# ACB-R1_0-43-CH13.net
KiCad netlist of a schematic drawn in EAGLE
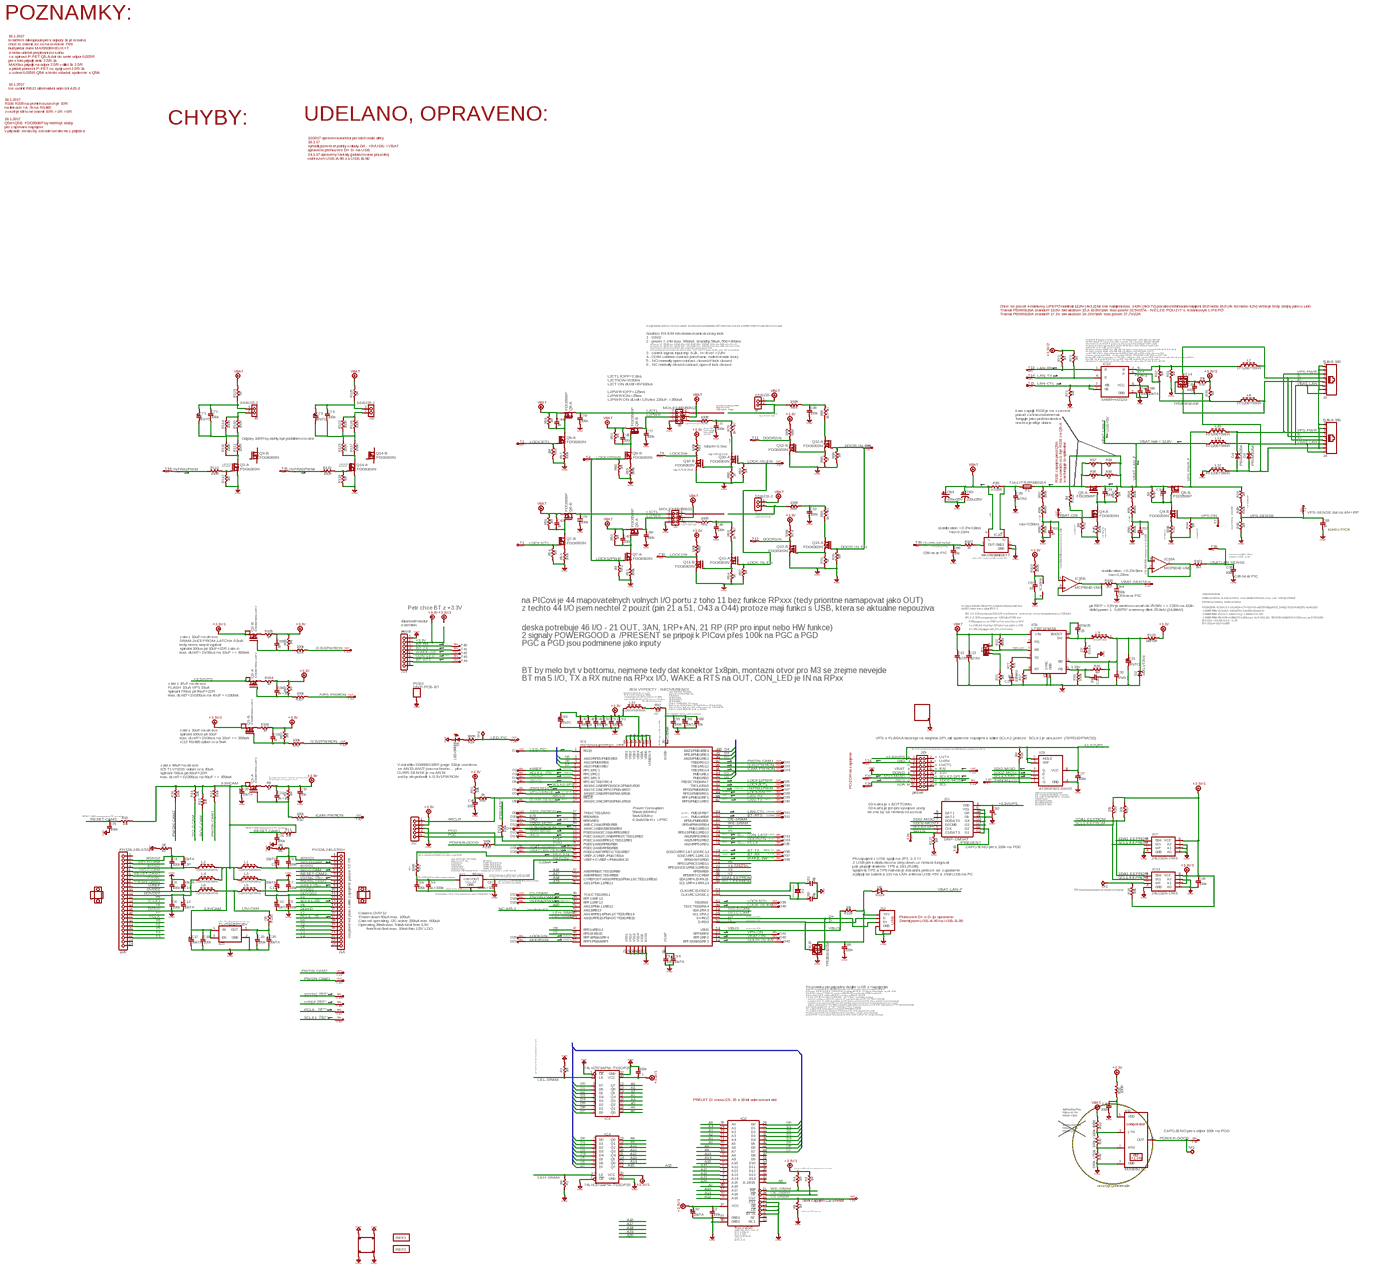
[diagram p0: schematic, sheet 1, overview]
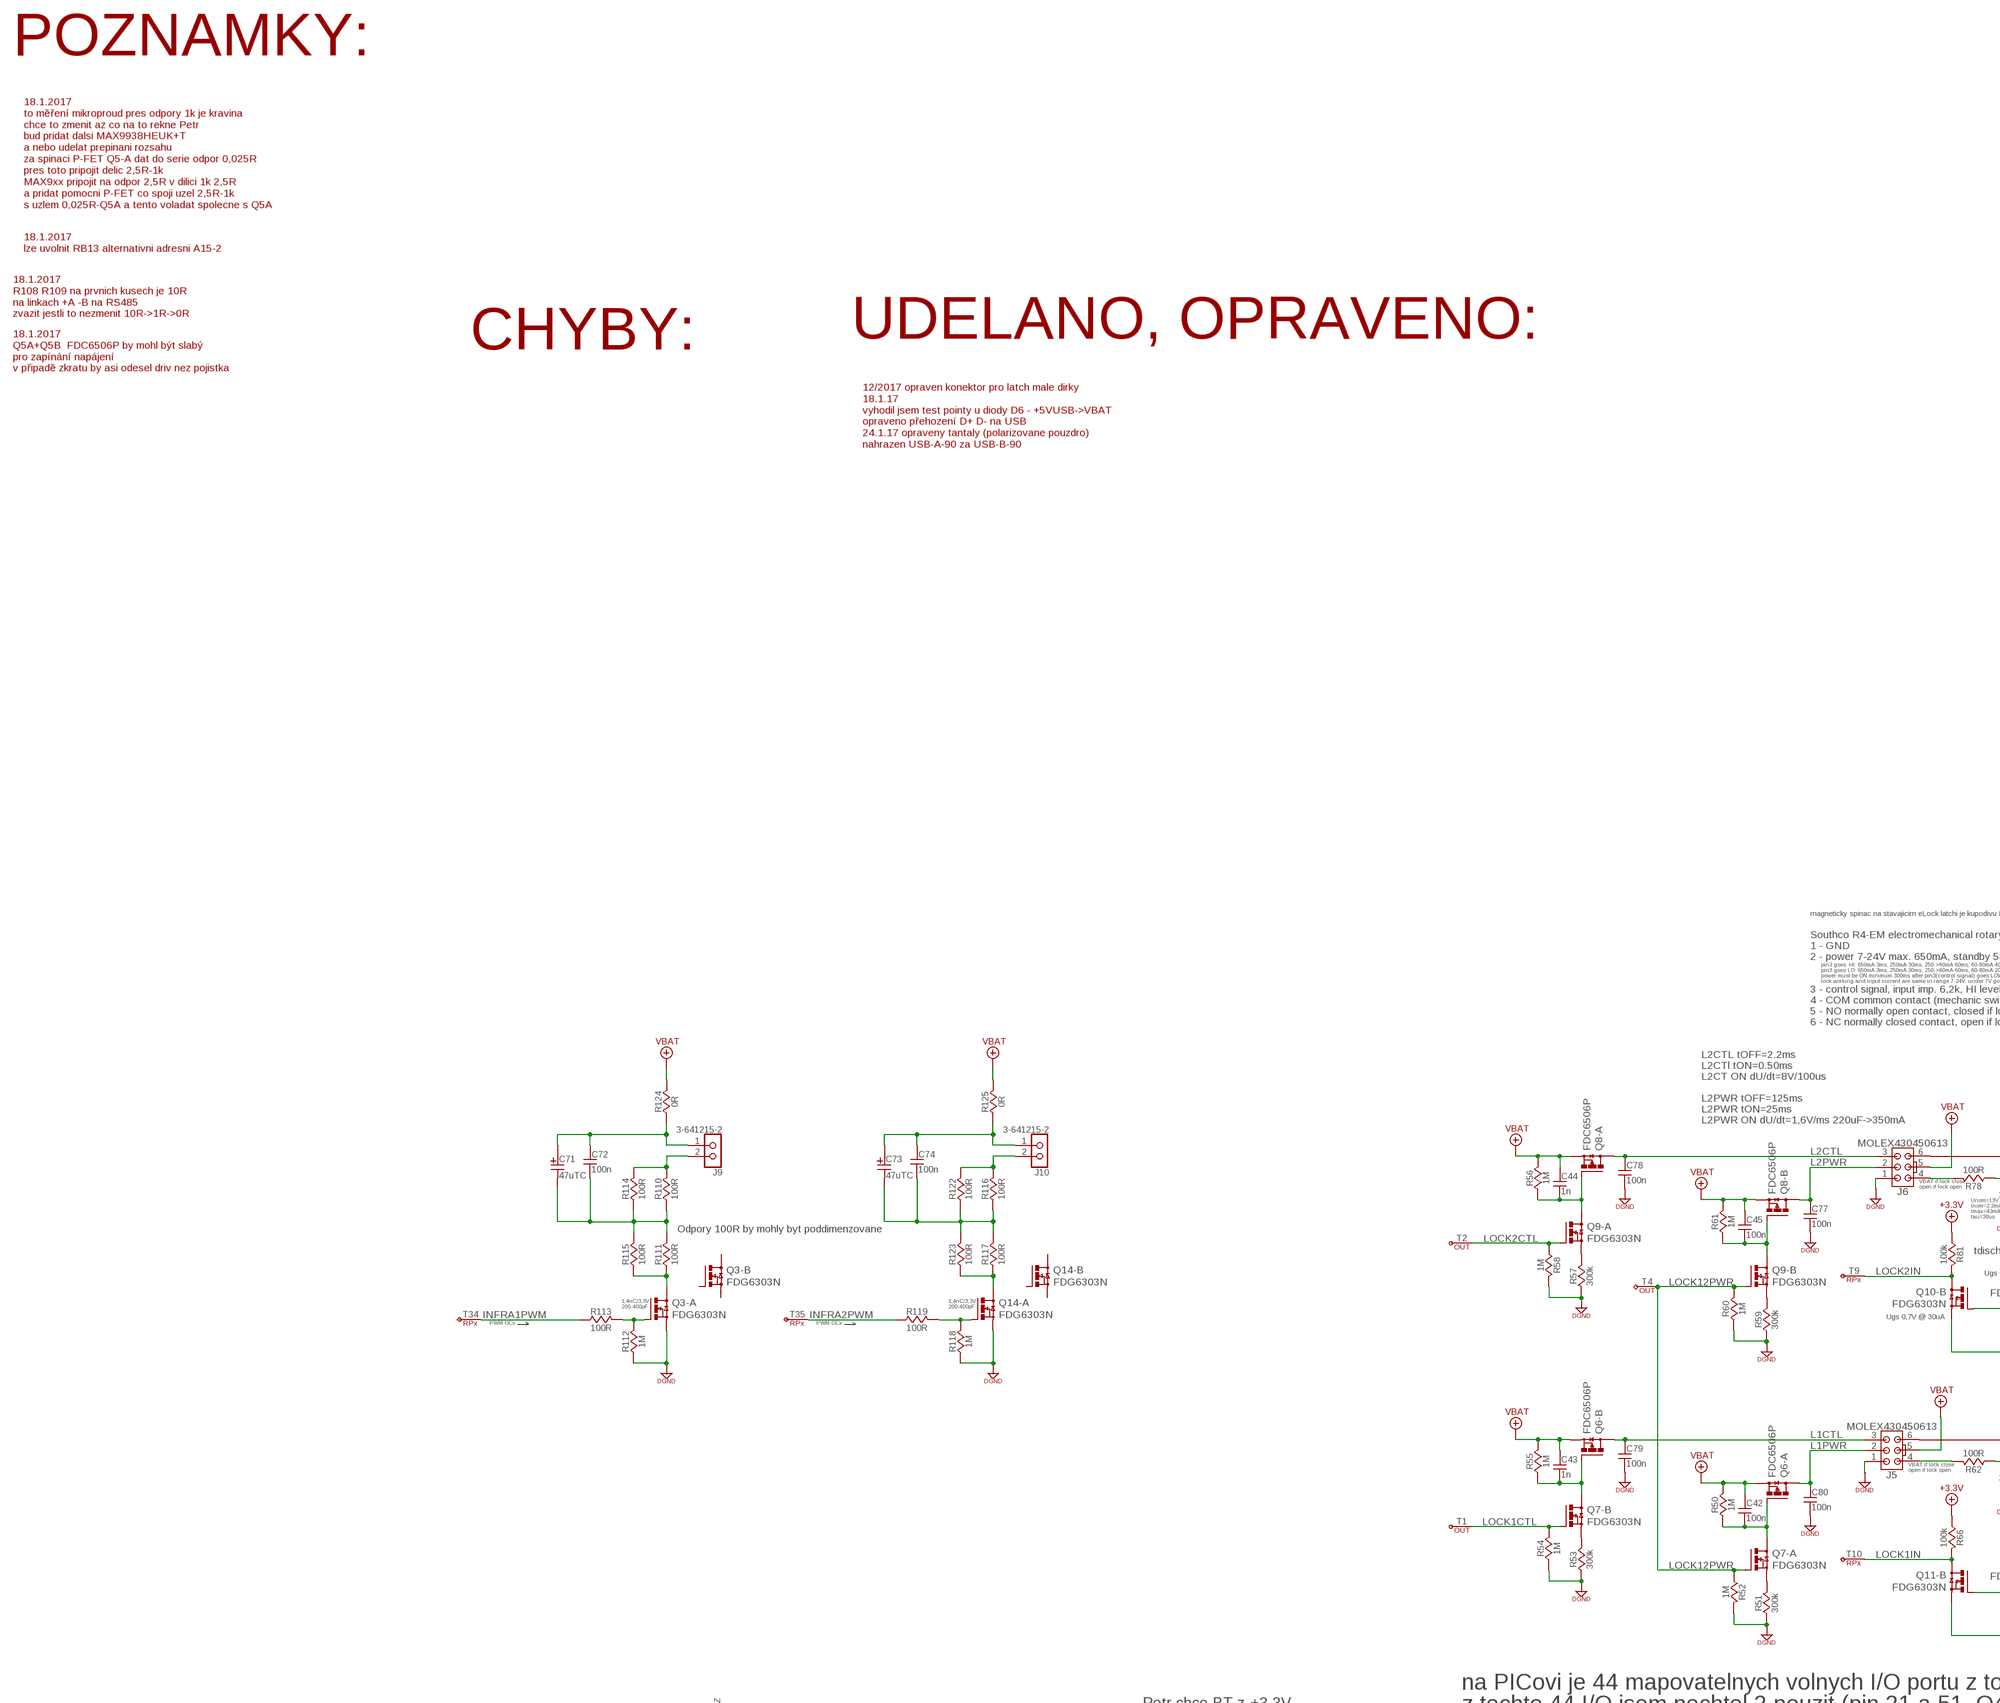
[diagram p1: schematic, sheet 1, part 1 of 4]
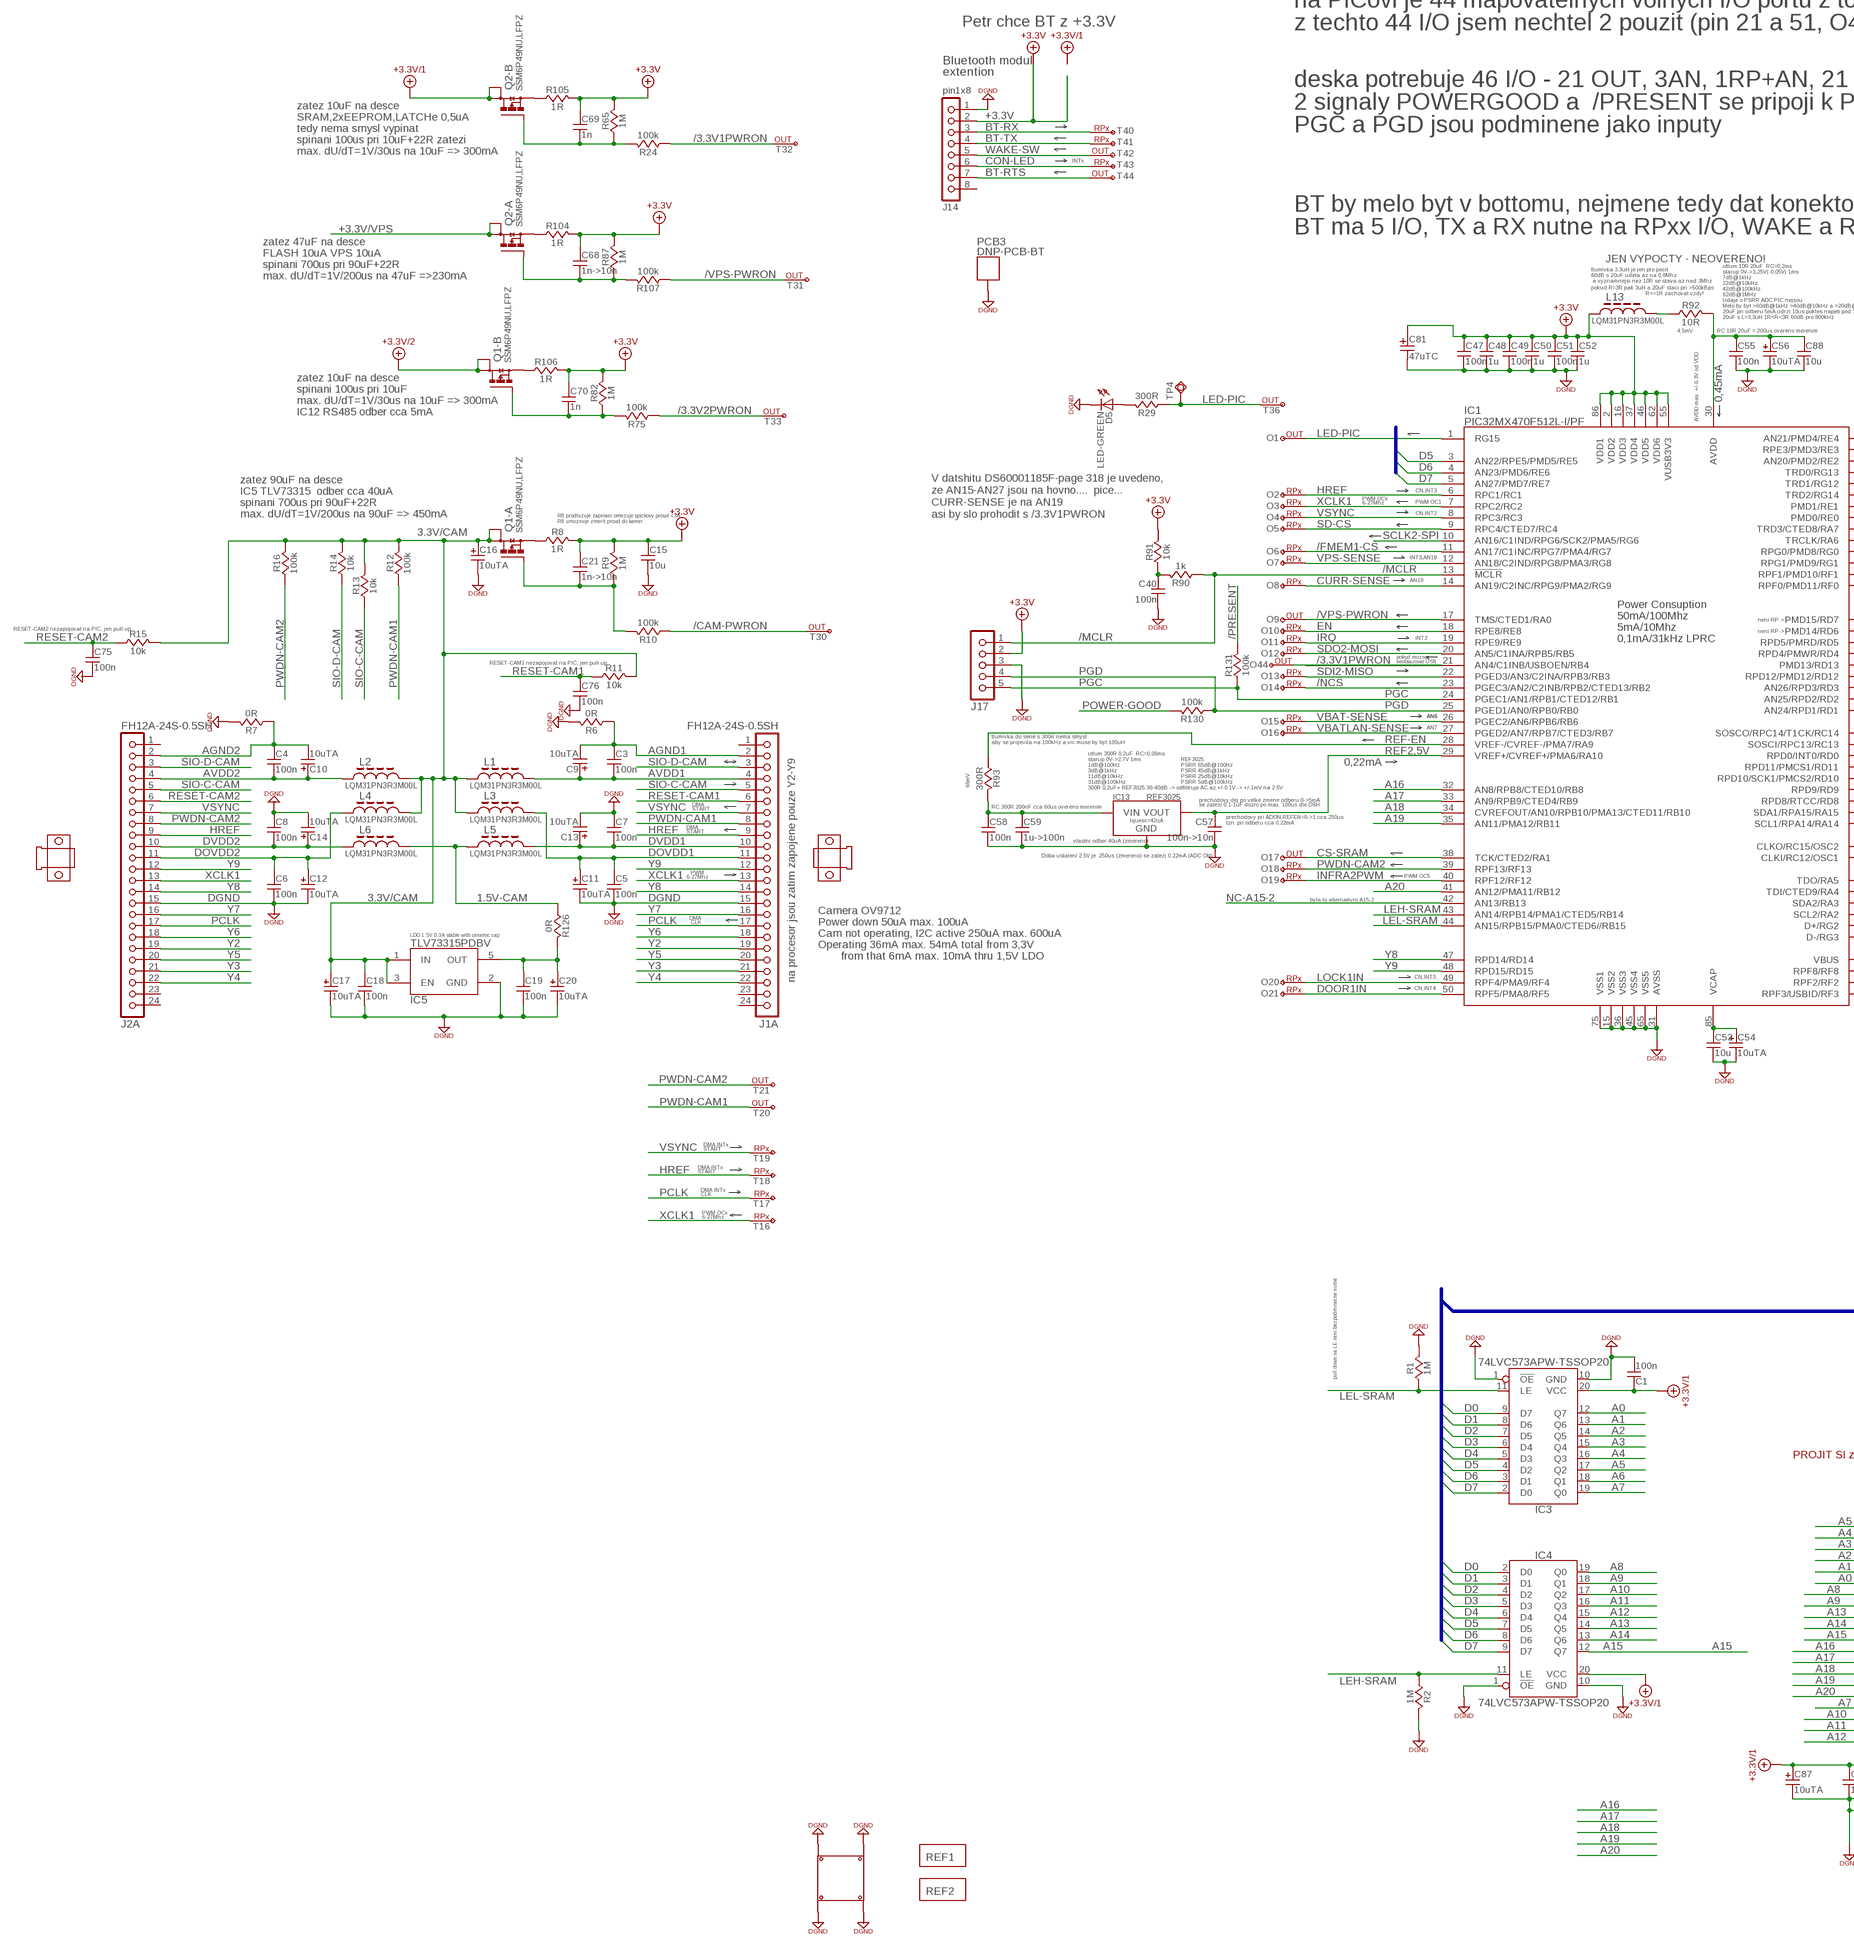
[diagram p2: schematic, sheet 1, part 2 of 4]
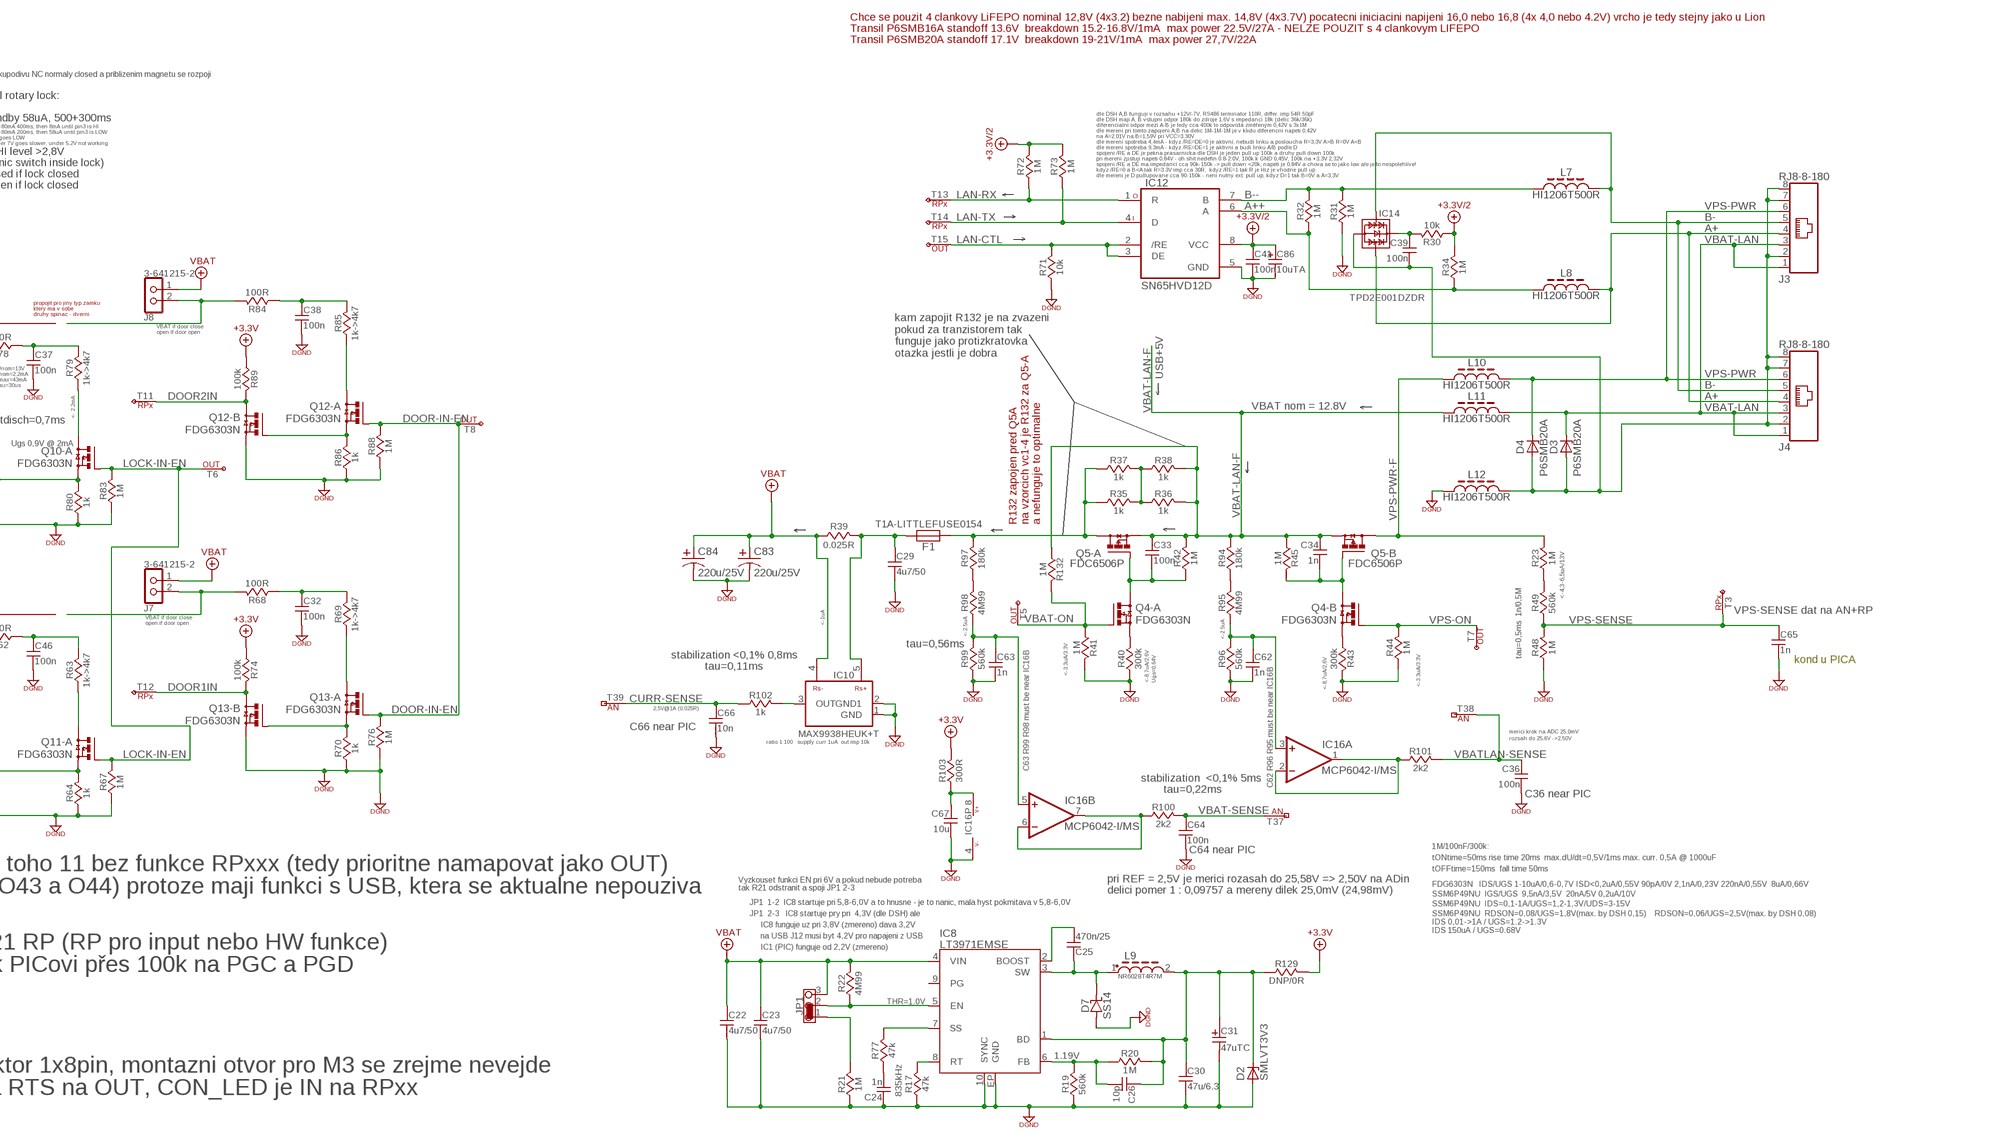
[diagram p3: schematic, sheet 1, part 3 of 4]
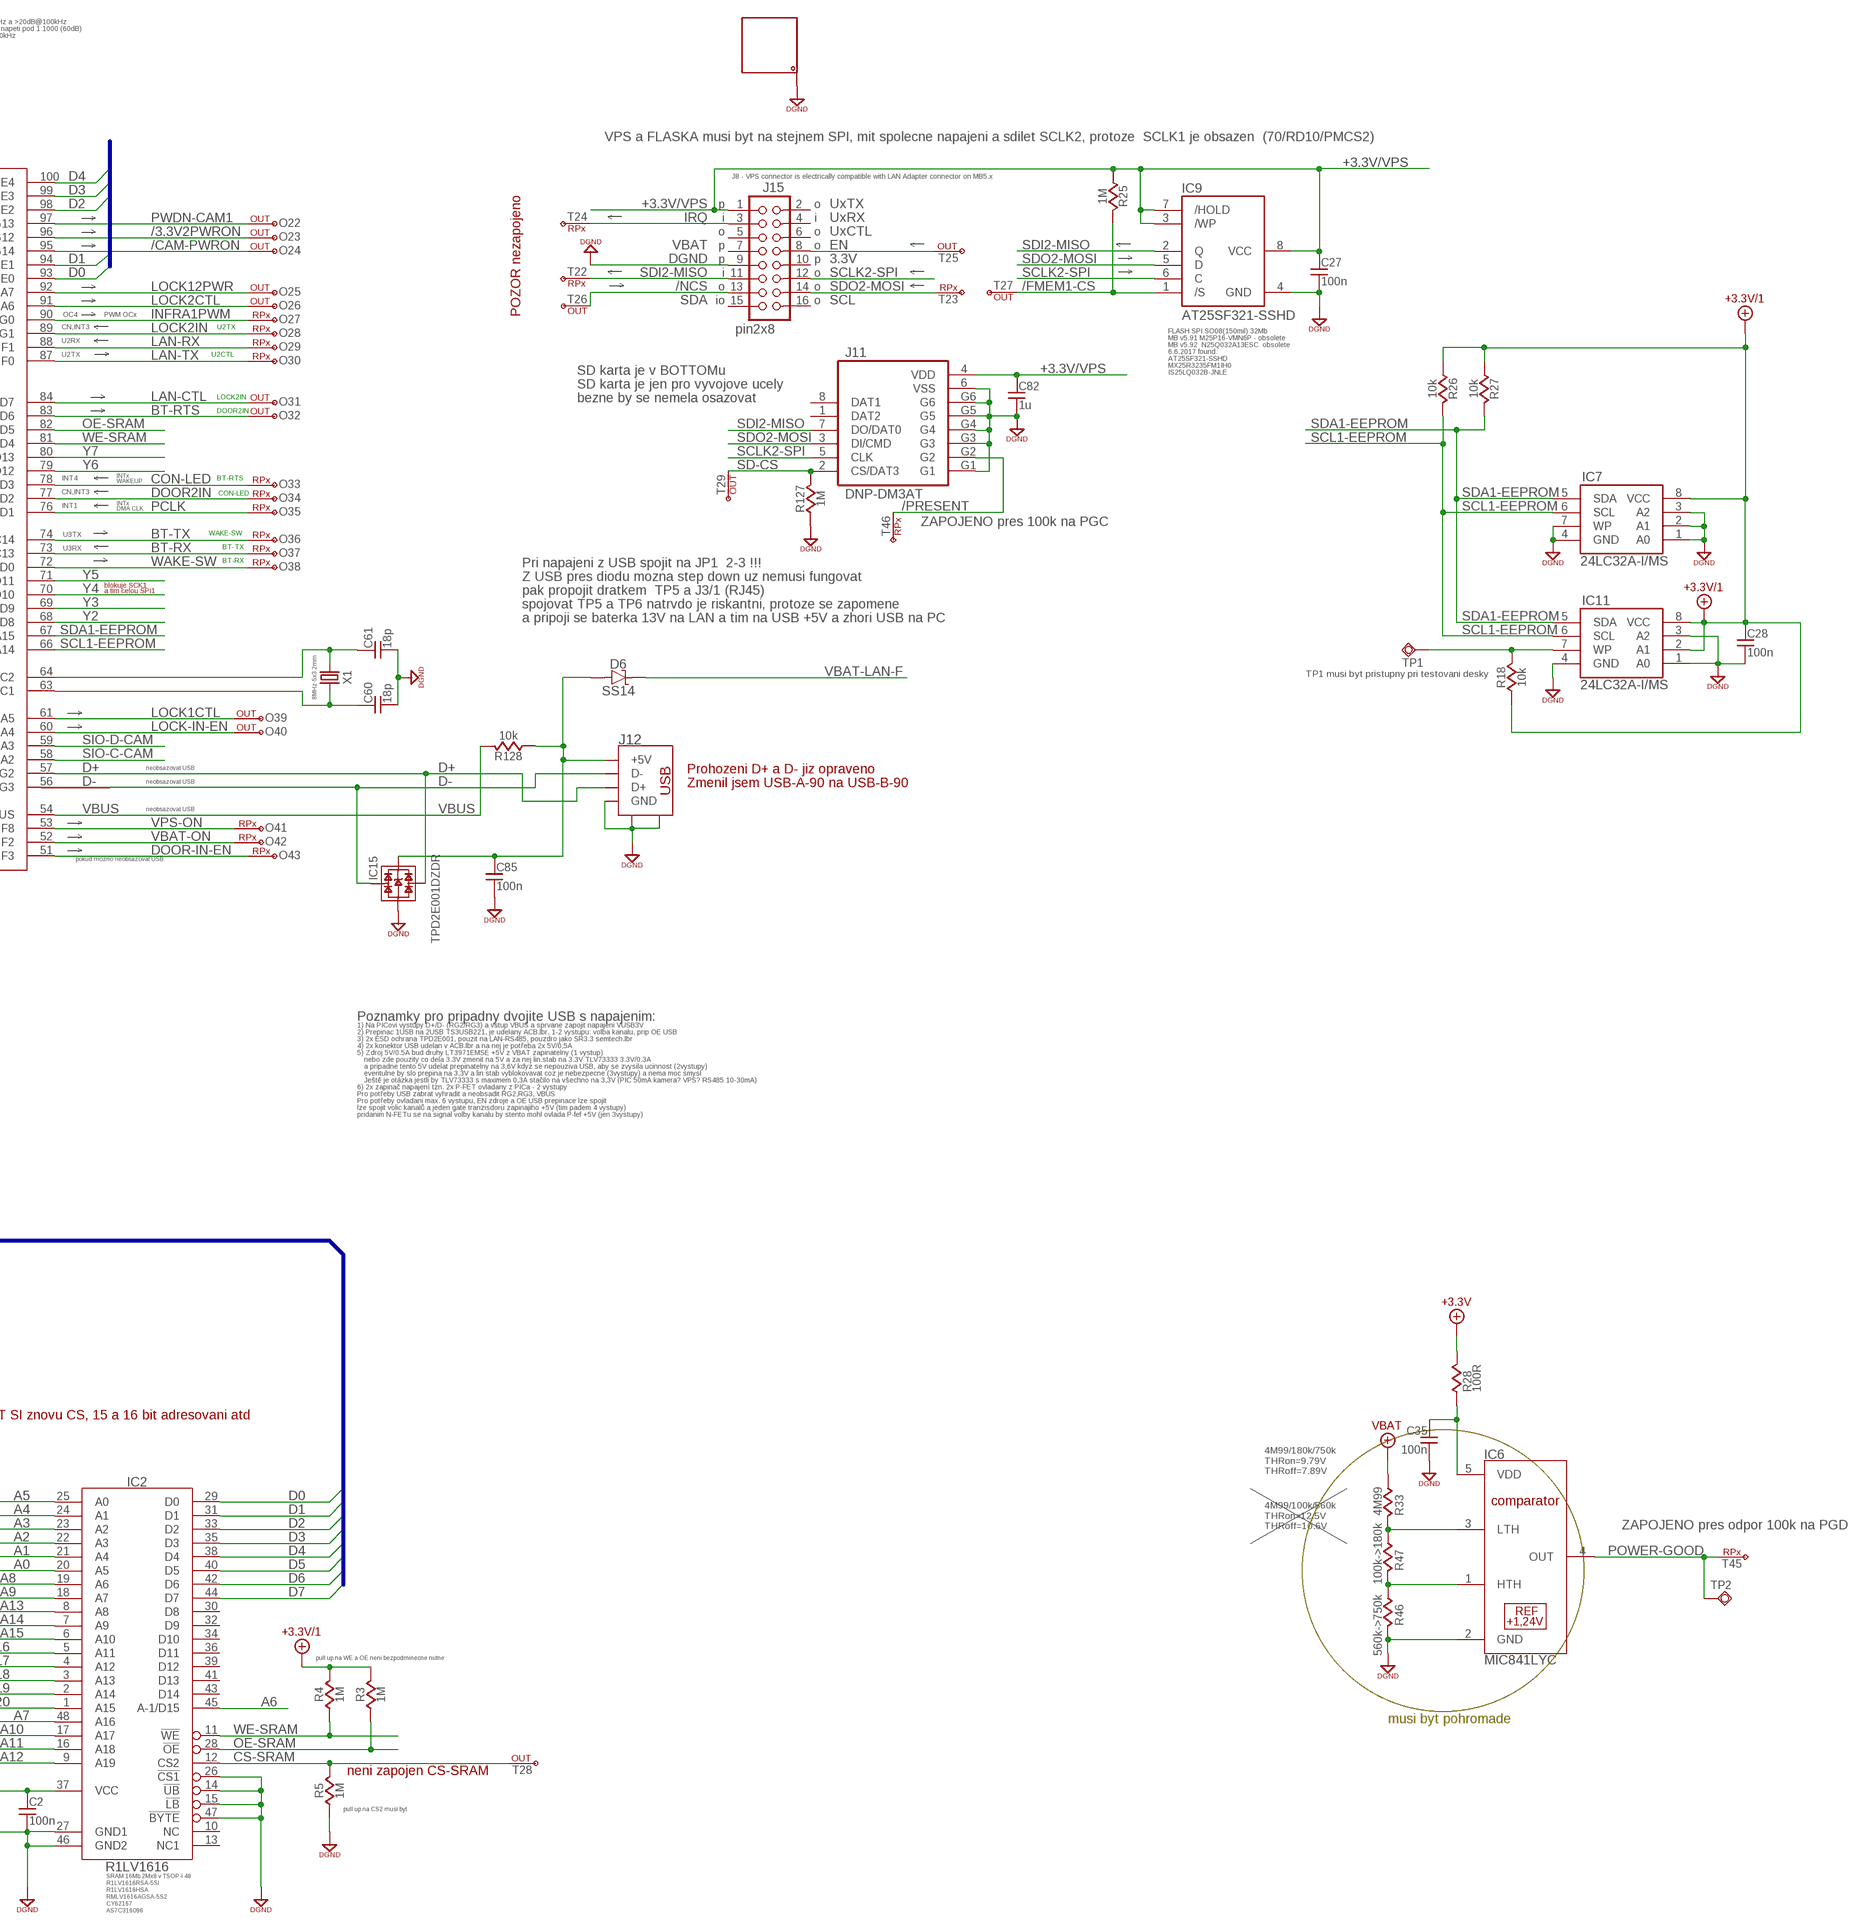
[diagram p4: schematic, sheet 1, part 4 of 4]

(export (version "E")
  (design (tool "Eeschema 10.0.6"))
  (components
    (comp (ref "C1")
      (value "100n")
      (footprint "eagle-import:0603")
      (libsource (lib "eagle-import") (part "C-0603"))
    )
    (comp (ref "C2")
      (value "100n")
      (footprint "eagle-import:0603")
      (libsource (lib "eagle-import") (part "C-0603"))
    )
    (comp (ref "C3")
      (value "100n")
      (footprint "eagle-import:0603")
      (libsource (lib "eagle-import") (part "C-0603"))
    )
    (comp (ref "C4")
      (value "100n")
      (footprint "eagle-import:0603")
      (libsource (lib "eagle-import") (part "C-0603"))
    )
    (comp (ref "C5")
      (value "100n")
      (footprint "eagle-import:0603")
      (libsource (lib "eagle-import") (part "C-0603"))
    )
    (comp (ref "C6")
      (value "100n")
      (footprint "eagle-import:0603")
      (libsource (lib "eagle-import") (part "C-0603"))
    )
    (comp (ref "C7")
      (value "100n")
      (footprint "eagle-import:0603")
      (libsource (lib "eagle-import") (part "C-0603"))
    )
    (comp (ref "C8")
      (value "100n")
      (footprint "eagle-import:0603")
      (libsource (lib "eagle-import") (part "C-0603"))
    )
    (comp (ref "C9")
      (value "10uTA")
      (footprint "eagle-import:1206-POL-C")
      (libsource (lib "eagle-import") (part "CT-1206"))
    )
    (comp (ref "C10")
      (value "10uTA")
      (footprint "eagle-import:1206-POL-C")
      (libsource (lib "eagle-import") (part "CT-1206"))
    )
    (comp (ref "C11")
      (value "10uTA")
      (footprint "eagle-import:1206-POL-C")
      (libsource (lib "eagle-import") (part "CT-1206"))
    )
    (comp (ref "C12")
      (value "10uTA")
      (footprint "eagle-import:1206-POL-C")
      (libsource (lib "eagle-import") (part "CT-1206"))
    )
    (comp (ref "C13")
      (value "10uTA")
      (footprint "eagle-import:1206-POL-C")
      (libsource (lib "eagle-import") (part "CT-1206"))
    )
    (comp (ref "C14")
      (value "10uTA")
      (footprint "eagle-import:1206-POL-C")
      (libsource (lib "eagle-import") (part "CT-1206"))
    )
    (comp (ref "C15")
      (value "10u")
      (footprint "eagle-import:0603")
      (libsource (lib "eagle-import") (part "C-0603"))
    )
    (comp (ref "C16")
      (value "10uTA")
      (footprint "eagle-import:1206-POL-C")
      (libsource (lib "eagle-import") (part "CT-1206"))
    )
    (comp (ref "C17")
      (value "10uTA")
      (footprint "eagle-import:1206-POL-C")
      (libsource (lib "eagle-import") (part "CT-1206"))
    )
    (comp (ref "C18")
      (value "100n")
      (footprint "eagle-import:0603")
      (libsource (lib "eagle-import") (part "C-0603"))
    )
    (comp (ref "C19")
      (value "100n")
      (footprint "eagle-import:0603")
      (libsource (lib "eagle-import") (part "C-0603"))
    )
    (comp (ref "C20")
      (value "10uTA")
      (footprint "eagle-import:1206-POL-C")
      (libsource (lib "eagle-import") (part "CT-1206"))
    )
    (comp (ref "C21")
      (value "1n->10n")
      (footprint "eagle-import:0603")
      (libsource (lib "eagle-import") (part "C-0603"))
    )
    (comp (ref "C22")
      (value "4u7/50")
      (footprint "eagle-import:1206")
      (libsource (lib "eagle-import") (part "C-1206"))
    )
    (comp (ref "C23")
      (value "4u7/50")
      (footprint "eagle-import:1206")
      (libsource (lib "eagle-import") (part "C-1206"))
    )
    (comp (ref "C24")
      (value "1n")
      (footprint "eagle-import:0603")
      (libsource (lib "eagle-import") (part "C-0603"))
    )
    (comp (ref "C25")
      (value "470n/25")
      (footprint "eagle-import:0603")
      (libsource (lib "eagle-import") (part "C-0603"))
    )
    (comp (ref "C26")
      (value "10p")
      (footprint "eagle-import:0603")
      (libsource (lib "eagle-import") (part "C-0603"))
    )
    (comp (ref "C27")
      (value "100n")
      (footprint "eagle-import:0603")
      (libsource (lib "eagle-import") (part "C-0603"))
    )
    (comp (ref "C28")
      (value "100n")
      (footprint "eagle-import:0603")
      (libsource (lib "eagle-import") (part "C-0603"))
    )
    (comp (ref "C29")
      (value "4u7/50")
      (footprint "eagle-import:1206")
      (libsource (lib "eagle-import") (part "C-1206"))
    )
    (comp (ref "C30")
      (value "47u/6.3")
      (footprint "eagle-import:1206")
      (libsource (lib "eagle-import") (part "C-1206"))
    )
    (comp (ref "C31")
      (value "47uTC")
      (footprint "eagle-import:CT-C")
      (libsource (lib "eagle-import") (part "CT-C"))
    )
    (comp (ref "C32")
      (value "100n")
      (footprint "eagle-import:0603")
      (libsource (lib "eagle-import") (part "C-0603"))
    )
    (comp (ref "C33")
      (value "100n")
      (footprint "eagle-import:0603")
      (libsource (lib "eagle-import") (part "C-0603"))
    )
    (comp (ref "C34")
      (value "1n")
      (footprint "eagle-import:0603")
      (libsource (lib "eagle-import") (part "C-0603"))
    )
    (comp (ref "C35")
      (value "100n")
      (footprint "eagle-import:0603")
      (libsource (lib "eagle-import") (part "C-0603"))
    )
    (comp (ref "C36")
      (value "100n")
      (footprint "eagle-import:0603")
      (libsource (lib "eagle-import") (part "C-0603"))
    )
    (comp (ref "C37")
      (value "100n")
      (footprint "eagle-import:0603")
      (libsource (lib "eagle-import") (part "C-0603"))
    )
    (comp (ref "C38")
      (value "100n")
      (footprint "eagle-import:0603")
      (libsource (lib "eagle-import") (part "C-0603"))
    )
    (comp (ref "C39")
      (value "100n")
      (footprint "eagle-import:0603")
      (libsource (lib "eagle-import") (part "C-0603"))
    )
    (comp (ref "C40")
      (value "100n")
      (footprint "eagle-import:0603")
      (libsource (lib "eagle-import") (part "C-0603"))
    )
    (comp (ref "C41")
      (value "100n")
      (footprint "eagle-import:0603")
      (libsource (lib "eagle-import") (part "C-0603"))
    )
    (comp (ref "C42")
      (value "100n")
      (footprint "eagle-import:0603")
      (libsource (lib "eagle-import") (part "C-0603"))
    )
    (comp (ref "C43")
      (value "1n")
      (footprint "eagle-import:0603")
      (libsource (lib "eagle-import") (part "C-0603"))
    )
    (comp (ref "C44")
      (value "1n")
      (footprint "eagle-import:0603")
      (libsource (lib "eagle-import") (part "C-0603"))
    )
    (comp (ref "C45")
      (value "100n")
      (footprint "eagle-import:0603")
      (libsource (lib "eagle-import") (part "C-0603"))
    )
    (comp (ref "C46")
      (value "100n")
      (footprint "eagle-import:0603")
      (libsource (lib "eagle-import") (part "C-0603"))
    )
    (comp (ref "C47")
      (value "100n")
      (footprint "eagle-import:0603")
      (libsource (lib "eagle-import") (part "C-0603"))
    )
    (comp (ref "C48")
      (value "1u")
      (footprint "eagle-import:0603")
      (libsource (lib "eagle-import") (part "C-0603"))
    )
    (comp (ref "C49")
      (value "100n")
      (footprint "eagle-import:0603")
      (libsource (lib "eagle-import") (part "C-0603"))
    )
    (comp (ref "C50")
      (value "1u")
      (footprint "eagle-import:0603")
      (libsource (lib "eagle-import") (part "C-0603"))
    )
    (comp (ref "C51")
      (value "100n")
      (footprint "eagle-import:0603")
      (libsource (lib "eagle-import") (part "C-0603"))
    )
    (comp (ref "C52")
      (value "1u")
      (footprint "eagle-import:0603")
      (libsource (lib "eagle-import") (part "C-0603"))
    )
    (comp (ref "C53")
      (value "10u")
      (footprint "eagle-import:0603")
      (libsource (lib "eagle-import") (part "C-0603"))
    )
    (comp (ref "C54")
      (value "10uTA")
      (footprint "eagle-import:1206-POL-C")
      (libsource (lib "eagle-import") (part "CT-1206"))
    )
    (comp (ref "C55")
      (value "100n")
      (footprint "eagle-import:0603")
      (libsource (lib "eagle-import") (part "C-0603"))
    )
    (comp (ref "C56")
      (value "10uTA")
      (footprint "eagle-import:1206-POL-C")
      (libsource (lib "eagle-import") (part "CT-1206"))
    )
    (comp (ref "C57")
      (value "100n->10n")
      (footprint "eagle-import:0603")
      (libsource (lib "eagle-import") (part "C-0603"))
    )
    (comp (ref "C58")
      (value "100n")
      (footprint "eagle-import:0603")
      (libsource (lib "eagle-import") (part "C-0603"))
    )
    (comp (ref "C59")
      (value "1u->100n")
      (footprint "eagle-import:0603")
      (libsource (lib "eagle-import") (part "C-0603"))
    )
    (comp (ref "C60")
      (value "18p")
      (footprint "eagle-import:0603")
      (libsource (lib "eagle-import") (part "C-0603"))
    )
    (comp (ref "C61")
      (value "18p")
      (footprint "eagle-import:0603")
      (libsource (lib "eagle-import") (part "C-0603"))
    )
    (comp (ref "C62")
      (value "1n")
      (footprint "eagle-import:0603")
      (libsource (lib "eagle-import") (part "C-0603"))
    )
    (comp (ref "C63")
      (value "1n")
      (footprint "eagle-import:0603")
      (libsource (lib "eagle-import") (part "C-0603"))
    )
    (comp (ref "C64")
      (value "100n")
      (footprint "eagle-import:0603")
      (libsource (lib "eagle-import") (part "C-0603"))
    )
    (comp (ref "C65")
      (value "1n")
      (footprint "eagle-import:0603")
      (libsource (lib "eagle-import") (part "C-0603"))
    )
    (comp (ref "C66")
      (value "10n")
      (footprint "eagle-import:0603")
      (libsource (lib "eagle-import") (part "C-0603"))
    )
    (comp (ref "C67")
      (value "10u")
      (footprint "eagle-import:0603")
      (libsource (lib "eagle-import") (part "C-0603"))
    )
    (comp (ref "C68")
      (value "1n->10n")
      (footprint "eagle-import:0603")
      (libsource (lib "eagle-import") (part "C-0603"))
    )
    (comp (ref "C69")
      (value "1n")
      (footprint "eagle-import:0603")
      (libsource (lib "eagle-import") (part "C-0603"))
    )
    (comp (ref "C70")
      (value "1n")
      (footprint "eagle-import:0603")
      (libsource (lib "eagle-import") (part "C-0603"))
    )
    (comp (ref "C71")
      (value "47uTC")
      (footprint "eagle-import:CT-C")
      (libsource (lib "eagle-import") (part "CT-C"))
    )
    (comp (ref "C72")
      (value "100n")
      (footprint "eagle-import:0603")
      (libsource (lib "eagle-import") (part "C-0603"))
    )
    (comp (ref "C73")
      (value "47uTC")
      (footprint "eagle-import:CT-C")
      (libsource (lib "eagle-import") (part "CT-C"))
    )
    (comp (ref "C74")
      (value "100n")
      (footprint "eagle-import:0603")
      (libsource (lib "eagle-import") (part "C-0603"))
    )
    (comp (ref "C75")
      (value "100n")
      (footprint "eagle-import:0603")
      (libsource (lib "eagle-import") (part "C-0603"))
    )
    (comp (ref "C76")
      (value "100n")
      (footprint "eagle-import:0603")
      (libsource (lib "eagle-import") (part "C-0603"))
    )
    (comp (ref "C77")
      (value "100n")
      (footprint "eagle-import:0603")
      (libsource (lib "eagle-import") (part "C-0603"))
    )
    (comp (ref "C78")
      (value "100n")
      (footprint "eagle-import:0603")
      (libsource (lib "eagle-import") (part "C-0603"))
    )
    (comp (ref "C79")
      (value "100n")
      (footprint "eagle-import:0603")
      (libsource (lib "eagle-import") (part "C-0603"))
    )
    (comp (ref "C80")
      (value "100n")
      (footprint "eagle-import:0603")
      (libsource (lib "eagle-import") (part "C-0603"))
    )
    (comp (ref "C81")
      (value "47uTC")
      (footprint "eagle-import:CT-C")
      (libsource (lib "eagle-import") (part "CT-C"))
    )
    (comp (ref "C82")
      (value "1u")
      (footprint "eagle-import:0603")
      (libsource (lib "eagle-import") (part "C-0603"))
    )
    (comp (ref "C83")
      (value "220u/25V")
      (footprint "eagle-import:CAP_8MM_DIA_SMT")
      (libsource (lib "eagle-import") (part "CAP-ELEC-SMD-8MM"))
    )
    (comp (ref "C84")
      (value "220u/25V")
      (footprint "eagle-import:CAP_8MM_DIA_SMT")
      (libsource (lib "eagle-import") (part "CAP-ELEC-SMD-8MM"))
    )
    (comp (ref "C85")
      (value "100n")
      (footprint "eagle-import:0603")
      (libsource (lib "eagle-import") (part "C-0603"))
    )
    (comp (ref "C86")
      (value "10uTA")
      (footprint "eagle-import:1206-POL-C")
      (libsource (lib "eagle-import") (part "CT-1206"))
    )
    (comp (ref "C87")
      (value "10uTA")
      (footprint "eagle-import:1206-POL-C")
      (libsource (lib "eagle-import") (part "CT-1206"))
    )
    (comp (ref "C88")
      (value "10u")
      (footprint "eagle-import:0603")
      (libsource (lib "eagle-import") (part "C-0603"))
    )
    (comp (ref "D2")
      (value "SMLVT3V3")
      (footprint "eagle-import:SMA")
      (libsource (lib "eagle-import") (part "SMLVT3V3"))
    )
    (comp (ref "D3")
      (value "P6SMB20A")
      (footprint "eagle-import:SMB")
      (libsource (lib "eagle-import") (part "P6SMB"))
    )
    (comp (ref "D4")
      (value "P6SMB20A")
      (footprint "eagle-import:SMB")
      (libsource (lib "eagle-import") (part "P6SMB"))
    )
    (comp (ref "D5")
      (value "LED-GREEN")
      (footprint "eagle-import:0805-POL-D")
      (libsource (lib "eagle-import") (part "LED-0805"))
    )
    (comp (ref "D6")
      (value "SS14")
      (footprint "eagle-import:SMA")
      (libsource (lib "eagle-import") (part "DS-SMA"))
    )
    (comp (ref "D7")
      (value "SS14")
      (footprint "eagle-import:SMA")
      (libsource (lib "eagle-import") (part "DS-SMA"))
    )
    (comp (ref "F1")
      (value "T1A-LITTLEFUSE0154")
      (footprint "eagle-import:LITTLEFUSE0154")
      (libsource (lib "eagle-import") (part "POJISTKA-LITTLEFUSE0154"))
    )
    (comp (ref "H1")
      (value "CAM-HOLDER")
      (footprint "eagle-import:CAM-HOLDER")
      (libsource (lib "eagle-import") (part "CAM-HOLDER"))
    )
    (comp (ref "H2")
      (value "CAM-HOLDER")
      (footprint "eagle-import:CAM-HOLDER")
      (libsource (lib "eagle-import") (part "CAM-HOLDER"))
    )
    (comp (ref "IC1")
      (value "PIC32MX470F512L-I/PF")
      (footprint "eagle-import:TQFP100_14X14_0,5MM")
      (libsource (lib "eagle-import") (part "PIC32MX470F512L-I/PF"))
    )
    (comp (ref "IC2")
      (value "R1LV1616")
      (footprint "eagle-import:48-TSOP-I")
      (libsource (lib "eagle-import") (part "R1LV1616HSA"))
    )
    (comp (ref "IC3")
      (value "74LVC573APW-TSSOP20")
      (footprint "eagle-import:TSSOP20")
      (libsource (lib "eagle-import") (part "74LVC573APW-TSSOP20"))
    )
    (comp (ref "IC4")
      (value "74LVC573APW-TSSOP20")
      (footprint "eagle-import:TSSOP20")
      (libsource (lib "eagle-import") (part "74LVC573APW-TSSOP20"))
    )
    (comp (ref "IC5")
      (value "TLV73315PDBV")
      (footprint "eagle-import:SOT23-5")
      (libsource (lib "eagle-import") (part "TLV73315PDBV"))
    )
    (comp (ref "IC6")
      (value "MIC841LYC")
      (footprint "eagle-import:SC-70-5")
      (libsource (lib "eagle-import") (part "MIC841LYC"))
    )
    (comp (ref "IC7")
      (value "24LC32A-I/MS")
      (footprint "eagle-import:MSOP-08")
      (libsource (lib "eagle-import") (part "24-I/MS"))
    )
    (comp (ref "IC8")
      (value "LT3971EMSE")
      (footprint "eagle-import:MSOP10EXP")
      (libsource (lib "eagle-import") (part "LT3971EMSE"))
    )
    (comp (ref "IC9")
      (value "AT25SF321-SSHD")
      (footprint "eagle-import:SO-08")
      (libsource (lib "eagle-import") (part "M25P16-VMN6P"))
    )
    (comp (ref "IC10")
      (value "MAX9938HEUK+T")
      (footprint "eagle-import:SOT23-5")
      (libsource (lib "eagle-import") (part "TSM9938HEUK+T"))
    )
    (comp (ref "IC11")
      (value "24LC32A-I/MS")
      (footprint "eagle-import:MSOP-08")
      (libsource (lib "eagle-import") (part "24-I/MS"))
    )
    (comp (ref "IC12")
      (value "SN65HVD12D")
      (footprint "eagle-import:SO08")
      (libsource (lib "eagle-import") (part "SN65HVD3082ED"))
    )
    (comp (ref "IC13")
      (value "REF3025")
      (footprint "eagle-import:SOT23")
      (libsource (lib "eagle-import") (part "REF3025"))
    )
    (comp (ref "IC14")
      (value "TPD2E001DZDR")
      (footprint "eagle-import:SOT-143")
      (libsource (lib "eagle-import") (part "SR05.TCT"))
    )
    (comp (ref "IC15")
      (value "TPD2E001DZDR")
      (footprint "eagle-import:SOT-143")
      (libsource (lib "eagle-import") (part "SR05.TCT"))
    )
    (comp (ref "IC16")
      (value "MCP6042-I/MS")
      (footprint "eagle-import:MSOP-08")
      (libsource (lib "eagle-import") (part "MCP6042-I/MS"))
    )
    (comp (ref "J1")
      (value "FH12A-24S-0.5SH")
      (footprint "eagle-import:FH12A-24S-05SH")
      (libsource (lib "eagle-import") (part "FH12A-24S-0.5SH"))
    )
    (comp (ref "J2")
      (value "FH12A-24S-0.5SH")
      (footprint "eagle-import:FH12A-24S-05SH")
      (libsource (lib "eagle-import") (part "FH12A-24S-0.5SH"))
    )
    (comp (ref "J3")
      (value "RJ8-8-180")
      (footprint "eagle-import:RJ8-8-180")
      (libsource (lib "eagle-import") (part "RJ8-8-180"))
    )
    (comp (ref "J4")
      (value "RJ8-8-180")
      (footprint "eagle-import:RJ8-8-180")
      (libsource (lib "eagle-import") (part "RJ8-8-180"))
    )
    (comp (ref "J5")
      (value "MOLEX430450613")
      (footprint "eagle-import:MOLEX430450613")
      (libsource (lib "eagle-import") (part "MOLEX430450613"))
    )
    (comp (ref "J6")
      (value "MOLEX430450613")
      (footprint "eagle-import:MOLEX430450613")
      (libsource (lib "eagle-import") (part "MOLEX430450613"))
    )
    (comp (ref "J7")
      (value "3-641215-2")
      (footprint "eagle-import:3-641215-2")
      (libsource (lib "eagle-import") (part "3-641215-2"))
    )
    (comp (ref "J8")
      (value "3-641215-2")
      (footprint "eagle-import:3-641215-2")
      (libsource (lib "eagle-import") (part "3-641215-2"))
    )
    (comp (ref "J9")
      (value "3-641215-2")
      (footprint "eagle-import:3-641215-2")
      (libsource (lib "eagle-import") (part "3-641215-2"))
    )
    (comp (ref "J10")
      (value "3-641215-2")
      (footprint "eagle-import:3-641215-2")
      (libsource (lib "eagle-import") (part "3-641215-2"))
    )
    (comp (ref "J11")
      (value "DNP-DM3AT")
      (footprint "eagle-import:DM3AT")
      (libsource (lib "eagle-import") (part "DM3AT"))
    )
    (comp (ref "J12")
      (value "USB_A_180")
      (footprint "eagle-import:USB_B_180")
      (libsource (lib "eagle-import") (part "USB_B_180"))
    )
    (comp (ref "J14")
      (value "pin1x8")
      (footprint "eagle-import:MA08-1-MALE")
      (libsource (lib "eagle-import") (part "MA08-1-M"))
    )
    (comp (ref "J15")
      (value "pin2x8")
      (footprint "eagle-import:MA08-2")
      (libsource (lib "eagle-import") (part "MA08-2"))
    )
    (comp (ref "J17")
      (value "DNP-open-hole")
      (footprint "eagle-import:MA05-1")
      (libsource (lib "eagle-import") (part "MA05-1"))
    )
    (comp (ref "JP1")
      (value "JP3CLOSE12")
      (footprint "eagle-import:JP3CLOSE12")
      (libsource (lib "eagle-import") (part "JP3CLOSE12"))
    )
    (comp (ref "L1")
      (value "LQM31PN3R3M00L")
      (footprint "eagle-import:1206")
      (libsource (lib "eagle-import") (part "L-1206"))
    )
    (comp (ref "L2")
      (value "LQM31PN3R3M00L")
      (footprint "eagle-import:1206")
      (libsource (lib "eagle-import") (part "L-1206"))
    )
    (comp (ref "L3")
      (value "LQM31PN3R3M00L")
      (footprint "eagle-import:1206")
      (libsource (lib "eagle-import") (part "L-1206"))
    )
    (comp (ref "L4")
      (value "LQM31PN3R3M00L")
      (footprint "eagle-import:1206")
      (libsource (lib "eagle-import") (part "L-1206"))
    )
    (comp (ref "L5")
      (value "LQM31PN3R3M00L")
      (footprint "eagle-import:1206")
      (libsource (lib "eagle-import") (part "L-1206"))
    )
    (comp (ref "L6")
      (value "LQM31PN3R3M00L")
      (footprint "eagle-import:1206")
      (libsource (lib "eagle-import") (part "L-1206"))
    )
    (comp (ref "L7")
      (value "HI1206T500R")
      (footprint "eagle-import:1206")
      (libsource (lib "eagle-import") (part "L-1206"))
    )
    (comp (ref "L8")
      (value "HI1206T500R")
      (footprint "eagle-import:1206")
      (libsource (lib "eagle-import") (part "L-1206"))
    )
    (comp (ref "L9")
      (value "NR6028T4R7M")
      (footprint "eagle-import:NR6028")
      (libsource (lib "eagle-import") (part "NR6028"))
    )
    (comp (ref "L10")
      (value "HI1206T500R")
      (footprint "eagle-import:1206")
      (libsource (lib "eagle-import") (part "L-1206"))
    )
    (comp (ref "L11")
      (value "HI1206T500R")
      (footprint "eagle-import:1206")
      (libsource (lib "eagle-import") (part "L-1206"))
    )
    (comp (ref "L12")
      (value "HI1206T500R")
      (footprint "eagle-import:1206")
      (libsource (lib "eagle-import") (part "L-1206"))
    )
    (comp (ref "L13")
      (value "LQM31PN3R3M00L")
      (footprint "eagle-import:1206")
      (libsource (lib "eagle-import") (part "L-1206"))
    )
    (comp (ref "O1")
      (value "PIC-OUT")
      (footprint "eagle-import:TEMP-PAD")
      (libsource (lib "eagle-import") (part "PIC-OUT"))
    )
    (comp (ref "O2")
      (value "PIC-RPX")
      (footprint "eagle-import:TEMP-PAD")
      (libsource (lib "eagle-import") (part "PIC-RPX"))
    )
    (comp (ref "O3")
      (value "PIC-RPX")
      (footprint "eagle-import:TEMP-PAD")
      (libsource (lib "eagle-import") (part "PIC-RPX"))
    )
    (comp (ref "O4")
      (value "PIC-RPX")
      (footprint "eagle-import:TEMP-PAD")
      (libsource (lib "eagle-import") (part "PIC-RPX"))
    )
    (comp (ref "O5")
      (value "PIC-RPX")
      (footprint "eagle-import:TEMP-PAD")
      (libsource (lib "eagle-import") (part "PIC-RPX"))
    )
    (comp (ref "O6")
      (value "PIC-RPX")
      (footprint "eagle-import:TEMP-PAD")
      (libsource (lib "eagle-import") (part "PIC-RPX"))
    )
    (comp (ref "O7")
      (value "PIC-RPX")
      (footprint "eagle-import:TEMP-PAD")
      (libsource (lib "eagle-import") (part "PIC-RPX"))
    )
    (comp (ref "O8")
      (value "PIC-RPX")
      (footprint "eagle-import:TEMP-PAD")
      (libsource (lib "eagle-import") (part "PIC-RPX"))
    )
    (comp (ref "O9")
      (value "PIC-OUT")
      (footprint "eagle-import:TEMP-PAD")
      (libsource (lib "eagle-import") (part "PIC-OUT"))
    )
    (comp (ref "O10")
      (value "PIC-RPX")
      (footprint "eagle-import:TEMP-PAD")
      (libsource (lib "eagle-import") (part "PIC-RPX"))
    )
    (comp (ref "O11")
      (value "PIC-RPX")
      (footprint "eagle-import:TEMP-PAD")
      (libsource (lib "eagle-import") (part "PIC-RPX"))
    )
    (comp (ref "O12")
      (value "PIC-RPX")
      (footprint "eagle-import:TEMP-PAD")
      (libsource (lib "eagle-import") (part "PIC-RPX"))
    )
    (comp (ref "O13")
      (value "PIC-RPX")
      (footprint "eagle-import:TEMP-PAD")
      (libsource (lib "eagle-import") (part "PIC-RPX"))
    )
    (comp (ref "O14")
      (value "PIC-RPX")
      (footprint "eagle-import:TEMP-PAD")
      (libsource (lib "eagle-import") (part "PIC-RPX"))
    )
    (comp (ref "O15")
      (value "PIC-RPX")
      (footprint "eagle-import:TEMP-PAD")
      (libsource (lib "eagle-import") (part "PIC-RPX"))
    )
    (comp (ref "O16")
      (value "PIC-RPX")
      (footprint "eagle-import:TEMP-PAD")
      (libsource (lib "eagle-import") (part "PIC-RPX"))
    )
    (comp (ref "O17")
      (value "PIC-OUT")
      (footprint "eagle-import:TEMP-PAD")
      (libsource (lib "eagle-import") (part "PIC-OUT"))
    )
    (comp (ref "O18")
      (value "PIC-RPX")
      (footprint "eagle-import:TEMP-PAD")
      (libsource (lib "eagle-import") (part "PIC-RPX"))
    )
    (comp (ref "O19")
      (value "PIC-RPX")
      (footprint "eagle-import:TEMP-PAD")
      (libsource (lib "eagle-import") (part "PIC-RPX"))
    )
    (comp (ref "O20")
      (value "PIC-RPX")
      (footprint "eagle-import:TEMP-PAD")
      (libsource (lib "eagle-import") (part "PIC-RPX"))
    )
    (comp (ref "O21")
      (value "PIC-RPX")
      (footprint "eagle-import:TEMP-PAD")
      (libsource (lib "eagle-import") (part "PIC-RPX"))
    )
    (comp (ref "O22")
      (value "PIC-OUT")
      (footprint "eagle-import:TEMP-PAD")
      (libsource (lib "eagle-import") (part "PIC-OUT"))
    )
    (comp (ref "O23")
      (value "PIC-OUT")
      (footprint "eagle-import:TEMP-PAD")
      (libsource (lib "eagle-import") (part "PIC-OUT"))
    )
    (comp (ref "O24")
      (value "PIC-OUT")
      (footprint "eagle-import:TEMP-PAD")
      (libsource (lib "eagle-import") (part "PIC-OUT"))
    )
    (comp (ref "O25")
      (value "PIC-OUT")
      (footprint "eagle-import:TEMP-PAD")
      (libsource (lib "eagle-import") (part "PIC-OUT"))
    )
    (comp (ref "O26")
      (value "PIC-OUT")
      (footprint "eagle-import:TEMP-PAD")
      (libsource (lib "eagle-import") (part "PIC-OUT"))
    )
    (comp (ref "O27")
      (value "PIC-RPX")
      (footprint "eagle-import:TEMP-PAD")
      (libsource (lib "eagle-import") (part "PIC-RPX"))
    )
    (comp (ref "O28")
      (value "PIC-RPX")
      (footprint "eagle-import:TEMP-PAD")
      (libsource (lib "eagle-import") (part "PIC-RPX"))
    )
    (comp (ref "O29")
      (value "PIC-RPX")
      (footprint "eagle-import:TEMP-PAD")
      (libsource (lib "eagle-import") (part "PIC-RPX"))
    )
    (comp (ref "O30")
      (value "PIC-RPX")
      (footprint "eagle-import:TEMP-PAD")
      (libsource (lib "eagle-import") (part "PIC-RPX"))
    )
    (comp (ref "O31")
      (value "PIC-OUT")
      (footprint "eagle-import:TEMP-PAD")
      (libsource (lib "eagle-import") (part "PIC-OUT"))
    )
    (comp (ref "O32")
      (value "PIC-OUT")
      (footprint "eagle-import:TEMP-PAD")
      (libsource (lib "eagle-import") (part "PIC-OUT"))
    )
    (comp (ref "O33")
      (value "PIC-RPX")
      (footprint "eagle-import:TEMP-PAD")
      (libsource (lib "eagle-import") (part "PIC-RPX"))
    )
    (comp (ref "O34")
      (value "PIC-RPX")
      (footprint "eagle-import:TEMP-PAD")
      (libsource (lib "eagle-import") (part "PIC-RPX"))
    )
    (comp (ref "O35")
      (value "PIC-RPX")
      (footprint "eagle-import:TEMP-PAD")
      (libsource (lib "eagle-import") (part "PIC-RPX"))
    )
    (comp (ref "O36")
      (value "PIC-RPX")
      (footprint "eagle-import:TEMP-PAD")
      (libsource (lib "eagle-import") (part "PIC-RPX"))
    )
    (comp (ref "O37")
      (value "PIC-RPX")
      (footprint "eagle-import:TEMP-PAD")
      (libsource (lib "eagle-import") (part "PIC-RPX"))
    )
    (comp (ref "O38")
      (value "PIC-RPX")
      (footprint "eagle-import:TEMP-PAD")
      (libsource (lib "eagle-import") (part "PIC-RPX"))
    )
    (comp (ref "O39")
      (value "PIC-OUT")
      (footprint "eagle-import:TEMP-PAD")
      (libsource (lib "eagle-import") (part "PIC-OUT"))
    )
    (comp (ref "O40")
      (value "PIC-OUT")
      (footprint "eagle-import:TEMP-PAD")
      (libsource (lib "eagle-import") (part "PIC-OUT"))
    )
    (comp (ref "O41")
      (value "PIC-RPX")
      (footprint "eagle-import:TEMP-PAD")
      (libsource (lib "eagle-import") (part "PIC-RPX"))
    )
    (comp (ref "O42")
      (value "PIC-RPX")
      (footprint "eagle-import:TEMP-PAD")
      (libsource (lib "eagle-import") (part "PIC-RPX"))
    )
    (comp (ref "O43")
      (value "PIC-RPX")
      (footprint "eagle-import:TEMP-PAD")
      (libsource (lib "eagle-import") (part "PIC-RPX"))
    )
    (comp (ref "O44")
      (value "PIC-OUT")
      (footprint "eagle-import:TEMP-PAD")
      (libsource (lib "eagle-import") (part "PIC-OUT"))
    )
    (comp (ref "PCB1")
      (value "PCB-ACB")
      (footprint "eagle-import:PCB-ACB")
      (libsource (lib "eagle-import") (part "PCB-ACB-1"))
    )
    (comp (ref "PCB2")
      (value "DNP-PCB-VPS")
      (footprint "eagle-import:PCB-VPS")
      (libsource (lib "eagle-import") (part "PCB-VPS-1"))
    )
    (comp (ref "PCB3")
      (value "DNP-PCB-BT")
      (footprint "eagle-import:BT_MODULE_BRD")
      (libsource (lib "eagle-import") (part "BT_PCBBRD"))
    )
    (comp (ref "Q1")
      (value "SSM6P49NU,LFPZ")
      (footprint "eagle-import:MICRO_FET")
      (libsource (lib "eagle-import") (part "SSM6P49PZNU,LF"))
    )
    (comp (ref "Q2")
      (value "SSM6P49NU,LFPZ")
      (footprint "eagle-import:MICRO_FET")
      (libsource (lib "eagle-import") (part "SSM6P49PZNU,LF"))
    )
    (comp (ref "Q3")
      (value "FDG6303N")
      (footprint "eagle-import:SC70-6")
      (libsource (lib "eagle-import") (part "FDG6303N"))
    )
    (comp (ref "Q4")
      (value "FDG6303N")
      (footprint "eagle-import:SC70-6")
      (libsource (lib "eagle-import") (part "FDG6303N"))
    )
    (comp (ref "Q5")
      (value "FDC6506P")
      (footprint "eagle-import:SSOT-6")
      (libsource (lib "eagle-import") (part "FDC6506D"))
    )
    (comp (ref "Q6")
      (value "FDC6506P")
      (footprint "eagle-import:SSOT-6")
      (libsource (lib "eagle-import") (part "FDC6506D"))
    )
    (comp (ref "Q7")
      (value "FDG6303N")
      (footprint "eagle-import:SC70-6")
      (libsource (lib "eagle-import") (part "FDG6303N"))
    )
    (comp (ref "Q8")
      (value "FDC6506P")
      (footprint "eagle-import:SSOT-6")
      (libsource (lib "eagle-import") (part "FDC6506D"))
    )
    (comp (ref "Q9")
      (value "FDG6303N")
      (footprint "eagle-import:SC70-6")
      (libsource (lib "eagle-import") (part "FDG6303N"))
    )
    (comp (ref "Q10")
      (value "FDG6303N")
      (footprint "eagle-import:SC70-6")
      (libsource (lib "eagle-import") (part "FDG6303N"))
    )
    (comp (ref "Q11")
      (value "FDG6303N")
      (footprint "eagle-import:SC70-6")
      (libsource (lib "eagle-import") (part "FDG6303N"))
    )
    (comp (ref "Q12")
      (value "FDG6303N")
      (footprint "eagle-import:SC70-6")
      (libsource (lib "eagle-import") (part "FDG6303N"))
    )
    (comp (ref "Q13")
      (value "FDG6303N")
      (footprint "eagle-import:SC70-6")
      (libsource (lib "eagle-import") (part "FDG6303N"))
    )
    (comp (ref "Q14")
      (value "FDG6303N")
      (footprint "eagle-import:SC70-6")
      (libsource (lib "eagle-import") (part "FDG6303N"))
    )
    (comp (ref "R1")
      (value "1M")
      (footprint "eagle-import:0603")
      (libsource (lib "eagle-import") (part "R-0603"))
    )
    (comp (ref "R2")
      (value "1M")
      (footprint "eagle-import:0603")
      (libsource (lib "eagle-import") (part "R-0603"))
    )
    (comp (ref "R3")
      (value "1M")
      (footprint "eagle-import:0603")
      (libsource (lib "eagle-import") (part "R-0603"))
    )
    (comp (ref "R4")
      (value "1M")
      (footprint "eagle-import:0603")
      (libsource (lib "eagle-import") (part "R-0603"))
    )
    (comp (ref "R5")
      (value "1M")
      (footprint "eagle-import:0603")
      (libsource (lib "eagle-import") (part "R-0603"))
    )
    (comp (ref "R6")
      (value "0R")
      (footprint "eagle-import:0603")
      (libsource (lib "eagle-import") (part "R-0603"))
    )
    (comp (ref "R7")
      (value "0R")
      (footprint "eagle-import:0603")
      (libsource (lib "eagle-import") (part "R-0603"))
    )
    (comp (ref "R8")
      (value "1R")
      (footprint "eagle-import:0805")
      (libsource (lib "eagle-import") (part "R-0805"))
    )
    (comp (ref "R9")
      (value "1M")
      (footprint "eagle-import:0603")
      (libsource (lib "eagle-import") (part "R-0603"))
    )
    (comp (ref "R10")
      (value "100k")
      (footprint "eagle-import:0603")
      (libsource (lib "eagle-import") (part "R-0603"))
    )
    (comp (ref "R11")
      (value "10k")
      (footprint "eagle-import:0603")
      (libsource (lib "eagle-import") (part "R-0603"))
    )
    (comp (ref "R12")
      (value "100k")
      (footprint "eagle-import:0603")
      (libsource (lib "eagle-import") (part "R-0603"))
    )
    (comp (ref "R13")
      (value "10k")
      (footprint "eagle-import:0603")
      (libsource (lib "eagle-import") (part "R-0603"))
    )
    (comp (ref "R14")
      (value "10k")
      (footprint "eagle-import:0603")
      (libsource (lib "eagle-import") (part "R-0603"))
    )
    (comp (ref "R15")
      (value "10k")
      (footprint "eagle-import:0603")
      (libsource (lib "eagle-import") (part "R-0603"))
    )
    (comp (ref "R16")
      (value "100k")
      (footprint "eagle-import:0603")
      (libsource (lib "eagle-import") (part "R-0603"))
    )
    (comp (ref "R17")
      (value "47k")
      (footprint "eagle-import:0603")
      (libsource (lib "eagle-import") (part "R-0603"))
    )
    (comp (ref "R18")
      (value "10k")
      (footprint "eagle-import:0603")
      (libsource (lib "eagle-import") (part "R-0603"))
    )
    (comp (ref "R19")
      (value "560k")
      (footprint "eagle-import:0603")
      (libsource (lib "eagle-import") (part "R-0603"))
    )
    (comp (ref "R20")
      (value "1M")
      (footprint "eagle-import:0603")
      (libsource (lib "eagle-import") (part "R-0603"))
    )
    (comp (ref "R21")
      (value "1M")
      (footprint "eagle-import:0603")
      (libsource (lib "eagle-import") (part "R-0603"))
    )
    (comp (ref "R22")
      (value "4M99")
      (footprint "eagle-import:0603")
      (libsource (lib "eagle-import") (part "R-0603"))
    )
    (comp (ref "R23")
      (value "1M")
      (footprint "eagle-import:0603")
      (libsource (lib "eagle-import") (part "R-0603"))
    )
    (comp (ref "R24")
      (value "100k")
      (footprint "eagle-import:0603")
      (libsource (lib "eagle-import") (part "R-0603"))
    )
    (comp (ref "R25")
      (value "1M")
      (footprint "eagle-import:0603")
      (libsource (lib "eagle-import") (part "R-0603"))
    )
    (comp (ref "R26")
      (value "10k")
      (footprint "eagle-import:0603")
      (libsource (lib "eagle-import") (part "R-0603"))
    )
    (comp (ref "R27")
      (value "10k")
      (footprint "eagle-import:0603")
      (libsource (lib "eagle-import") (part "R-0603"))
    )
    (comp (ref "R28")
      (value "100R")
      (footprint "eagle-import:0603")
      (libsource (lib "eagle-import") (part "R-0603"))
    )
    (comp (ref "R29")
      (value "300R")
      (footprint "eagle-import:0603")
      (libsource (lib "eagle-import") (part "R-0603"))
    )
    (comp (ref "R30")
      (value "10k")
      (footprint "eagle-import:0603")
      (libsource (lib "eagle-import") (part "R-0603"))
    )
    (comp (ref "R31")
      (value "1M")
      (footprint "eagle-import:0603")
      (libsource (lib "eagle-import") (part "R-0603"))
    )
    (comp (ref "R32")
      (value "1M")
      (footprint "eagle-import:0603")
      (libsource (lib "eagle-import") (part "R-0603"))
    )
    (comp (ref "R33")
      (value "4M99")
      (footprint "eagle-import:0603")
      (libsource (lib "eagle-import") (part "R-0603"))
    )
    (comp (ref "R34")
      (value "1M")
      (footprint "eagle-import:0603")
      (libsource (lib "eagle-import") (part "R-0603"))
    )
    (comp (ref "R35")
      (value "1k")
      (footprint "eagle-import:0805")
      (libsource (lib "eagle-import") (part "R-0805"))
    )
    (comp (ref "R36")
      (value "1k")
      (footprint "eagle-import:0805")
      (libsource (lib "eagle-import") (part "R-0805"))
    )
    (comp (ref "R37")
      (value "1k")
      (footprint "eagle-import:0805")
      (libsource (lib "eagle-import") (part "R-0805"))
    )
    (comp (ref "R38")
      (value "1k")
      (footprint "eagle-import:0805")
      (libsource (lib "eagle-import") (part "R-0805"))
    )
    (comp (ref "R39")
      (value "0.025R")
      (footprint "eagle-import:0805")
      (libsource (lib "eagle-import") (part "R-0805"))
    )
    (comp (ref "R40")
      (value "300k")
      (footprint "eagle-import:0603")
      (libsource (lib "eagle-import") (part "R-0603"))
    )
    (comp (ref "R41")
      (value "1M")
      (footprint "eagle-import:0603")
      (libsource (lib "eagle-import") (part "R-0603"))
    )
    (comp (ref "R42")
      (value "1M")
      (footprint "eagle-import:0603")
      (libsource (lib "eagle-import") (part "R-0603"))
    )
    (comp (ref "R43")
      (value "300k")
      (footprint "eagle-import:0603")
      (libsource (lib "eagle-import") (part "R-0603"))
    )
    (comp (ref "R44")
      (value "1M")
      (footprint "eagle-import:0603")
      (libsource (lib "eagle-import") (part "R-0603"))
    )
    (comp (ref "R45")
      (value "1M")
      (footprint "eagle-import:0603")
      (libsource (lib "eagle-import") (part "R-0603"))
    )
    (comp (ref "R46")
      (value "560k->750k")
      (footprint "eagle-import:0603")
      (libsource (lib "eagle-import") (part "R-0603"))
    )
    (comp (ref "R47")
      (value "100k->180k")
      (footprint "eagle-import:0603")
      (libsource (lib "eagle-import") (part "R-0603"))
    )
    (comp (ref "R48")
      (value "1M")
      (footprint "eagle-import:0603")
      (libsource (lib "eagle-import") (part "R-0603"))
    )
    (comp (ref "R49")
      (value "560k")
      (footprint "eagle-import:0603")
      (libsource (lib "eagle-import") (part "R-0603"))
    )
    (comp (ref "R50")
      (value "1M")
      (footprint "eagle-import:0603")
      (libsource (lib "eagle-import") (part "R-0603"))
    )
    (comp (ref "R51")
      (value "300k")
      (footprint "eagle-import:0603")
      (libsource (lib "eagle-import") (part "R-0603"))
    )
    (comp (ref "R52")
      (value "1M")
      (footprint "eagle-import:0603")
      (libsource (lib "eagle-import") (part "R-0603"))
    )
    (comp (ref "R53")
      (value "300k")
      (footprint "eagle-import:0603")
      (libsource (lib "eagle-import") (part "R-0603"))
    )
    (comp (ref "R54")
      (value "1M")
      (footprint "eagle-import:0603")
      (libsource (lib "eagle-import") (part "R-0603"))
    )
    (comp (ref "R55")
      (value "1M")
      (footprint "eagle-import:0603")
      (libsource (lib "eagle-import") (part "R-0603"))
    )
    (comp (ref "R56")
      (value "1M")
      (footprint "eagle-import:0603")
      (libsource (lib "eagle-import") (part "R-0603"))
    )
    (comp (ref "R57")
      (value "300k")
      (footprint "eagle-import:0603")
      (libsource (lib "eagle-import") (part "R-0603"))
    )
    (comp (ref "R58")
      (value "1M")
      (footprint "eagle-import:0603")
      (libsource (lib "eagle-import") (part "R-0603"))
    )
    (comp (ref "R59")
      (value "300k")
      (footprint "eagle-import:0603")
      (libsource (lib "eagle-import") (part "R-0603"))
    )
    (comp (ref "R60")
      (value "1M")
      (footprint "eagle-import:0603")
      (libsource (lib "eagle-import") (part "R-0603"))
    )
    (comp (ref "R61")
      (value "1M")
      (footprint "eagle-import:0603")
      (libsource (lib "eagle-import") (part "R-0603"))
    )
    (comp (ref "R62")
      (value "100R")
      (footprint "eagle-import:0603")
      (libsource (lib "eagle-import") (part "R-0603"))
    )
    (comp (ref "R63")
      (value "1k->4k7")
      (footprint "eagle-import:0603")
      (libsource (lib "eagle-import") (part "R-0603"))
    )
    (comp (ref "R64")
      (value "1k")
      (footprint "eagle-import:0603")
      (libsource (lib "eagle-import") (part "R-0603"))
    )
    (comp (ref "R65")
      (value "1M")
      (footprint "eagle-import:0603")
      (libsource (lib "eagle-import") (part "R-0603"))
    )
    (comp (ref "R66")
      (value "100k")
      (footprint "eagle-import:0603")
      (libsource (lib "eagle-import") (part "R-0603"))
    )
    (comp (ref "R67")
      (value "1M")
      (footprint "eagle-import:0603")
      (libsource (lib "eagle-import") (part "R-0603"))
    )
    (comp (ref "R68")
      (value "100R")
      (footprint "eagle-import:0603")
      (libsource (lib "eagle-import") (part "R-0603"))
    )
    (comp (ref "R69")
      (value "1k->4k7")
      (footprint "eagle-import:0603")
      (libsource (lib "eagle-import") (part "R-0603"))
    )
    (comp (ref "R70")
      (value "1k")
      (footprint "eagle-import:0603")
      (libsource (lib "eagle-import") (part "R-0603"))
    )
    (comp (ref "R71")
      (value "10k")
      (footprint "eagle-import:0603")
      (libsource (lib "eagle-import") (part "R-0603"))
    )
    (comp (ref "R72")
      (value "1M")
      (footprint "eagle-import:0603")
      (libsource (lib "eagle-import") (part "R-0603"))
    )
    (comp (ref "R73")
      (value "1M")
      (footprint "eagle-import:0603")
      (libsource (lib "eagle-import") (part "R-0603"))
    )
    (comp (ref "R74")
      (value "100k")
      (footprint "eagle-import:0603")
      (libsource (lib "eagle-import") (part "R-0603"))
    )
    (comp (ref "R75")
      (value "100k")
      (footprint "eagle-import:0603")
      (libsource (lib "eagle-import") (part "R-0603"))
    )
    (comp (ref "R76")
      (value "1M")
      (footprint "eagle-import:0603")
      (libsource (lib "eagle-import") (part "R-0603"))
    )
    (comp (ref "R77")
      (value "47k")
      (footprint "eagle-import:0603")
      (libsource (lib "eagle-import") (part "R-0603"))
    )
    (comp (ref "R78")
      (value "100R")
      (footprint "eagle-import:0603")
      (libsource (lib "eagle-import") (part "R-0603"))
    )
    (comp (ref "R79")
      (value "1k->4k7")
      (footprint "eagle-import:0603")
      (libsource (lib "eagle-import") (part "R-0603"))
    )
    (comp (ref "R80")
      (value "1k")
      (footprint "eagle-import:0603")
      (libsource (lib "eagle-import") (part "R-0603"))
    )
    (comp (ref "R81")
      (value "100k")
      (footprint "eagle-import:0603")
      (libsource (lib "eagle-import") (part "R-0603"))
    )
    (comp (ref "R82")
      (value "1M")
      (footprint "eagle-import:0603")
      (libsource (lib "eagle-import") (part "R-0603"))
    )
    (comp (ref "R83")
      (value "1M")
      (footprint "eagle-import:0603")
      (libsource (lib "eagle-import") (part "R-0603"))
    )
    (comp (ref "R84")
      (value "100R")
      (footprint "eagle-import:0603")
      (libsource (lib "eagle-import") (part "R-0603"))
    )
    (comp (ref "R85")
      (value "1k->4k7")
      (footprint "eagle-import:0603")
      (libsource (lib "eagle-import") (part "R-0603"))
    )
    (comp (ref "R86")
      (value "1k")
      (footprint "eagle-import:0603")
      (libsource (lib "eagle-import") (part "R-0603"))
    )
    (comp (ref "R87")
      (value "1M")
      (footprint "eagle-import:0603")
      (libsource (lib "eagle-import") (part "R-0603"))
    )
    (comp (ref "R88")
      (value "1M")
      (footprint "eagle-import:0603")
      (libsource (lib "eagle-import") (part "R-0603"))
    )
    (comp (ref "R89")
      (value "100k")
      (footprint "eagle-import:0603")
      (libsource (lib "eagle-import") (part "R-0603"))
    )
    (comp (ref "R90")
      (value "1k")
      (footprint "eagle-import:0603")
      (libsource (lib "eagle-import") (part "R-0603"))
    )
    (comp (ref "R91")
      (value "10k")
      (footprint "eagle-import:0603")
      (libsource (lib "eagle-import") (part "R-0603"))
    )
    (comp (ref "R92")
      (value "10R")
      (footprint "eagle-import:0603")
      (libsource (lib "eagle-import") (part "R-0603"))
    )
    (comp (ref "R93")
      (value "300R")
      (footprint "eagle-import:0603")
      (libsource (lib "eagle-import") (part "R-0603"))
    )
    (comp (ref "R94")
      (value "180k")
      (footprint "eagle-import:0603")
      (libsource (lib "eagle-import") (part "R-0603"))
    )
    (comp (ref "R95")
      (value "4M99")
      (footprint "eagle-import:0603")
      (libsource (lib "eagle-import") (part "R-0603"))
    )
    (comp (ref "R96")
      (value "560k")
      (footprint "eagle-import:0603")
      (libsource (lib "eagle-import") (part "R-0603"))
    )
    (comp (ref "R97")
      (value "180k")
      (footprint "eagle-import:0603")
      (libsource (lib "eagle-import") (part "R-0603"))
    )
    (comp (ref "R98")
      (value "4M99")
      (footprint "eagle-import:0603")
      (libsource (lib "eagle-import") (part "R-0603"))
    )
    (comp (ref "R99")
      (value "560k")
      (footprint "eagle-import:0603")
      (libsource (lib "eagle-import") (part "R-0603"))
    )
    (comp (ref "R100")
      (value "2k2")
      (footprint "eagle-import:0603")
      (libsource (lib "eagle-import") (part "R-0603"))
    )
    (comp (ref "R101")
      (value "2k2")
      (footprint "eagle-import:0603")
      (libsource (lib "eagle-import") (part "R-0603"))
    )
    (comp (ref "R102")
      (value "1k")
      (footprint "eagle-import:0603")
      (libsource (lib "eagle-import") (part "R-0603"))
    )
    (comp (ref "R103")
      (value "300R")
      (footprint "eagle-import:0603")
      (libsource (lib "eagle-import") (part "R-0603"))
    )
    (comp (ref "R104")
      (value "1R")
      (footprint "eagle-import:0805")
      (libsource (lib "eagle-import") (part "R-0805"))
    )
    (comp (ref "R105")
      (value "1R")
      (footprint "eagle-import:0805")
      (libsource (lib "eagle-import") (part "R-0805"))
    )
    (comp (ref "R106")
      (value "1R")
      (footprint "eagle-import:0805")
      (libsource (lib "eagle-import") (part "R-0805"))
    )
    (comp (ref "R107")
      (value "100k")
      (footprint "eagle-import:0603")
      (libsource (lib "eagle-import") (part "R-0603"))
    )
    (comp (ref "R110")
      (value "100R")
      (footprint "eagle-import:0603")
      (libsource (lib "eagle-import") (part "R-0603"))
    )
    (comp (ref "R111")
      (value "100R")
      (footprint "eagle-import:0603")
      (libsource (lib "eagle-import") (part "R-0603"))
    )
    (comp (ref "R112")
      (value "1M")
      (footprint "eagle-import:0603")
      (libsource (lib "eagle-import") (part "R-0603"))
    )
    (comp (ref "R113")
      (value "100R")
      (footprint "eagle-import:0603")
      (libsource (lib "eagle-import") (part "R-0603"))
    )
    (comp (ref "R114")
      (value "100R")
      (footprint "eagle-import:0603")
      (libsource (lib "eagle-import") (part "R-0603"))
    )
    (comp (ref "R115")
      (value "100R")
      (footprint "eagle-import:0603")
      (libsource (lib "eagle-import") (part "R-0603"))
    )
    (comp (ref "R116")
      (value "100R")
      (footprint "eagle-import:0603")
      (libsource (lib "eagle-import") (part "R-0603"))
    )
    (comp (ref "R117")
      (value "100R")
      (footprint "eagle-import:0603")
      (libsource (lib "eagle-import") (part "R-0603"))
    )
    (comp (ref "R118")
      (value "1M")
      (footprint "eagle-import:0603")
      (libsource (lib "eagle-import") (part "R-0603"))
    )
    (comp (ref "R119")
      (value "100R")
      (footprint "eagle-import:0603")
      (libsource (lib "eagle-import") (part "R-0603"))
    )
    (comp (ref "R122")
      (value "100R")
      (footprint "eagle-import:0603")
      (libsource (lib "eagle-import") (part "R-0603"))
    )
    (comp (ref "R123")
      (value "100R")
      (footprint "eagle-import:0603")
      (libsource (lib "eagle-import") (part "R-0603"))
    )
    (comp (ref "R124")
      (value "0R")
      (footprint "eagle-import:0603")
      (libsource (lib "eagle-import") (part "R-0603"))
    )
    (comp (ref "R125")
      (value "0R")
      (footprint "eagle-import:0603")
      (libsource (lib "eagle-import") (part "R-0603"))
    )
    (comp (ref "R126")
      (value "0R")
      (footprint "eagle-import:0603")
      (libsource (lib "eagle-import") (part "R-0603"))
    )
    (comp (ref "R127")
      (value "1M")
      (footprint "eagle-import:0603")
      (libsource (lib "eagle-import") (part "R-0603"))
    )
    (comp (ref "R128")
      (value "10k")
      (footprint "eagle-import:0603")
      (libsource (lib "eagle-import") (part "R-0603"))
    )
    (comp (ref "R129")
      (value "DNP/0R")
      (footprint "eagle-import:0603")
      (libsource (lib "eagle-import") (part "R-0603"))
    )
    (comp (ref "R130")
      (value "100k")
      (footprint "eagle-import:0603")
      (libsource (lib "eagle-import") (part "R-0603"))
    )
    (comp (ref "R131")
      (value "100k")
      (footprint "eagle-import:0603")
      (libsource (lib "eagle-import") (part "R-0603"))
    )
    (comp (ref "R132")
      (value "1M")
      (footprint "eagle-import:0603")
      (libsource (lib "eagle-import") (part "R-0603"))
    )
    (comp (ref "REF1")
      (value "REF")
      (footprint "eagle-import:REF")
      (libsource (lib "eagle-import") (part "REF"))
    )
    (comp (ref "REF2")
      (value "REF")
      (footprint "eagle-import:REF")
      (libsource (lib "eagle-import") (part "REF"))
    )
    (comp (ref "T1")
      (value "PIC-OUT")
      (footprint "eagle-import:TEMP-PAD")
      (libsource (lib "eagle-import") (part "PIC-OUT"))
    )
    (comp (ref "T2")
      (value "PIC-OUT")
      (footprint "eagle-import:TEMP-PAD")
      (libsource (lib "eagle-import") (part "PIC-OUT"))
    )
    (comp (ref "T3")
      (value "PIC-RPX")
      (footprint "eagle-import:TEMP-PAD")
      (libsource (lib "eagle-import") (part "PIC-RPX"))
    )
    (comp (ref "T4")
      (value "PIC-OUT")
      (footprint "eagle-import:TEMP-PAD")
      (libsource (lib "eagle-import") (part "PIC-OUT"))
    )
    (comp (ref "T5")
      (value "PIC-OUT")
      (footprint "eagle-import:TEMP-PAD")
      (libsource (lib "eagle-import") (part "PIC-OUT"))
    )
    (comp (ref "T6")
      (value "PIC-OUT")
      (footprint "eagle-import:TEMP-PAD")
      (libsource (lib "eagle-import") (part "PIC-OUT"))
    )
    (comp (ref "T7")
      (value "PIC-OUT")
      (footprint "eagle-import:TEMP-PAD")
      (libsource (lib "eagle-import") (part "PIC-OUT"))
    )
    (comp (ref "T8")
      (value "PIC-OUT")
      (footprint "eagle-import:TEMP-PAD")
      (libsource (lib "eagle-import") (part "PIC-OUT"))
    )
    (comp (ref "T9")
      (value "PIC-RPX")
      (footprint "eagle-import:TEMP-PAD")
      (libsource (lib "eagle-import") (part "PIC-RPX"))
    )
    (comp (ref "T10")
      (value "PIC-RPX")
      (footprint "eagle-import:TEMP-PAD")
      (libsource (lib "eagle-import") (part "PIC-RPX"))
    )
    (comp (ref "T11")
      (value "PIC-RPX")
      (footprint "eagle-import:TEMP-PAD")
      (libsource (lib "eagle-import") (part "PIC-RPX"))
    )
    (comp (ref "T12")
      (value "PIC-RPX")
      (footprint "eagle-import:TEMP-PAD")
      (libsource (lib "eagle-import") (part "PIC-RPX"))
    )
    (comp (ref "T13")
      (value "PIC-RPX")
      (footprint "eagle-import:TEMP-PAD")
      (libsource (lib "eagle-import") (part "PIC-RPX"))
    )
    (comp (ref "T14")
      (value "PIC-RPX")
      (footprint "eagle-import:TEMP-PAD")
      (libsource (lib "eagle-import") (part "PIC-RPX"))
    )
    (comp (ref "T15")
      (value "PIC-OUT")
      (footprint "eagle-import:TEMP-PAD")
      (libsource (lib "eagle-import") (part "PIC-OUT"))
    )
    (comp (ref "T16")
      (value "PIC-RPX")
      (footprint "eagle-import:TEMP-PAD")
      (libsource (lib "eagle-import") (part "PIC-RPX"))
    )
    (comp (ref "T17")
      (value "PIC-RPX")
      (footprint "eagle-import:TEMP-PAD")
      (libsource (lib "eagle-import") (part "PIC-RPX"))
    )
    (comp (ref "T18")
      (value "PIC-RPX")
      (footprint "eagle-import:TEMP-PAD")
      (libsource (lib "eagle-import") (part "PIC-RPX"))
    )
    (comp (ref "T19")
      (value "PIC-RPX")
      (footprint "eagle-import:TEMP-PAD")
      (libsource (lib "eagle-import") (part "PIC-RPX"))
    )
    (comp (ref "T20")
      (value "PIC-OUT")
      (footprint "eagle-import:TEMP-PAD")
      (libsource (lib "eagle-import") (part "PIC-OUT"))
    )
    (comp (ref "T21")
      (value "PIC-OUT")
      (footprint "eagle-import:TEMP-PAD")
      (libsource (lib "eagle-import") (part "PIC-OUT"))
    )
    (comp (ref "T22")
      (value "PIC-RPX")
      (footprint "eagle-import:TEMP-PAD")
      (libsource (lib "eagle-import") (part "PIC-RPX"))
    )
    (comp (ref "T23")
      (value "PIC-RPX")
      (footprint "eagle-import:TEMP-PAD")
      (libsource (lib "eagle-import") (part "PIC-RPX"))
    )
    (comp (ref "T24")
      (value "PIC-RPX")
      (footprint "eagle-import:TEMP-PAD")
      (libsource (lib "eagle-import") (part "PIC-RPX"))
    )
    (comp (ref "T25")
      (value "PIC-OUT")
      (footprint "eagle-import:TEMP-PAD")
      (libsource (lib "eagle-import") (part "PIC-OUT"))
    )
    (comp (ref "T26")
      (value "PIC-OUT")
      (footprint "eagle-import:TEMP-PAD")
      (libsource (lib "eagle-import") (part "PIC-OUT"))
    )
    (comp (ref "T27")
      (value "PIC-OUT")
      (footprint "eagle-import:TEMP-PAD")
      (libsource (lib "eagle-import") (part "PIC-OUT"))
    )
    (comp (ref "T28")
      (value "PIC-OUT")
      (footprint "eagle-import:TEMP-PAD")
      (libsource (lib "eagle-import") (part "PIC-OUT"))
    )
    (comp (ref "T29")
      (value "PIC-OUT")
      (footprint "eagle-import:TEMP-PAD")
      (libsource (lib "eagle-import") (part "PIC-OUT"))
    )
    (comp (ref "T30")
      (value "PIC-OUT")
      (footprint "eagle-import:TEMP-PAD")
      (libsource (lib "eagle-import") (part "PIC-OUT"))
    )
    (comp (ref "T31")
      (value "PIC-OUT")
      (footprint "eagle-import:TEMP-PAD")
      (libsource (lib "eagle-import") (part "PIC-OUT"))
    )
    (comp (ref "T32")
      (value "PIC-OUT")
      (footprint "eagle-import:TEMP-PAD")
      (libsource (lib "eagle-import") (part "PIC-OUT"))
    )
    (comp (ref "T33")
      (value "PIC-OUT")
      (footprint "eagle-import:TEMP-PAD")
      (libsource (lib "eagle-import") (part "PIC-OUT"))
    )
    (comp (ref "T34")
      (value "PIC-RPX")
      (footprint "eagle-import:TEMP-PAD")
      (libsource (lib "eagle-import") (part "PIC-RPX"))
    )
    (comp (ref "T35")
      (value "PIC-RPX")
      (footprint "eagle-import:TEMP-PAD")
      (libsource (lib "eagle-import") (part "PIC-RPX"))
    )
    (comp (ref "T36")
      (value "PIC-OUT")
      (footprint "eagle-import:TEMP-PAD")
      (libsource (lib "eagle-import") (part "PIC-OUT"))
    )
    (comp (ref "T37")
      (value "PIN-AN")
      (footprint "eagle-import:TEMP-PAD")
      (libsource (lib "eagle-import") (part "PIN-AN"))
    )
    (comp (ref "T38")
      (value "PIN-AN")
      (footprint "eagle-import:TEMP-PAD")
      (libsource (lib "eagle-import") (part "PIN-AN"))
    )
    (comp (ref "T39")
      (value "PIN-AN")
      (footprint "eagle-import:TEMP-PAD")
      (libsource (lib "eagle-import") (part "PIN-AN"))
    )
    (comp (ref "T40")
      (value "PIC-RPX")
      (footprint "eagle-import:TEMP-PAD")
      (libsource (lib "eagle-import") (part "PIC-RPX"))
    )
    (comp (ref "T41")
      (value "PIC-RPX")
      (footprint "eagle-import:TEMP-PAD")
      (libsource (lib "eagle-import") (part "PIC-RPX"))
    )
    (comp (ref "T42")
      (value "PIC-OUT")
      (footprint "eagle-import:TEMP-PAD")
      (libsource (lib "eagle-import") (part "PIC-OUT"))
    )
    (comp (ref "T43")
      (value "PIC-RPX")
      (footprint "eagle-import:TEMP-PAD")
      (libsource (lib "eagle-import") (part "PIC-RPX"))
    )
    (comp (ref "T44")
      (value "PIC-OUT")
      (footprint "eagle-import:TEMP-PAD")
      (libsource (lib "eagle-import") (part "PIC-OUT"))
    )
    (comp (ref "T45")
      (value "PIC-RPX")
      (footprint "eagle-import:TEMP-PAD")
      (libsource (lib "eagle-import") (part "PIC-RPX"))
    )
    (comp (ref "T46")
      (value "PIC-RPX")
      (footprint "eagle-import:TEMP-PAD")
      (libsource (lib "eagle-import") (part "PIC-RPX"))
    )
    (comp (ref "TP1")
      (value "DNP-TestPoint")
      (footprint "eagle-import:SMD_ROUND_1MM")
      (libsource (lib "eagle-import") (part "ROUND_SMD1MM"))
    )
    (comp (ref "TP2")
      (value "DNP-TestPoint")
      (footprint "eagle-import:TH_ROUND_14MM08MM")
      (libsource (lib "eagle-import") (part "ROUND_SMDTH1.4MM"))
    )
    (comp (ref "TP4")
      (value "DNP-TestPoint")
      (footprint "eagle-import:TH_ROUND_14MM08MM")
      (libsource (lib "eagle-import") (part "ROUND_SMDTH1.4MM"))
    )
    (comp (ref "X1")
      (value "8MHz-5x3.2mm")
      (footprint "eagle-import:7B")
      (libsource (lib "eagle-import") (part "XTAL-7B"))
    )
  )
  (nets
    (net (code "1") (name "+3.3V") (class "Default")
      (node (ref "C15") (pin "1") (pinfunction "1_1") (pintype "passive"))
      (node (ref "C21") (pin "1") (pinfunction "1_1") (pintype "passive"))
      (node (ref "C47") (pin "1") (pinfunction "1_1") (pintype "passive"))
      (node (ref "C48") (pin "1") (pinfunction "1_1") (pintype "passive"))
      (node (ref "C49") (pin "1") (pinfunction "1_1") (pintype "passive"))
      (node (ref "C50") (pin "1") (pinfunction "1_1") (pintype "passive"))
      (node (ref "C51") (pin "1") (pinfunction "1_1") (pintype "passive"))
      (node (ref "C52") (pin "1") (pinfunction "1_1") (pintype "passive"))
      (node (ref "C68") (pin "1") (pinfunction "1_1") (pintype "passive"))
      (node (ref "C69") (pin "1") (pinfunction "1_1") (pintype "passive"))
      (node (ref "C70") (pin "1") (pinfunction "1_1") (pintype "passive"))
      (node (ref "C81") (pin "+") (pinfunction "+_+") (pintype "passive"))
      (node (ref "IC1") (pin "16") (pinfunction "VDD3_16") (pintype "input"))
      (node (ref "IC1") (pin "2") (pinfunction "VDD2_2") (pintype "input"))
      (node (ref "IC1") (pin "37") (pinfunction "VDD4_37") (pintype "input"))
      (node (ref "IC1") (pin "46") (pinfunction "VDD5_46") (pintype "input"))
      (node (ref "IC1") (pin "55") (pinfunction "VUSB3V3_55") (pintype "input"))
      (node (ref "IC1") (pin "62") (pinfunction "VDD6_62") (pintype "input"))
      (node (ref "IC1") (pin "86") (pinfunction "VDD1_86") (pintype "input"))
      (node (ref "J14") (pin "2") (pinfunction "2_2") (pintype "passive"))
      (node (ref "J17") (pin "2") (pinfunction "2_2") (pintype "passive"))
      (node (ref "L13") (pin "1") (pinfunction "1_1") (pintype "passive"))
      (node (ref "R103") (pin "2") (pinfunction "2_2") (pintype "passive"))
      (node (ref "R104") (pin "2") (pinfunction "2_2") (pintype "passive"))
      (node (ref "R105") (pin "2") (pinfunction "2_2") (pintype "passive"))
      (node (ref "R106") (pin "2") (pinfunction "2_2") (pintype "passive"))
      (node (ref "R129") (pin "1") (pinfunction "1_1") (pintype "passive"))
      (node (ref "R28") (pin "2") (pinfunction "2_2") (pintype "passive"))
      (node (ref "R65") (pin "1") (pinfunction "1_1") (pintype "passive"))
      (node (ref "R66") (pin "2") (pinfunction "2_2") (pintype "passive"))
      (node (ref "R74") (pin "2") (pinfunction "2_2") (pintype "passive"))
      (node (ref "R8") (pin "2") (pinfunction "2_2") (pintype "passive"))
      (node (ref "R81") (pin "2") (pinfunction "2_2") (pintype "passive"))
      (node (ref "R82") (pin "1") (pinfunction "1_1") (pintype "passive"))
      (node (ref "R87") (pin "1") (pinfunction "1_1") (pintype "passive"))
      (node (ref "R89") (pin "2") (pinfunction "2_2") (pintype "passive"))
      (node (ref "R9") (pin "2") (pinfunction "2_2") (pintype "passive"))
      (node (ref "R91") (pin "2") (pinfunction "2_2") (pintype "passive"))
    )
    (net (code "2") (name "+3.3V{slash}1") (class "Default")
      (node (ref "C1") (pin "1") (pinfunction "1_1") (pintype "passive"))
      (node (ref "C2") (pin "1") (pinfunction "1_1") (pintype "passive"))
      (node (ref "C28") (pin "1") (pinfunction "1_1") (pintype "passive"))
      (node (ref "C87") (pin "+") (pinfunction "+_+") (pintype "passive"))
      (node (ref "IC11") (pin "2") (pinfunction "A1_2") (pintype "input"))
      (node (ref "IC11") (pin "8") (pinfunction "VCC_8") (pintype "input"))
      (node (ref "IC2") (pin "37") (pinfunction "VCC_37") (pintype "input"))
      (node (ref "IC3") (pin "20") (pinfunction "VCC_20") (pintype "bidirectional"))
      (node (ref "IC4") (pin "20") (pinfunction "VCC_20") (pintype "bidirectional"))
      (node (ref "IC7") (pin "8") (pinfunction "VCC_8") (pintype "input"))
      (node (ref "Q2") (pin "3") (pinfunction "D_3") (pintype "passive"))
      (node (ref "Q2") (pin "P2") (pinfunction "D1_P2") (pintype "passive"))
      (node (ref "R18") (pin "1") (pinfunction "1_1") (pintype "passive"))
      (node (ref "R26") (pin "1") (pinfunction "1_1") (pintype "passive"))
      (node (ref "R27") (pin "1") (pinfunction "1_1") (pintype "passive"))
      (node (ref "R3") (pin "2") (pinfunction "2_2") (pintype "passive"))
      (node (ref "R4") (pin "2") (pinfunction "2_2") (pintype "passive"))
    )
    (net (code "3") (name "+3.3V{slash}2") (class "Default")
      (node (ref "C41") (pin "1") (pinfunction "1_1") (pintype "passive"))
      (node (ref "C86") (pin "+") (pinfunction "+_+") (pintype "passive"))
      (node (ref "IC12") (pin "8") (pinfunction "VCC_8") (pintype "input"))
      (node (ref "Q1") (pin "3") (pinfunction "D_3") (pintype "passive"))
      (node (ref "Q1") (pin "P2") (pinfunction "D1_P2") (pintype "passive"))
      (node (ref "R30") (pin "2") (pinfunction "2_2") (pintype "passive"))
      (node (ref "R34") (pin "1") (pinfunction "1_1") (pintype "passive"))
      (node (ref "R72") (pin "1") (pinfunction "1_1") (pintype "passive"))
      (node (ref "R73") (pin "2") (pinfunction "2_2") (pintype "passive"))
    )
    (net (code "4") (name "/+3.3V{slash}VPS") (class "Default")
      (node (ref "C27") (pin "1") (pinfunction "1_1") (pintype "passive"))
      (node (ref "C82") (pin "1") (pinfunction "1_1") (pintype "passive"))
      (node (ref "IC9") (pin "3") (pinfunction "/WP_3") (pintype "input"))
      (node (ref "IC9") (pin "7") (pinfunction "/HOLD_7") (pintype "input"))
      (node (ref "IC9") (pin "8") (pinfunction "VCC_8") (pintype "input"))
      (node (ref "J11") (pin "4") (pinfunction "VDD_4") (pintype "passive"))
      (node (ref "J15") (pin "1") (pinfunction "1_1") (pintype "passive"))
      (node (ref "Q2") (pin "6") (pinfunction "D_6") (pintype "passive"))
      (node (ref "Q2") (pin "P1") (pinfunction "D1_P1") (pintype "passive"))
      (node (ref "R25") (pin "2") (pinfunction "2_2") (pintype "passive"))
    )
    (net (code "5") (name "/1.5V-CAM") (class "Default")
      (node (ref "L5") (pin "1") (pinfunction "1_1") (pintype "passive"))
      (node (ref "L6") (pin "2") (pinfunction "2_2") (pintype "passive"))
      (node (ref "R126") (pin "1") (pinfunction "1_1") (pintype "passive"))
    )
    (net (code "6") (name "/3.3V{slash}CAM") (class "Default")
      (node (ref "C16") (pin "+") (pinfunction "+_+") (pintype "passive"))
      (node (ref "C17") (pin "+") (pinfunction "+_+") (pintype "passive"))
      (node (ref "C18") (pin "1") (pinfunction "1_1") (pintype "passive"))
      (node (ref "IC5") (pin "1") (pinfunction "IN_1") (pintype "input"))
      (node (ref "IC5") (pin "3") (pinfunction "EN_3") (pintype "input"))
      (node (ref "L1") (pin "1") (pinfunction "1_1") (pintype "passive"))
      (node (ref "L2") (pin "2") (pinfunction "2_2") (pintype "passive"))
      (node (ref "L3") (pin "1") (pinfunction "1_1") (pintype "passive"))
      (node (ref "L4") (pin "2") (pinfunction "2_2") (pintype "passive"))
      (node (ref "Q1") (pin "6") (pinfunction "D_6") (pintype "passive"))
      (node (ref "Q1") (pin "P1") (pinfunction "D1_P1") (pintype "passive"))
      (node (ref "R11") (pin "2") (pinfunction "2_2") (pintype "passive"))
      (node (ref "R12") (pin "2") (pinfunction "2_2") (pintype "passive"))
      (node (ref "R13") (pin "2") (pinfunction "2_2") (pintype "passive"))
      (node (ref "R14") (pin "2") (pinfunction "2_2") (pintype "passive"))
      (node (ref "R15") (pin "2") (pinfunction "2_2") (pintype "passive"))
      (node (ref "R16") (pin "2") (pinfunction "2_2") (pintype "passive"))
    )
    (net (code "7") (name "/A+") (class "Default")
      (node (ref "IC14") (pin "3") (pinfunction "3_3") (pintype "passive"))
      (node (ref "J3") (pin "4") (pinfunction "4_4") (pintype "passive"))
      (node (ref "J4") (pin "4") (pinfunction "4_4") (pintype "passive"))
      (node (ref "L8") (pin "2") (pinfunction "2_2") (pintype "passive"))
    )
    (net (code "8") (name "/A++") (class "Default")
      (node (ref "IC12") (pin "6") (pinfunction "A_6") (pintype "bidirectional"))
      (node (ref "L8") (pin "1") (pinfunction "1_1") (pintype "passive"))
      (node (ref "R32") (pin "2") (pinfunction "2_2") (pintype "passive"))
      (node (ref "R34") (pin "2") (pinfunction "2_2") (pintype "passive"))
    )
    (net (code "9") (name "/A0") (class "Default")
      (node (ref "IC2") (pin "20") (pinfunction "A5_20") (pintype "input"))
      (node (ref "IC3") (pin "12") (pinfunction "Q7_12") (pintype "tri_state"))
    )
    (net (code "10") (name "/A1") (class "Default")
      (node (ref "IC2") (pin "21") (pinfunction "A4_21") (pintype "input"))
      (node (ref "IC3") (pin "13") (pinfunction "Q6_13") (pintype "tri_state"))
    )
    (net (code "11") (name "/A2") (class "Default")
      (node (ref "IC2") (pin "22") (pinfunction "A3_22") (pintype "input"))
      (node (ref "IC3") (pin "14") (pinfunction "Q5_14") (pintype "tri_state"))
    )
    (net (code "12") (name "/A3") (class "Default")
      (node (ref "IC2") (pin "23") (pinfunction "A2_23") (pintype "input"))
      (node (ref "IC3") (pin "15") (pinfunction "Q4_15") (pintype "tri_state"))
    )
    (net (code "13") (name "/A4") (class "Default")
      (node (ref "IC2") (pin "24") (pinfunction "A1_24") (pintype "input"))
      (node (ref "IC3") (pin "16") (pinfunction "Q3_16") (pintype "tri_state"))
    )
    (net (code "14") (name "/A5") (class "Default")
      (node (ref "IC2") (pin "25") (pinfunction "A0_25") (pintype "input"))
      (node (ref "IC3") (pin "17") (pinfunction "Q2_17") (pintype "tri_state"))
    )
    (net (code "15") (name "/A6") (class "Default")
      (node (ref "IC2") (pin "45") (pinfunction "A-1/D15_45") (pintype "tri_state"))
      (node (ref "IC3") (pin "18") (pinfunction "Q1_18") (pintype "tri_state"))
    )
    (net (code "16") (name "/A7") (class "Default")
      (node (ref "IC2") (pin "48") (pinfunction "A16_48") (pintype "input"))
      (node (ref "IC3") (pin "19") (pinfunction "Q0_19") (pintype "tri_state"))
    )
    (net (code "17") (name "/A8") (class "Default")
      (node (ref "IC2") (pin "19") (pinfunction "A6_19") (pintype "input"))
      (node (ref "IC4") (pin "19") (pinfunction "Q0_19") (pintype "tri_state"))
    )
    (net (code "18") (name "/A9") (class "Default")
      (node (ref "IC2") (pin "18") (pinfunction "A7_18") (pintype "input"))
      (node (ref "IC4") (pin "18") (pinfunction "Q1_18") (pintype "tri_state"))
    )
    (net (code "19") (name "/A10") (class "Default")
      (node (ref "IC2") (pin "17") (pinfunction "A17_17") (pintype "input"))
      (node (ref "IC4") (pin "17") (pinfunction "Q2_17") (pintype "tri_state"))
    )
    (net (code "20") (name "/A11") (class "Default")
      (node (ref "IC2") (pin "16") (pinfunction "A18_16") (pintype "input"))
      (node (ref "IC4") (pin "16") (pinfunction "Q3_16") (pintype "tri_state"))
    )
    (net (code "21") (name "/A12") (class "Default")
      (node (ref "IC2") (pin "9") (pinfunction "A19_9") (pintype "input"))
      (node (ref "IC4") (pin "15") (pinfunction "Q4_15") (pintype "tri_state"))
    )
    (net (code "22") (name "/A13") (class "Default")
      (node (ref "IC2") (pin "8") (pinfunction "A8_8") (pintype "input"))
      (node (ref "IC4") (pin "14") (pinfunction "Q5_14") (pintype "tri_state"))
    )
    (net (code "23") (name "/A14") (class "Default")
      (node (ref "IC2") (pin "7") (pinfunction "A9_7") (pintype "input"))
      (node (ref "IC4") (pin "13") (pinfunction "Q6_13") (pintype "tri_state"))
    )
    (net (code "24") (name "/A15") (class "Default")
      (node (ref "IC2") (pin "6") (pinfunction "A10_6") (pintype "input"))
      (node (ref "IC4") (pin "12") (pinfunction "Q7_12") (pintype "tri_state"))
    )
    (net (code "25") (name "/A16") (class "Default")
      (node (ref "IC1") (pin "32") (pinfunction "AN8/RPB8/CTED10/RB8_32") (pintype "bidirectional"))
      (node (ref "IC2") (pin "5") (pinfunction "A11_5") (pintype "input"))
    )
    (net (code "26") (name "/A17") (class "Default")
      (node (ref "IC1") (pin "33") (pinfunction "AN9/RPB9/CTED4/RB9_33") (pintype "bidirectional"))
      (node (ref "IC2") (pin "4") (pinfunction "A12_4") (pintype "input"))
    )
    (net (code "27") (name "/A18") (class "Default")
      (node (ref "IC1") (pin "34") (pinfunction "CVREFOUT/AN10/RPB10/PMA13/CTED11/RB10_34") (pintype "bidirectional"))
      (node (ref "IC2") (pin "3") (pinfunction "A13_3") (pintype "input"))
    )
    (net (code "28") (name "/A19") (class "Default")
      (node (ref "IC1") (pin "35") (pinfunction "AN11/PMA12/RB11_35") (pintype "bidirectional"))
      (node (ref "IC2") (pin "2") (pinfunction "A14_2") (pintype "input"))
    )
    (net (code "29") (name "/A20") (class "Default")
      (node (ref "IC1") (pin "41") (pinfunction "AN12/PMA11/RB12_41") (pintype "bidirectional"))
      (node (ref "IC2") (pin "1") (pinfunction "A15_1") (pintype "input"))
    )
    (net (code "30") (name "/AGND1") (class "Default")
      (node (ref "C3") (pin "1") (pinfunction "1_1") (pintype "passive"))
      (node (ref "C9") (pin "-") (pinfunction "-_-") (pintype "passive"))
      (node (ref "J1") (pin "2") (pinfunction "2_2") (pintype "passive"))
      (node (ref "R6") (pin "1") (pinfunction "1_1") (pintype "passive"))
    )
    (net (code "31") (name "/AGND2") (class "Default")
      (node (ref "C10") (pin "-") (pinfunction "-_-") (pintype "passive"))
      (node (ref "C4") (pin "1") (pinfunction "1_1") (pintype "passive"))
      (node (ref "J2") (pin "2") (pinfunction "2_2") (pintype "passive"))
      (node (ref "R7") (pin "1") (pinfunction "1_1") (pintype "passive"))
    )
    (net (code "32") (name "/AVDD1") (class "Default")
      (node (ref "C3") (pin "2") (pinfunction "2_2") (pintype "passive"))
      (node (ref "C9") (pin "+") (pinfunction "+_+") (pintype "passive"))
      (node (ref "J1") (pin "4") (pinfunction "4_4") (pintype "passive"))
      (node (ref "L1") (pin "2") (pinfunction "2_2") (pintype "passive"))
    )
    (net (code "33") (name "/AVDD2") (class "Default")
      (node (ref "C10") (pin "+") (pinfunction "+_+") (pintype "passive"))
      (node (ref "C4") (pin "2") (pinfunction "2_2") (pintype "passive"))
      (node (ref "J2") (pin "4") (pinfunction "4_4") (pintype "passive"))
      (node (ref "L2") (pin "1") (pinfunction "1_1") (pintype "passive"))
    )
    (net (code "34") (name "/B-") (class "Default")
      (node (ref "IC14") (pin "2") (pinfunction "2_2") (pintype "passive"))
      (node (ref "J3") (pin "5") (pinfunction "5_5") (pintype "passive"))
      (node (ref "J4") (pin "5") (pinfunction "5_5") (pintype "passive"))
      (node (ref "L7") (pin "2") (pinfunction "2_2") (pintype "passive"))
    )
    (net (code "35") (name "/B--") (class "Default")
      (node (ref "IC12") (pin "7") (pinfunction "B_7") (pintype "bidirectional"))
      (node (ref "L7") (pin "1") (pinfunction "1_1") (pintype "passive"))
      (node (ref "R31") (pin "1") (pinfunction "1_1") (pintype "passive"))
      (node (ref "R32") (pin "1") (pinfunction "1_1") (pintype "passive"))
    )
    (net (code "36") (name "/BT-RTS") (class "Default")
      (node (ref "IC1") (pin "83") (pinfunction "PMD14/RD6_83") (pintype "bidirectional"))
      (node (ref "J14") (pin "7") (pinfunction "7_7") (pintype "passive"))
      (node (ref "O32") (pin "P$1") (pinfunction "TP_P$1") (pintype "passive"))
      (node (ref "T44") (pin "P$1") (pinfunction "TP_P$1") (pintype "passive"))
    )
    (net (code "37") (name "/BT-RX") (class "Default")
      (node (ref "IC1") (pin "73") (pinfunction "SOSCI/RPC13/RC13_73") (pintype "bidirectional"))
      (node (ref "J14") (pin "3") (pinfunction "3_3") (pintype "passive"))
      (node (ref "O37") (pin "P$1") (pinfunction "TP_P$1") (pintype "passive"))
      (node (ref "T40") (pin "P$1") (pinfunction "TP_P$1") (pintype "passive"))
    )
    (net (code "38") (name "/BT-TX") (class "Default")
      (node (ref "IC1") (pin "74") (pinfunction "SOSCO/RPC14/T1CK/RC14_74") (pintype "bidirectional"))
      (node (ref "J14") (pin "4") (pinfunction "4_4") (pintype "passive"))
      (node (ref "O36") (pin "P$1") (pinfunction "TP_P$1") (pintype "passive"))
      (node (ref "T41") (pin "P$1") (pinfunction "TP_P$1") (pintype "passive"))
    )
    (net (code "39") (name "/CON-LED") (class "Default")
      (node (ref "IC1") (pin "78") (pinfunction "AN26/RPD3/RD3_78") (pintype "bidirectional"))
      (node (ref "J14") (pin "6") (pinfunction "6_6") (pintype "passive"))
      (node (ref "O33") (pin "P$1") (pinfunction "TP_P$1") (pintype "passive"))
      (node (ref "T43") (pin "P$1") (pinfunction "TP_P$1") (pintype "passive"))
    )
    (net (code "40") (name "/CS-SRAM") (class "Default")
      (node (ref "IC1") (pin "38") (pinfunction "TCK/CTED2/RA1_38") (pintype "bidirectional"))
      (node (ref "IC2") (pin "12") (pinfunction "CS2_12") (pintype "input"))
      (node (ref "O17") (pin "P$1") (pinfunction "TP_P$1") (pintype "passive"))
      (node (ref "R5") (pin "2") (pinfunction "2_2") (pintype "passive"))
      (node (ref "T28") (pin "P$1") (pinfunction "TP_P$1") (pintype "passive"))
    )
    (net (code "41") (name "/CURR-SENSE") (class "Default")
      (node (ref "C66") (pin "1") (pinfunction "1_1") (pintype "passive"))
      (node (ref "IC1") (pin "14") (pinfunction "AN19/C2INC/RPG9/PMA2/RG9_14") (pintype "bidirectional"))
      (node (ref "O8") (pin "P$1") (pinfunction "TP_P$1") (pintype "passive"))
      (node (ref "R102") (pin "2") (pinfunction "2_2") (pintype "passive"))
      (node (ref "T39") (pin "P$1") (pinfunction "TP_P$1") (pintype "passive"))
    )
    (net (code "42") (name "/D+") (class "Default")
      (node (ref "IC1") (pin "57") (pinfunction "D+/RG2_57") (pintype "bidirectional"))
      (node (ref "IC15") (pin "3") (pinfunction "3_3") (pintype "passive"))
      (node (ref "J12") (pin "3_D+") (pinfunction "D+_3_D+") (pintype "bidirectional"))
    )
    (net (code "43") (name "/D-") (class "Default")
      (node (ref "IC1") (pin "56") (pinfunction "D-/RG3_56") (pintype "bidirectional"))
      (node (ref "IC15") (pin "2") (pinfunction "2_2") (pintype "passive"))
      (node (ref "J12") (pin "2_D-") (pinfunction "D-_2_D-") (pintype "bidirectional"))
    )
    (net (code "44") (name "/D0") (class "Default")
      (node (ref "IC1") (pin "93") (pinfunction "PMD0/RE0_93") (pintype "bidirectional"))
      (node (ref "IC2") (pin "29") (pinfunction "D0_29") (pintype "tri_state"))
      (node (ref "IC3") (pin "9") (pinfunction "D7_9") (pintype "input"))
      (node (ref "IC4") (pin "2") (pinfunction "D0_2") (pintype "input"))
    )
    (net (code "45") (name "/D1") (class "Default")
      (node (ref "IC1") (pin "94") (pinfunction "PMD1/RE1_94") (pintype "bidirectional"))
      (node (ref "IC2") (pin "31") (pinfunction "D1_31") (pintype "tri_state"))
      (node (ref "IC3") (pin "8") (pinfunction "D6_8") (pintype "input"))
      (node (ref "IC4") (pin "3") (pinfunction "D1_3") (pintype "input"))
    )
    (net (code "46") (name "/D2") (class "Default")
      (node (ref "IC1") (pin "98") (pinfunction "AN20/PMD2/RE2_98") (pintype "bidirectional"))
      (node (ref "IC2") (pin "33") (pinfunction "D2_33") (pintype "tri_state"))
      (node (ref "IC3") (pin "7") (pinfunction "D5_7") (pintype "input"))
      (node (ref "IC4") (pin "4") (pinfunction "D2_4") (pintype "input"))
    )
    (net (code "47") (name "/D3") (class "Default")
      (node (ref "IC1") (pin "99") (pinfunction "RPE3/PMD3/RE3_99") (pintype "bidirectional"))
      (node (ref "IC2") (pin "35") (pinfunction "D3_35") (pintype "tri_state"))
      (node (ref "IC3") (pin "6") (pinfunction "D4_6") (pintype "input"))
      (node (ref "IC4") (pin "5") (pinfunction "D3_5") (pintype "input"))
    )
    (net (code "48") (name "/D4") (class "Default")
      (node (ref "IC1") (pin "100") (pinfunction "AN21/PMD4/RE4_100") (pintype "bidirectional"))
      (node (ref "IC2") (pin "38") (pinfunction "D4_38") (pintype "tri_state"))
      (node (ref "IC3") (pin "5") (pinfunction "D3_5") (pintype "input"))
      (node (ref "IC4") (pin "6") (pinfunction "D4_6") (pintype "input"))
    )
    (net (code "49") (name "/D5") (class "Default")
      (node (ref "IC1") (pin "3") (pinfunction "AN22/RPE5/PMD5/RE5_3") (pintype "bidirectional"))
      (node (ref "IC2") (pin "40") (pinfunction "D5_40") (pintype "tri_state"))
      (node (ref "IC3") (pin "4") (pinfunction "D2_4") (pintype "input"))
      (node (ref "IC4") (pin "7") (pinfunction "D5_7") (pintype "input"))
    )
    (net (code "50") (name "/D6") (class "Default")
      (node (ref "IC1") (pin "4") (pinfunction "AN23/PMD6/RE6_4") (pintype "bidirectional"))
      (node (ref "IC2") (pin "42") (pinfunction "D6_42") (pintype "tri_state"))
      (node (ref "IC3") (pin "3") (pinfunction "D1_3") (pintype "input"))
      (node (ref "IC4") (pin "8") (pinfunction "D6_8") (pintype "input"))
    )
    (net (code "51") (name "/D7") (class "Default")
      (node (ref "IC1") (pin "5") (pinfunction "AN27/PMD7/RE7_5") (pintype "bidirectional"))
      (node (ref "IC2") (pin "44") (pinfunction "D7_44") (pintype "tri_state"))
      (node (ref "IC3") (pin "2") (pinfunction "D0_2") (pintype "input"))
      (node (ref "IC4") (pin "9") (pinfunction "D7_9") (pintype "input"))
    )
    (net (code "52") (name "/DOOR-IN-EN") (class "Default")
      (node (ref "IC1") (pin "51") (pinfunction "RPF3/USBID/RF3_51") (pintype "bidirectional"))
      (node (ref "O43") (pin "P$1") (pinfunction "TP_P$1") (pintype "passive"))
      (node (ref "Q12") (pin "2") (pinfunction "G_2") (pintype "passive"))
      (node (ref "Q13") (pin "2") (pinfunction "G_2") (pintype "passive"))
      (node (ref "R76") (pin "1") (pinfunction "1_1") (pintype "passive"))
      (node (ref "R88") (pin "1") (pinfunction "1_1") (pintype "passive"))
      (node (ref "T8") (pin "P$1") (pinfunction "TP_P$1") (pintype "passive"))
    )
    (net (code "53") (name "/DOOR1IN") (class "Default")
      (node (ref "IC1") (pin "50") (pinfunction "RPF5/PMA8/RF5_50") (pintype "bidirectional"))
      (node (ref "O21") (pin "P$1") (pinfunction "TP_P$1") (pintype "passive"))
      (node (ref "Q13") (pin "3") (pinfunction "D_3") (pintype "passive"))
      (node (ref "R74") (pin "1") (pinfunction "1_1") (pintype "passive"))
      (node (ref "T12") (pin "P$1") (pinfunction "TP_P$1") (pintype "passive"))
    )
    (net (code "54") (name "/DOOR2IN") (class "Default")
      (node (ref "IC1") (pin "77") (pinfunction "AN25/RPD2/RD2_77") (pintype "bidirectional"))
      (node (ref "O34") (pin "P$1") (pinfunction "TP_P$1") (pintype "passive"))
      (node (ref "Q12") (pin "3") (pinfunction "D_3") (pintype "passive"))
      (node (ref "R89") (pin "1") (pinfunction "1_1") (pintype "passive"))
      (node (ref "T11") (pin "P$1") (pinfunction "TP_P$1") (pintype "passive"))
    )
    (net (code "55") (name "/DOVDD1") (class "Default")
      (node (ref "C11") (pin "+") (pinfunction "+_+") (pintype "passive"))
      (node (ref "C5") (pin "1") (pinfunction "1_1") (pintype "passive"))
      (node (ref "J1") (pin "11") (pinfunction "11_11") (pintype "passive"))
      (node (ref "L3") (pin "2") (pinfunction "2_2") (pintype "passive"))
    )
    (net (code "56") (name "/DOVDD2") (class "Default")
      (node (ref "C12") (pin "+") (pinfunction "+_+") (pintype "passive"))
      (node (ref "C6") (pin "1") (pinfunction "1_1") (pintype "passive"))
      (node (ref "J2") (pin "11") (pinfunction "11_11") (pintype "passive"))
      (node (ref "L4") (pin "1") (pinfunction "1_1") (pintype "passive"))
    )
    (net (code "57") (name "/DVDD1") (class "Default")
      (node (ref "C13") (pin "+") (pinfunction "+_+") (pintype "passive"))
      (node (ref "C7") (pin "2") (pinfunction "2_2") (pintype "passive"))
      (node (ref "J1") (pin "10") (pinfunction "10_10") (pintype "passive"))
      (node (ref "L5") (pin "2") (pinfunction "2_2") (pintype "passive"))
    )
    (net (code "58") (name "/DVDD2") (class "Default")
      (node (ref "C14") (pin "+") (pinfunction "+_+") (pintype "passive"))
      (node (ref "C8") (pin "2") (pinfunction "2_2") (pintype "passive"))
      (node (ref "J2") (pin "10") (pinfunction "10_10") (pintype "passive"))
      (node (ref "L6") (pin "1") (pinfunction "1_1") (pintype "passive"))
    )
    (net (code "59") (name "/EN") (class "Default")
      (node (ref "IC1") (pin "18") (pinfunction "RPE8/RE8_18") (pintype "bidirectional"))
      (node (ref "J15") (pin "8") (pinfunction "8_8") (pintype "passive"))
      (node (ref "O10") (pin "P$1") (pinfunction "TP_P$1") (pintype "passive"))
      (node (ref "T25") (pin "P$1") (pinfunction "TP_P$1") (pintype "passive"))
    )
    (net (code "60") (name "/HREF") (class "Default")
      (node (ref "IC1") (pin "6") (pinfunction "RPC1/RC1_6") (pintype "bidirectional"))
      (node (ref "J1") (pin "9") (pinfunction "9_9") (pintype "passive"))
      (node (ref "J2") (pin "9") (pinfunction "9_9") (pintype "passive"))
      (node (ref "O2") (pin "P$1") (pinfunction "TP_P$1") (pintype "passive"))
      (node (ref "T18") (pin "P$1") (pinfunction "TP_P$1") (pintype "passive"))
    )
    (net (code "61") (name "/INFRA1PWM") (class "Default")
      (node (ref "IC1") (pin "90") (pinfunction "RPG0/PMD8/RG0_90") (pintype "bidirectional"))
      (node (ref "O27") (pin "P$1") (pinfunction "TP_P$1") (pintype "passive"))
      (node (ref "R113") (pin "2") (pinfunction "2_2") (pintype "passive"))
      (node (ref "T34") (pin "P$1") (pinfunction "TP_P$1") (pintype "passive"))
    )
    (net (code "62") (name "/INFRA2PWM") (class "Default")
      (node (ref "IC1") (pin "40") (pinfunction "RPF12/RF12_40") (pintype "bidirectional"))
      (node (ref "O19") (pin "P$1") (pinfunction "TP_P$1") (pintype "passive"))
      (node (ref "R119") (pin "2") (pinfunction "2_2") (pintype "passive"))
      (node (ref "T35") (pin "P$1") (pinfunction "TP_P$1") (pintype "passive"))
    )
    (net (code "63") (name "/IRQ") (class "Default")
      (node (ref "IC1") (pin "19") (pinfunction "RPE9/RE9_19") (pintype "bidirectional"))
      (node (ref "J15") (pin "3") (pinfunction "3_3") (pintype "passive"))
      (node (ref "O11") (pin "P$1") (pinfunction "TP_P$1") (pintype "passive"))
      (node (ref "T24") (pin "P$1") (pinfunction "TP_P$1") (pintype "passive"))
    )
    (net (code "64") (name "/L1CTL") (class "Default")
      (node (ref "C79") (pin "1") (pinfunction "1_1") (pintype "passive"))
      (node (ref "J5") (pin "3") (pinfunction "3_3") (pintype "bidirectional"))
      (node (ref "Q6") (pin "4") (pinfunction "D_4") (pintype "passive"))
    )
    (net (code "65") (name "/L1PWR") (class "Default")
      (node (ref "C80") (pin "1") (pinfunction "1_1") (pintype "passive"))
      (node (ref "J5") (pin "2") (pinfunction "2_2") (pintype "bidirectional"))
      (node (ref "Q6") (pin "6") (pinfunction "D_6") (pintype "passive"))
    )
    (net (code "66") (name "/L2CTL") (class "Default")
      (node (ref "C78") (pin "1") (pinfunction "1_1") (pintype "passive"))
      (node (ref "J6") (pin "3") (pinfunction "3_3") (pintype "bidirectional"))
      (node (ref "Q8") (pin "6") (pinfunction "D_6") (pintype "passive"))
    )
    (net (code "67") (name "/L2PWR") (class "Default")
      (node (ref "C77") (pin "1") (pinfunction "1_1") (pintype "passive"))
      (node (ref "J6") (pin "2") (pinfunction "2_2") (pintype "bidirectional"))
      (node (ref "Q8") (pin "4") (pinfunction "D_4") (pintype "passive"))
    )
    (net (code "68") (name "/LAN-CTL") (class "Default")
      (node (ref "IC1") (pin "84") (pinfunction "PMD15/RD7_84") (pintype "bidirectional"))
      (node (ref "IC12") (pin "2") (pinfunction "/RE_2") (pintype "input"))
      (node (ref "IC12") (pin "3") (pinfunction "DE_3") (pintype "input"))
      (node (ref "O31") (pin "P$1") (pinfunction "TP_P$1") (pintype "passive"))
      (node (ref "R71") (pin "1") (pinfunction "1_1") (pintype "passive"))
      (node (ref "T15") (pin "P$1") (pinfunction "TP_P$1") (pintype "passive"))
    )
    (net (code "69") (name "/LAN-RX") (class "Default")
      (node (ref "IC1") (pin "88") (pinfunction "RPF1/PMD10/RF1_88") (pintype "bidirectional"))
      (node (ref "IC12") (pin "1") (pinfunction "R_1") (pintype "output"))
      (node (ref "O29") (pin "P$1") (pinfunction "TP_P$1") (pintype "passive"))
      (node (ref "R72") (pin "2") (pinfunction "2_2") (pintype "passive"))
      (node (ref "T13") (pin "P$1") (pinfunction "TP_P$1") (pintype "passive"))
    )
    (net (code "70") (name "/LAN-TX") (class "Default")
      (node (ref "IC1") (pin "87") (pinfunction "RPF0/PMD11/RF0_87") (pintype "bidirectional"))
      (node (ref "IC12") (pin "4") (pinfunction "D_4") (pintype "input"))
      (node (ref "O30") (pin "P$1") (pinfunction "TP_P$1") (pintype "passive"))
      (node (ref "R73") (pin "1") (pinfunction "1_1") (pintype "passive"))
      (node (ref "T14") (pin "P$1") (pinfunction "TP_P$1") (pintype "passive"))
    )
    (net (code "71") (name "/LED-PIC") (class "Default")
      (node (ref "IC1") (pin "1") (pinfunction "RG15_1") (pintype "bidirectional"))
      (node (ref "O1") (pin "P$1") (pinfunction "TP_P$1") (pintype "passive"))
      (node (ref "R29") (pin "1") (pinfunction "1_1") (pintype "passive"))
      (node (ref "T36") (pin "P$1") (pinfunction "TP_P$1") (pintype "passive"))
      (node (ref "TP4") (pin "P$1") (pinfunction "TP_P$1") (pintype "passive"))
    )
    (net (code "72") (name "/LEH-SRAM") (class "Default")
      (node (ref "IC1") (pin "43") (pinfunction "AN14/RPB14/PMA1/CTED5/RB14_43") (pintype "bidirectional"))
      (node (ref "IC4") (pin "11") (pinfunction "LE_11") (pintype "input"))
      (node (ref "R2") (pin "2") (pinfunction "2_2") (pintype "passive"))
    )
    (net (code "73") (name "/LEL-SRAM") (class "Default")
      (node (ref "IC1") (pin "44") (pinfunction "AN15/RPB15/PMA0/CTED6//RB15_44") (pintype "bidirectional"))
      (node (ref "IC3") (pin "11") (pinfunction "LE_11") (pintype "input"))
      (node (ref "R1") (pin "2") (pinfunction "2_2") (pintype "passive"))
    )
    (net (code "74") (name "/LOCK-IN-EN") (class "Default")
      (node (ref "IC1") (pin "60") (pinfunction "TDI/CTED9/RA4_60") (pintype "bidirectional"))
      (node (ref "O40") (pin "P$1") (pinfunction "TP_P$1") (pintype "passive"))
      (node (ref "Q10") (pin "2") (pinfunction "G_2") (pintype "passive"))
      (node (ref "Q11") (pin "2") (pinfunction "G_2") (pintype "passive"))
      (node (ref "R67") (pin "1") (pinfunction "1_1") (pintype "passive"))
      (node (ref "R83") (pin "1") (pinfunction "1_1") (pintype "passive"))
      (node (ref "T6") (pin "P$1") (pinfunction "TP_P$1") (pintype "passive"))
    )
    (net (code "75") (name "/LOCK1CTL") (class "Default")
      (node (ref "IC1") (pin "61") (pinfunction "TDO/RA5_61") (pintype "bidirectional"))
      (node (ref "O39") (pin "P$1") (pinfunction "TP_P$1") (pintype "passive"))
      (node (ref "Q7") (pin "5") (pinfunction "G_5") (pintype "passive"))
      (node (ref "R54") (pin "1") (pinfunction "1_1") (pintype "passive"))
      (node (ref "T1") (pin "P$1") (pinfunction "TP_P$1") (pintype "passive"))
    )
    (net (code "76") (name "/LOCK1IN") (class "Default")
      (node (ref "IC1") (pin "49") (pinfunction "RPF4/PMA9/RF4_49") (pintype "bidirectional"))
      (node (ref "O20") (pin "P$1") (pinfunction "TP_P$1") (pintype "passive"))
      (node (ref "Q11") (pin "3") (pinfunction "D_3") (pintype "passive"))
      (node (ref "R66") (pin "1") (pinfunction "1_1") (pintype "passive"))
      (node (ref "T10") (pin "P$1") (pinfunction "TP_P$1") (pintype "passive"))
    )
    (net (code "77") (name "/LOCK2CTL") (class "Default")
      (node (ref "IC1") (pin "91") (pinfunction "TRCLK/RA6_91") (pintype "bidirectional"))
      (node (ref "O26") (pin "P$1") (pinfunction "TP_P$1") (pintype "passive"))
      (node (ref "Q9") (pin "2") (pinfunction "G_2") (pintype "passive"))
      (node (ref "R58") (pin "1") (pinfunction "1_1") (pintype "passive"))
      (node (ref "T2") (pin "P$1") (pinfunction "TP_P$1") (pintype "passive"))
    )
    (net (code "78") (name "/LOCK2IN") (class "Default")
      (node (ref "IC1") (pin "89") (pinfunction "RPG1/PMD9/RG1_89") (pintype "bidirectional"))
      (node (ref "O28") (pin "P$1") (pinfunction "TP_P$1") (pintype "passive"))
      (node (ref "Q10") (pin "3") (pinfunction "D_3") (pintype "passive"))
      (node (ref "R81") (pin "1") (pinfunction "1_1") (pintype "passive"))
      (node (ref "T9") (pin "P$1") (pinfunction "TP_P$1") (pintype "passive"))
    )
    (net (code "79") (name "/LOCK12PWR") (class "Default")
      (node (ref "IC1") (pin "92") (pinfunction "TRD3/CTED8/RA7_92") (pintype "bidirectional"))
      (node (ref "O25") (pin "P$1") (pinfunction "TP_P$1") (pintype "passive"))
      (node (ref "Q7") (pin "2") (pinfunction "G_2") (pintype "passive"))
      (node (ref "Q9") (pin "5") (pinfunction "G_5") (pintype "passive"))
      (node (ref "R52") (pin "1") (pinfunction "1_1") (pintype "passive"))
      (node (ref "R60") (pin "1") (pinfunction "1_1") (pintype "passive"))
      (node (ref "T4") (pin "P$1") (pinfunction "TP_P$1") (pintype "passive"))
    )
    (net (code "80") (name "/NC-A15-2") (class "Default")
      (node (ref "IC1") (pin "42") (pinfunction "AN13/RB13_42") (pintype "bidirectional"))
    )
    (net (code "81") (name "/OE-SRAM") (class "Default")
      (node (ref "IC1") (pin "82") (pinfunction "RPD5/PMRD/RD5_82") (pintype "bidirectional"))
      (node (ref "IC2") (pin "28") (pinfunction "~{OE}_28") (pintype "input"))
      (node (ref "R3") (pin "1") (pinfunction "1_1") (pintype "passive"))
    )
    (net (code "82") (name "/PCLK") (class "Default")
      (node (ref "IC1") (pin "76") (pinfunction "AN24/RPD1/RD1_76") (pintype "bidirectional"))
      (node (ref "J1") (pin "17") (pinfunction "17_17") (pintype "passive"))
      (node (ref "J2") (pin "17") (pinfunction "17_17") (pintype "passive"))
      (node (ref "O35") (pin "P$1") (pinfunction "TP_P$1") (pintype "passive"))
      (node (ref "T17") (pin "P$1") (pinfunction "TP_P$1") (pintype "passive"))
    )
    (net (code "83") (name "/PGC") (class "Default")
      (node (ref "IC1") (pin "24") (pinfunction "PGEC1/AN1/RPB1/CTED12/RB1_24") (pintype "bidirectional"))
      (node (ref "J17") (pin "5") (pinfunction "5_5") (pintype "passive"))
      (node (ref "R131") (pin "1") (pinfunction "1_1") (pintype "passive"))
    )
    (net (code "84") (name "/PGD") (class "Default")
      (node (ref "IC1") (pin "25") (pinfunction "PGED1/AN0/RPB0/RB0_25") (pintype "bidirectional"))
      (node (ref "J17") (pin "4") (pinfunction "4_4") (pintype "passive"))
      (node (ref "R130") (pin "2") (pinfunction "2_2") (pintype "passive"))
    )
    (net (code "85") (name "/POWER-GOOD") (class "Default")
      (node (ref "IC6") (pin "4") (pinfunction "OUT_4") (pintype "output"))
      (node (ref "R130") (pin "1") (pinfunction "1_1") (pintype "passive"))
      (node (ref "T45") (pin "P$1") (pinfunction "TP_P$1") (pintype "passive"))
      (node (ref "TP2") (pin "P$1") (pinfunction "TP_P$1") (pintype "passive"))
    )
    (net (code "86") (name "/PWDN-CAM1") (class "Default")
      (node (ref "IC1") (pin "97") (pinfunction "TRD0/RG13_97") (pintype "bidirectional"))
      (node (ref "J1") (pin "8") (pinfunction "8_8") (pintype "passive"))
      (node (ref "O22") (pin "P$1") (pinfunction "TP_P$1") (pintype "passive"))
      (node (ref "R12") (pin "1") (pinfunction "1_1") (pintype "passive"))
      (node (ref "T20") (pin "P$1") (pinfunction "TP_P$1") (pintype "passive"))
    )
    (net (code "87") (name "/PWDN-CAM2") (class "Default")
      (node (ref "IC1") (pin "39") (pinfunction "RPF13/RF13_39") (pintype "bidirectional"))
      (node (ref "J2") (pin "8") (pinfunction "8_8") (pintype "passive"))
      (node (ref "O18") (pin "P$1") (pinfunction "TP_P$1") (pintype "passive"))
      (node (ref "R16") (pin "1") (pinfunction "1_1") (pintype "passive"))
      (node (ref "T21") (pin "P$1") (pinfunction "TP_P$1") (pintype "passive"))
    )
    (net (code "88") (name "/REF-EN") (class "Default")
      (node (ref "IC1") (pin "28") (pinfunction "VREF-/CVREF-/PMA7/RA9_28") (pintype "bidirectional"))
      (node (ref "R93") (pin "1") (pinfunction "1_1") (pintype "passive"))
    )
    (net (code "89") (name "/REF2,5V") (class "Default")
      (node (ref "C57") (pin "1") (pinfunction "1_1") (pintype "passive"))
      (node (ref "IC1") (pin "29") (pinfunction "VREF+/CVREF+/PMA6/RA10_29") (pintype "bidirectional"))
      (node (ref "IC13") (pin "2") (pinfunction "VOUT_2") (pintype "bidirectional"))
    )
    (net (code "90") (name "/RESET-CAM1") (class "Default")
      (node (ref "C76") (pin "1") (pinfunction "1_1") (pintype "passive"))
      (node (ref "J1") (pin "6") (pinfunction "6_6") (pintype "passive"))
      (node (ref "R11") (pin "1") (pinfunction "1_1") (pintype "passive"))
    )
    (net (code "91") (name "/RESET-CAM2") (class "Default")
      (node (ref "C75") (pin "1") (pinfunction "1_1") (pintype "passive"))
      (node (ref "J2") (pin "6") (pinfunction "6_6") (pintype "passive"))
      (node (ref "R15") (pin "1") (pinfunction "1_1") (pintype "passive"))
    )
    (net (code "92") (name "/SCL1-EEPROM") (class "Default")
      (node (ref "IC1") (pin "66") (pinfunction "SCL1/RPA14/RA14_66") (pintype "bidirectional"))
      (node (ref "IC11") (pin "6") (pinfunction "SCL_6") (pintype "input"))
      (node (ref "IC7") (pin "6") (pinfunction "SCL_6") (pintype "input"))
      (node (ref "R26") (pin "2") (pinfunction "2_2") (pintype "passive"))
    )
    (net (code "93") (name "/SCLK2-SPI") (class "Default")
      (node (ref "IC1") (pin "10") (pinfunction "AN16/C1IND/RPG6/SCK2/PMA5/RG6_10") (pintype "bidirectional"))
      (node (ref "IC9") (pin "6") (pinfunction "C_6") (pintype "input"))
      (node (ref "J11") (pin "5") (pinfunction "CLK_5") (pintype "passive"))
      (node (ref "J15") (pin "12") (pinfunction "12_12") (pintype "passive"))
    )
    (net (code "94") (name "/SD-CS") (class "Default")
      (node (ref "IC1") (pin "9") (pinfunction "RPC4/CTED7/RC4_9") (pintype "bidirectional"))
      (node (ref "J11") (pin "2") (pinfunction "CS/DAT3_2") (pintype "passive"))
      (node (ref "O5") (pin "P$1") (pinfunction "TP_P$1") (pintype "passive"))
      (node (ref "R127") (pin "2") (pinfunction "2_2") (pintype "passive"))
      (node (ref "T29") (pin "P$1") (pinfunction "TP_P$1") (pintype "passive"))
    )
    (net (code "95") (name "/SDA1-EEPROM") (class "Default")
      (node (ref "IC1") (pin "67") (pinfunction "SDA1/RPA15/RA15_67") (pintype "bidirectional"))
      (node (ref "IC11") (pin "5") (pinfunction "SDA_5") (pintype "bidirectional"))
      (node (ref "IC7") (pin "5") (pinfunction "SDA_5") (pintype "bidirectional"))
      (node (ref "R27") (pin "2") (pinfunction "2_2") (pintype "passive"))
    )
    (net (code "96") (name "/SDI2-MISO") (class "Default")
      (node (ref "IC1") (pin "22") (pinfunction "PGED3/AN3/C2INA/RPB3/RB3_22") (pintype "bidirectional"))
      (node (ref "IC9") (pin "2") (pinfunction "Q_2") (pintype "bidirectional"))
      (node (ref "J11") (pin "7") (pinfunction "DO/DAT0_7") (pintype "passive"))
      (node (ref "J15") (pin "11") (pinfunction "11_11") (pintype "passive"))
      (node (ref "O13") (pin "P$1") (pinfunction "TP_P$1") (pintype "passive"))
      (node (ref "T22") (pin "P$1") (pinfunction "TP_P$1") (pintype "passive"))
    )
    (net (code "97") (name "/SDO2-MOSI") (class "Default")
      (node (ref "IC1") (pin "20") (pinfunction "AN5/C1INA/RPB5/RB5_20") (pintype "bidirectional"))
      (node (ref "IC9") (pin "5") (pinfunction "D_5") (pintype "input"))
      (node (ref "J11") (pin "3") (pinfunction "DI/CMD_3") (pintype "passive"))
      (node (ref "J15") (pin "14") (pinfunction "14_14") (pintype "passive"))
      (node (ref "O12") (pin "P$1") (pinfunction "TP_P$1") (pintype "passive"))
      (node (ref "T23") (pin "P$1") (pinfunction "TP_P$1") (pintype "passive"))
    )
    (net (code "98") (name "/SIO-C-CAM") (class "Default")
      (node (ref "IC1") (pin "58") (pinfunction "SCL2/RA2_58") (pintype "bidirectional"))
      (node (ref "J1") (pin "5") (pinfunction "5_5") (pintype "passive"))
      (node (ref "J2") (pin "5") (pinfunction "5_5") (pintype "passive"))
      (node (ref "R13") (pin "1") (pinfunction "1_1") (pintype "passive"))
    )
    (net (code "99") (name "/SIO-D-CAM") (class "Default")
      (node (ref "IC1") (pin "59") (pinfunction "SDA2/RA3_59") (pintype "bidirectional"))
      (node (ref "J1") (pin "3") (pinfunction "3_3") (pintype "passive"))
      (node (ref "J2") (pin "3") (pinfunction "3_3") (pintype "passive"))
      (node (ref "R14") (pin "1") (pinfunction "1_1") (pintype "passive"))
    )
    (net (code "100") (name "/VBAT-LAN") (class "Default")
      (node (ref "D3") (pin "C") (pinfunction "C_C") (pintype "passive"))
      (node (ref "J3") (pin "1") (pinfunction "1_1") (pintype "passive"))
      (node (ref "J3") (pin "3") (pinfunction "3_3") (pintype "passive"))
      (node (ref "J4") (pin "1") (pinfunction "1_1") (pintype "passive"))
      (node (ref "J4") (pin "3") (pinfunction "3_3") (pintype "passive"))
      (node (ref "L11") (pin "2") (pinfunction "2_2") (pintype "passive"))
    )
    (net (code "101") (name "/VBAT-LAN-F") (class "Default")
      (node (ref "C33") (pin "1") (pinfunction "1_1") (pintype "passive"))
      (node (ref "C34") (pin "1") (pinfunction "1_1") (pintype "passive"))
      (node (ref "D6") (pin "K") (pinfunction "K_K") (pintype "passive"))
      (node (ref "L11") (pin "1") (pinfunction "1_1") (pintype "passive"))
      (node (ref "Q5") (pin "2") (pinfunction "S_2") (pintype "passive"))
      (node (ref "Q5") (pin "5") (pinfunction "S_5") (pintype "passive"))
      (node (ref "R132") (pin "1") (pinfunction "1_1") (pintype "passive"))
      (node (ref "R36") (pin "2") (pinfunction "2_2") (pintype "passive"))
      (node (ref "R38") (pin "2") (pinfunction "2_2") (pintype "passive"))
      (node (ref "R42") (pin "1") (pinfunction "1_1") (pintype "passive"))
      (node (ref "R45") (pin "1") (pinfunction "1_1") (pintype "passive"))
      (node (ref "R94") (pin "1") (pinfunction "1_1") (pintype "passive"))
    )
    (net (code "102") (name "/VBAT-ON") (class "Default")
      (node (ref "IC1") (pin "52") (pinfunction "RPF2/RF2_52") (pintype "bidirectional"))
      (node (ref "O42") (pin "P$1") (pinfunction "TP_P$1") (pintype "passive"))
      (node (ref "Q4") (pin "2") (pinfunction "G_2") (pintype "passive"))
      (node (ref "R132") (pin "2") (pinfunction "2_2") (pintype "passive"))
      (node (ref "R41") (pin "1") (pinfunction "1_1") (pintype "passive"))
      (node (ref "T5") (pin "P$1") (pinfunction "TP_P$1") (pintype "passive"))
    )
    (net (code "103") (name "/VBAT-SENSE") (class "Default")
      (node (ref "C64") (pin "1") (pinfunction "1_1") (pintype "passive"))
      (node (ref "IC1") (pin "26") (pinfunction "PGEC2/AN6/RPB6/RB6_26") (pintype "bidirectional"))
      (node (ref "O15") (pin "P$1") (pinfunction "TP_P$1") (pintype "passive"))
      (node (ref "R100") (pin "1") (pinfunction "1_1") (pintype "passive"))
      (node (ref "T37") (pin "P$1") (pinfunction "TP_P$1") (pintype "passive"))
    )
    (net (code "104") (name "/VBATLAN-SENSE") (class "Default")
      (node (ref "C36") (pin "1") (pinfunction "1_1") (pintype "passive"))
      (node (ref "IC1") (pin "27") (pinfunction "PGED2/AN7/RPB7/CTED3/RB7_27") (pintype "bidirectional"))
      (node (ref "O16") (pin "P$1") (pinfunction "TP_P$1") (pintype "passive"))
      (node (ref "R101") (pin "1") (pinfunction "1_1") (pintype "passive"))
      (node (ref "T38") (pin "P$1") (pinfunction "TP_P$1") (pintype "passive"))
    )
    (net (code "105") (name "/VBUS") (class "Default")
      (node (ref "IC1") (pin "54") (pinfunction "VBUS_54") (pintype "input"))
      (node (ref "R128") (pin "2") (pinfunction "2_2") (pintype "passive"))
    )
    (net (code "106") (name "/VPS-ON") (class "Default")
      (node (ref "IC1") (pin "53") (pinfunction "RPF8/RF8_53") (pintype "bidirectional"))
      (node (ref "O41") (pin "P$1") (pinfunction "TP_P$1") (pintype "passive"))
      (node (ref "Q4") (pin "5") (pinfunction "G_5") (pintype "passive"))
      (node (ref "R44") (pin "1") (pinfunction "1_1") (pintype "passive"))
      (node (ref "T7") (pin "P$1") (pinfunction "TP_P$1") (pintype "passive"))
    )
    (net (code "107") (name "/VPS-PWR") (class "Default")
      (node (ref "D4") (pin "C") (pinfunction "C_C") (pintype "passive"))
      (node (ref "J3") (pin "6") (pinfunction "6_6") (pintype "passive"))
      (node (ref "J4") (pin "6") (pinfunction "6_6") (pintype "passive"))
      (node (ref "L10") (pin "2") (pinfunction "2_2") (pintype "passive"))
    )
    (net (code "108") (name "/VPS-PWR-F") (class "Default")
      (node (ref "L10") (pin "1") (pinfunction "1_1") (pintype "passive"))
      (node (ref "Q5") (pin "4") (pinfunction "D_4") (pintype "passive"))
      (node (ref "R23") (pin "2") (pinfunction "2_2") (pintype "passive"))
    )
    (net (code "109") (name "/VPS-SENSE") (class "Default")
      (node (ref "C65") (pin "1") (pinfunction "1_1") (pintype "passive"))
      (node (ref "IC1") (pin "12") (pinfunction "AN18/C2IND/RPG8/PMA3/RG8_12") (pintype "bidirectional"))
      (node (ref "O7") (pin "P$1") (pinfunction "TP_P$1") (pintype "passive"))
      (node (ref "R48") (pin "2") (pinfunction "2_2") (pintype "passive"))
      (node (ref "R49") (pin "1") (pinfunction "1_1") (pintype "passive"))
      (node (ref "T3") (pin "P$1") (pinfunction "TP_P$1") (pintype "passive"))
    )
    (net (code "110") (name "/VSYNC") (class "Default")
      (node (ref "IC1") (pin "8") (pinfunction "RPC3/RC3_8") (pintype "bidirectional"))
      (node (ref "J1") (pin "7") (pinfunction "7_7") (pintype "passive"))
      (node (ref "J2") (pin "7") (pinfunction "7_7") (pintype "passive"))
      (node (ref "O4") (pin "P$1") (pinfunction "TP_P$1") (pintype "passive"))
      (node (ref "T19") (pin "P$1") (pinfunction "TP_P$1") (pintype "passive"))
    )
    (net (code "111") (name "/WAKE-SW") (class "Default")
      (node (ref "IC1") (pin "72") (pinfunction "RPD0/INT0/RD0_72") (pintype "bidirectional"))
      (node (ref "J14") (pin "5") (pinfunction "5_5") (pintype "passive"))
      (node (ref "O38") (pin "P$1") (pinfunction "TP_P$1") (pintype "passive"))
      (node (ref "T42") (pin "P$1") (pinfunction "TP_P$1") (pintype "passive"))
    )
    (net (code "112") (name "/WE-SRAM") (class "Default")
      (node (ref "IC1") (pin "81") (pinfunction "RPD4/PMWR/RD4_81") (pintype "bidirectional"))
      (node (ref "IC2") (pin "11") (pinfunction "~{WE}_11") (pintype "input"))
      (node (ref "R4") (pin "1") (pinfunction "1_1") (pintype "passive"))
    )
    (net (code "113") (name "/XCLK1") (class "Default")
      (node (ref "IC1") (pin "7") (pinfunction "RPC2/RC2_7") (pintype "bidirectional"))
      (node (ref "J1") (pin "13") (pinfunction "13_13") (pintype "passive"))
      (node (ref "J2") (pin "13") (pinfunction "13_13") (pintype "passive"))
      (node (ref "O3") (pin "P$1") (pinfunction "TP_P$1") (pintype "passive"))
      (node (ref "T16") (pin "P$1") (pinfunction "TP_P$1") (pintype "passive"))
    )
    (net (code "114") (name "/Y2") (class "Default")
      (node (ref "IC1") (pin "68") (pinfunction "RPD8/RTCC/RD8_68") (pintype "bidirectional"))
      (node (ref "J1") (pin "19") (pinfunction "19_19") (pintype "passive"))
      (node (ref "J2") (pin "19") (pinfunction "19_19") (pintype "passive"))
    )
    (net (code "115") (name "/Y3") (class "Default")
      (node (ref "IC1") (pin "69") (pinfunction "RPD9/RD9_69") (pintype "bidirectional"))
      (node (ref "J1") (pin "21") (pinfunction "21_21") (pintype "passive"))
      (node (ref "J2") (pin "21") (pinfunction "21_21") (pintype "passive"))
    )
    (net (code "116") (name "/Y4") (class "Default")
      (node (ref "IC1") (pin "70") (pinfunction "RPD10/SCK1/PMCS2/RD10_70") (pintype "bidirectional"))
      (node (ref "J1") (pin "22") (pinfunction "22_22") (pintype "passive"))
      (node (ref "J2") (pin "22") (pinfunction "22_22") (pintype "passive"))
    )
    (net (code "117") (name "/Y5") (class "Default")
      (node (ref "IC1") (pin "71") (pinfunction "RPD11/PMCS1/RD11_71") (pintype "bidirectional"))
      (node (ref "J1") (pin "20") (pinfunction "20_20") (pintype "passive"))
      (node (ref "J2") (pin "20") (pinfunction "20_20") (pintype "passive"))
    )
    (net (code "118") (name "/Y6") (class "Default")
      (node (ref "IC1") (pin "79") (pinfunction "RPD12/PMD12/RD12_79") (pintype "bidirectional"))
      (node (ref "J1") (pin "18") (pinfunction "18_18") (pintype "passive"))
      (node (ref "J2") (pin "18") (pinfunction "18_18") (pintype "passive"))
    )
    (net (code "119") (name "/Y7") (class "Default")
      (node (ref "IC1") (pin "80") (pinfunction "PMD13/RD13_80") (pintype "bidirectional"))
      (node (ref "J1") (pin "16") (pinfunction "16_16") (pintype "passive"))
      (node (ref "J2") (pin "16") (pinfunction "16_16") (pintype "passive"))
    )
    (net (code "120") (name "/Y8") (class "Default")
      (node (ref "IC1") (pin "47") (pinfunction "RPD14/RD14_47") (pintype "bidirectional"))
      (node (ref "J1") (pin "14") (pinfunction "14_14") (pintype "passive"))
      (node (ref "J2") (pin "14") (pinfunction "14_14") (pintype "passive"))
    )
    (net (code "121") (name "/Y9") (class "Default")
      (node (ref "IC1") (pin "48") (pinfunction "RPD15/RD15_48") (pintype "bidirectional"))
      (node (ref "J1") (pin "12") (pinfunction "12_12") (pintype "passive"))
      (node (ref "J2") (pin "12") (pinfunction "12_12") (pintype "passive"))
    )
    (net (code "122") (name "/{slash}3.3V1PWRON") (class "Default")
      (node (ref "IC1") (pin "21") (pinfunction "AN4/C1INB/USBOEN/RB4_21") (pintype "bidirectional"))
      (node (ref "O44") (pin "P$1") (pinfunction "TP_P$1") (pintype "passive"))
      (node (ref "R24") (pin "2") (pinfunction "2_2") (pintype "passive"))
      (node (ref "T32") (pin "P$1") (pinfunction "TP_P$1") (pintype "passive"))
    )
    (net (code "123") (name "/{slash}3.3V2PWRON") (class "Default")
      (node (ref "IC1") (pin "96") (pinfunction "TRD1/RG12_96") (pintype "bidirectional"))
      (node (ref "O23") (pin "P$1") (pinfunction "TP_P$1") (pintype "passive"))
      (node (ref "R75") (pin "2") (pinfunction "2_2") (pintype "passive"))
      (node (ref "T33") (pin "P$1") (pinfunction "TP_P$1") (pintype "passive"))
    )
    (net (code "124") (name "/{slash}CAM-PWRON") (class "Default")
      (node (ref "IC1") (pin "95") (pinfunction "TRD2/RG14_95") (pintype "bidirectional"))
      (node (ref "O24") (pin "P$1") (pinfunction "TP_P$1") (pintype "passive"))
      (node (ref "R10") (pin "1") (pinfunction "1_1") (pintype "passive"))
      (node (ref "T30") (pin "P$1") (pinfunction "TP_P$1") (pintype "passive"))
    )
    (net (code "125") (name "/{slash}FMEM1-CS") (class "Default")
      (node (ref "IC1") (pin "11") (pinfunction "AN17/C1INC/RPG7/PMA4/RG7_11") (pintype "bidirectional"))
      (node (ref "IC9") (pin "1") (pinfunction "/S_1") (pintype "input"))
      (node (ref "O6") (pin "P$1") (pinfunction "TP_P$1") (pintype "passive"))
      (node (ref "R25") (pin "1") (pinfunction "1_1") (pintype "passive"))
      (node (ref "T27") (pin "P$1") (pinfunction "TP_P$1") (pintype "passive"))
    )
    (net (code "126") (name "/{slash}MCLR") (class "Default")
      (node (ref "IC1") (pin "13") (pinfunction "~{MCLR}_13") (pintype "input"))
      (node (ref "J17") (pin "1") (pinfunction "1_1") (pintype "passive"))
      (node (ref "R90") (pin "2") (pinfunction "2_2") (pintype "passive"))
    )
    (net (code "127") (name "/{slash}NCS") (class "Default")
      (node (ref "IC1") (pin "23") (pinfunction "PGEC3/AN2/C2INB/RPB2/CTED13/RB2_23") (pintype "bidirectional"))
      (node (ref "J15") (pin "13") (pinfunction "13_13") (pintype "passive"))
      (node (ref "O14") (pin "P$1") (pinfunction "TP_P$1") (pintype "passive"))
      (node (ref "T26") (pin "P$1") (pinfunction "TP_P$1") (pintype "passive"))
    )
    (net (code "128") (name "/{slash}PRESENT") (class "Default")
      (node (ref "J11") (pin "G2") (pinfunction "G2_G2") (pintype "passive"))
      (node (ref "R131") (pin "2") (pinfunction "2_2") (pintype "passive"))
      (node (ref "T46") (pin "P$1") (pinfunction "TP_P$1") (pintype "passive"))
    )
    (net (code "129") (name "/{slash}VPS-PWRON") (class "Default")
      (node (ref "IC1") (pin "17") (pinfunction "TMS/CTED1/RA0_17") (pintype "bidirectional"))
      (node (ref "O9") (pin "P$1") (pinfunction "TP_P$1") (pintype "passive"))
      (node (ref "R107") (pin "2") (pinfunction "2_2") (pintype "passive"))
      (node (ref "T31") (pin "P$1") (pinfunction "TP_P$1") (pintype "passive"))
    )
    (net (code "130") (name "DGND") (class "Default")
      (node (ref "C1") (pin "2") (pinfunction "2_2") (pintype "passive"))
      (node (ref "C11") (pin "-") (pinfunction "-_-") (pintype "passive"))
      (node (ref "C12") (pin "-") (pinfunction "-_-") (pintype "passive"))
      (node (ref "C13") (pin "-") (pinfunction "-_-") (pintype "passive"))
      (node (ref "C14") (pin "-") (pinfunction "-_-") (pintype "passive"))
      (node (ref "C15") (pin "2") (pinfunction "2_2") (pintype "passive"))
      (node (ref "C16") (pin "-") (pinfunction "-_-") (pintype "passive"))
      (node (ref "C17") (pin "-") (pinfunction "-_-") (pintype "passive"))
      (node (ref "C18") (pin "2") (pinfunction "2_2") (pintype "passive"))
      (node (ref "C19") (pin "2") (pinfunction "2_2") (pintype "passive"))
      (node (ref "C2") (pin "2") (pinfunction "2_2") (pintype "passive"))
      (node (ref "C20") (pin "-") (pinfunction "-_-") (pintype "passive"))
      (node (ref "C22") (pin "2") (pinfunction "2_2") (pintype "passive"))
      (node (ref "C23") (pin "2") (pinfunction "2_2") (pintype "passive"))
      (node (ref "C24") (pin "1") (pinfunction "1_1") (pintype "passive"))
      (node (ref "C27") (pin "2") (pinfunction "2_2") (pintype "passive"))
      (node (ref "C28") (pin "2") (pinfunction "2_2") (pintype "passive"))
      (node (ref "C29") (pin "2") (pinfunction "2_2") (pintype "passive"))
      (node (ref "C30") (pin "2") (pinfunction "2_2") (pintype "passive"))
      (node (ref "C31") (pin "-") (pinfunction "-_-") (pintype "passive"))
      (node (ref "C32") (pin "2") (pinfunction "2_2") (pintype "passive"))
      (node (ref "C35") (pin "2") (pinfunction "2_2") (pintype "passive"))
      (node (ref "C36") (pin "2") (pinfunction "2_2") (pintype "passive"))
      (node (ref "C37") (pin "2") (pinfunction "2_2") (pintype "passive"))
      (node (ref "C38") (pin "2") (pinfunction "2_2") (pintype "passive"))
      (node (ref "C40") (pin "2") (pinfunction "2_2") (pintype "passive"))
      (node (ref "C41") (pin "2") (pinfunction "2_2") (pintype "passive"))
      (node (ref "C46") (pin "2") (pinfunction "2_2") (pintype "passive"))
      (node (ref "C47") (pin "2") (pinfunction "2_2") (pintype "passive"))
      (node (ref "C48") (pin "2") (pinfunction "2_2") (pintype "passive"))
      (node (ref "C49") (pin "2") (pinfunction "2_2") (pintype "passive"))
      (node (ref "C5") (pin "2") (pinfunction "2_2") (pintype "passive"))
      (node (ref "C50") (pin "2") (pinfunction "2_2") (pintype "passive"))
      (node (ref "C51") (pin "2") (pinfunction "2_2") (pintype "passive"))
      (node (ref "C52") (pin "2") (pinfunction "2_2") (pintype "passive"))
      (node (ref "C53") (pin "2") (pinfunction "2_2") (pintype "passive"))
      (node (ref "C54") (pin "-") (pinfunction "-_-") (pintype "passive"))
      (node (ref "C55") (pin "2") (pinfunction "2_2") (pintype "passive"))
      (node (ref "C56") (pin "-") (pinfunction "-_-") (pintype "passive"))
      (node (ref "C57") (pin "2") (pinfunction "2_2") (pintype "passive"))
      (node (ref "C58") (pin "2") (pinfunction "2_2") (pintype "passive"))
      (node (ref "C59") (pin "2") (pinfunction "2_2") (pintype "passive"))
      (node (ref "C6") (pin "2") (pinfunction "2_2") (pintype "passive"))
      (node (ref "C60") (pin "2") (pinfunction "2_2") (pintype "passive"))
      (node (ref "C61") (pin "2") (pinfunction "2_2") (pintype "passive"))
      (node (ref "C62") (pin "2") (pinfunction "2_2") (pintype "passive"))
      (node (ref "C63") (pin "2") (pinfunction "2_2") (pintype "passive"))
      (node (ref "C64") (pin "2") (pinfunction "2_2") (pintype "passive"))
      (node (ref "C65") (pin "2") (pinfunction "2_2") (pintype "passive"))
      (node (ref "C66") (pin "2") (pinfunction "2_2") (pintype "passive"))
      (node (ref "C67") (pin "2") (pinfunction "2_2") (pintype "passive"))
      (node (ref "C7") (pin "1") (pinfunction "1_1") (pintype "passive"))
      (node (ref "C75") (pin "2") (pinfunction "2_2") (pintype "passive"))
      (node (ref "C76") (pin "2") (pinfunction "2_2") (pintype "passive"))
      (node (ref "C77") (pin "2") (pinfunction "2_2") (pintype "passive"))
      (node (ref "C78") (pin "2") (pinfunction "2_2") (pintype "passive"))
      (node (ref "C79") (pin "2") (pinfunction "2_2") (pintype "passive"))
      (node (ref "C8") (pin "1") (pinfunction "1_1") (pintype "passive"))
      (node (ref "C80") (pin "2") (pinfunction "2_2") (pintype "passive"))
      (node (ref "C81") (pin "-") (pinfunction "-_-") (pintype "passive"))
      (node (ref "C82") (pin "2") (pinfunction "2_2") (pintype "passive"))
      (node (ref "C83") (pin "2") (pinfunction "2_2") (pintype "passive"))
      (node (ref "C84") (pin "2") (pinfunction "2_2") (pintype "passive"))
      (node (ref "C85") (pin "2") (pinfunction "2_2") (pintype "passive"))
      (node (ref "C86") (pin "-") (pinfunction "-_-") (pintype "passive"))
      (node (ref "C87") (pin "-") (pinfunction "-_-") (pintype "passive"))
      (node (ref "C88") (pin "2") (pinfunction "2_2") (pintype "passive"))
      (node (ref "D2") (pin "-") (pinfunction "A_-") (pintype "passive"))
      (node (ref "D5") (pin "K") (pinfunction "K_K") (pintype "passive"))
      (node (ref "D7") (pin "A") (pinfunction "A_A") (pintype "passive"))
      (node (ref "IC1") (pin "15") (pinfunction "VSS2_15") (pintype "input"))
      (node (ref "IC1") (pin "31") (pinfunction "AVSS_31") (pintype "input"))
      (node (ref "IC1") (pin "36") (pinfunction "VSS3_36") (pintype "input"))
      (node (ref "IC1") (pin "45") (pinfunction "VSS4_45") (pintype "input"))
      (node (ref "IC1") (pin "65") (pinfunction "VSS5_65") (pintype "input"))
      (node (ref "IC1") (pin "75") (pinfunction "VSS1_75") (pintype "input"))
      (node (ref "IC10") (pin "1") (pinfunction "GND_1") (pintype "input"))
      (node (ref "IC10") (pin "2") (pinfunction "GND1_2") (pintype "input"))
      (node (ref "IC11") (pin "1") (pinfunction "A0_1") (pintype "input"))
      (node (ref "IC11") (pin "3") (pinfunction "A2_3") (pintype "input"))
      (node (ref "IC11") (pin "4") (pinfunction "GND_4") (pintype "input"))
      (node (ref "IC12") (pin "5") (pinfunction "GND_5") (pintype "input"))
      (node (ref "IC13") (pin "3") (pinfunction "GND_3") (pintype "bidirectional"))
      (node (ref "IC15") (pin "1") (pinfunction "1_1") (pintype "input"))
      (node (ref "IC16") (pin "4") (pinfunction "V-_4") (pintype "input"))
      (node (ref "IC2") (pin "14") (pinfunction "~{UB}_14") (pintype "input"))
      (node (ref "IC2") (pin "15") (pinfunction "~{LB}_15") (pintype "input"))
      (node (ref "IC2") (pin "26") (pinfunction "~{CS1}_26") (pintype "input"))
      (node (ref "IC2") (pin "27") (pinfunction "GND1_27") (pintype "bidirectional"))
      (node (ref "IC2") (pin "46") (pinfunction "GND2_46") (pintype "bidirectional"))
      (node (ref "IC2") (pin "47") (pinfunction "~{BYTE}_47") (pintype "input"))
      (node (ref "IC3") (pin "1") (pinfunction "~{OE}_1") (pintype "input"))
      (node (ref "IC3") (pin "10") (pinfunction "GND_10") (pintype "bidirectional"))
      (node (ref "IC4") (pin "1") (pinfunction "~{OE}_1") (pintype "input"))
      (node (ref "IC4") (pin "10") (pinfunction "GND_10") (pintype "bidirectional"))
      (node (ref "IC5") (pin "2") (pinfunction "GND_2") (pintype "input"))
      (node (ref "IC6") (pin "2") (pinfunction "GND_2") (pintype "input"))
      (node (ref "IC7") (pin "1") (pinfunction "A0_1") (pintype "input"))
      (node (ref "IC7") (pin "2") (pinfunction "A1_2") (pintype "input"))
      (node (ref "IC7") (pin "3") (pinfunction "A2_3") (pintype "input"))
      (node (ref "IC7") (pin "4") (pinfunction "GND_4") (pintype "input"))
      (node (ref "IC7") (pin "7") (pinfunction "WP_7") (pintype "input"))
      (node (ref "IC8") (pin "10") (pinfunction "SYNC_10") (pintype "bidirectional"))
      (node (ref "IC8") (pin "EP") (pinfunction "GND_EP") (pintype "bidirectional"))
      (node (ref "IC9") (pin "4") (pinfunction "GND_4") (pintype "input"))
      (node (ref "J1") (pin "15") (pinfunction "15_15") (pintype "passive"))
      (node (ref "J11") (pin "6") (pinfunction "VSS_6") (pintype "passive"))
      (node (ref "J11") (pin "G1") (pinfunction "G1_G1") (pintype "passive"))
      (node (ref "J11") (pin "G3") (pinfunction "G3_G3") (pintype "passive"))
      (node (ref "J11") (pin "G4") (pinfunction "G4_G4") (pintype "passive"))
      (node (ref "J11") (pin "G5") (pinfunction "G5_G5") (pintype "passive"))
      (node (ref "J11") (pin "G6") (pinfunction "G6_G6") (pintype "passive"))
      (node (ref "J12") (pin "4_GND") (pinfunction "GND_4_GND") (pintype "bidirectional"))
      (node (ref "J12") (pin "SH1") (pinfunction "GND_SH1_SH1") (pintype "bidirectional"))
      (node (ref "J12") (pin "SH2") (pinfunction "GND_SH2_SH2") (pintype "bidirectional"))
      (node (ref "J14") (pin "1") (pinfunction "1_1") (pintype "passive"))
      (node (ref "J15") (pin "9") (pinfunction "9_9") (pintype "passive"))
      (node (ref "J17") (pin "3") (pinfunction "3_3") (pintype "passive"))
      (node (ref "J2") (pin "15") (pinfunction "15_15") (pintype "passive"))
      (node (ref "J5") (pin "1") (pinfunction "1_1") (pintype "bidirectional"))
      (node (ref "J6") (pin "1") (pinfunction "1_1") (pintype "bidirectional"))
      (node (ref "L12") (pin "1") (pinfunction "1_1") (pintype "passive"))
      (node (ref "PCB1") (pin "PAD_GND_1") (pinfunction "PAD_GND_1_PAD_GND_1") (pintype "bidirectional"))
      (node (ref "PCB1") (pin "PAD_GND_2") (pinfunction "PAD_GND_2_PAD_GND_2") (pintype "bidirectional"))
      (node (ref "PCB1") (pin "PAD_GND_3") (pinfunction "PAD_GND_3_PAD_GND_3") (pintype "bidirectional"))
      (node (ref "PCB1") (pin "PAD_GND_4") (pinfunction "PAD_GND_4_PAD_GND_4") (pintype "bidirectional"))
      (node (ref "PCB2") (pin "VPS_PCB_1") (pinfunction "VPS_PCB_1_VPS_PCB_1") (pintype "bidirectional"))
      (node (ref "PCB3") (pin "1") (pinfunction "P$1_1") (pintype "bidirectional"))
      (node (ref "Q10") (pin "4") (pinfunction "S_4") (pintype "passive"))
      (node (ref "Q11") (pin "4") (pinfunction "S_4") (pintype "passive"))
      (node (ref "Q12") (pin "4") (pinfunction "S_4") (pintype "passive"))
      (node (ref "Q13") (pin "4") (pinfunction "S_4") (pintype "passive"))
      (node (ref "Q14") (pin "1") (pinfunction "S_1") (pintype "passive"))
      (node (ref "Q3") (pin "1") (pinfunction "S_1") (pintype "passive"))
      (node (ref "R1") (pin "1") (pinfunction "1_1") (pintype "passive"))
      (node (ref "R112") (pin "2") (pinfunction "2_2") (pintype "passive"))
      (node (ref "R118") (pin "2") (pinfunction "2_2") (pintype "passive"))
      (node (ref "R127") (pin "1") (pinfunction "1_1") (pintype "passive"))
      (node (ref "R17") (pin "2") (pinfunction "2_2") (pintype "passive"))
      (node (ref "R19") (pin "2") (pinfunction "2_2") (pintype "passive"))
      (node (ref "R2") (pin "1") (pinfunction "1_1") (pintype "passive"))
      (node (ref "R21") (pin "2") (pinfunction "2_2") (pintype "passive"))
      (node (ref "R31") (pin "2") (pinfunction "2_2") (pintype "passive"))
      (node (ref "R40") (pin "1") (pinfunction "1_1") (pintype "passive"))
      (node (ref "R41") (pin "2") (pinfunction "2_2") (pintype "passive"))
      (node (ref "R43") (pin "1") (pinfunction "1_1") (pintype "passive"))
      (node (ref "R44") (pin "2") (pinfunction "2_2") (pintype "passive"))
      (node (ref "R46") (pin "1") (pinfunction "1_1") (pintype "passive"))
      (node (ref "R48") (pin "1") (pinfunction "1_1") (pintype "passive"))
      (node (ref "R5") (pin "1") (pinfunction "1_1") (pintype "passive"))
      (node (ref "R51") (pin "1") (pinfunction "1_1") (pintype "passive"))
      (node (ref "R52") (pin "2") (pinfunction "2_2") (pintype "passive"))
      (node (ref "R53") (pin "2") (pinfunction "2_2") (pintype "passive"))
      (node (ref "R54") (pin "2") (pinfunction "2_2") (pintype "passive"))
      (node (ref "R57") (pin "1") (pinfunction "1_1") (pintype "passive"))
      (node (ref "R58") (pin "2") (pinfunction "2_2") (pintype "passive"))
      (node (ref "R59") (pin "2") (pinfunction "2_2") (pintype "passive"))
      (node (ref "R6") (pin "2") (pinfunction "2_2") (pintype "passive"))
      (node (ref "R60") (pin "2") (pinfunction "2_2") (pintype "passive"))
      (node (ref "R64") (pin "2") (pinfunction "2_2") (pintype "passive"))
      (node (ref "R67") (pin "2") (pinfunction "2_2") (pintype "passive"))
      (node (ref "R7") (pin "2") (pinfunction "2_2") (pintype "passive"))
      (node (ref "R70") (pin "2") (pinfunction "2_2") (pintype "passive"))
      (node (ref "R71") (pin "2") (pinfunction "2_2") (pintype "passive"))
      (node (ref "R76") (pin "2") (pinfunction "2_2") (pintype "passive"))
      (node (ref "R80") (pin "2") (pinfunction "2_2") (pintype "passive"))
      (node (ref "R83") (pin "2") (pinfunction "2_2") (pintype "passive"))
      (node (ref "R86") (pin "2") (pinfunction "2_2") (pintype "passive"))
      (node (ref "R88") (pin "2") (pinfunction "2_2") (pintype "passive"))
      (node (ref "R96") (pin "2") (pinfunction "2_2") (pintype "passive"))
      (node (ref "R99") (pin "2") (pinfunction "2_2") (pintype "passive"))
    )
    (net (code "131") (name "Net-(C24-Pad2)") (class "Default")
      (node (ref "C24") (pin "2") (pinfunction "2_2") (pintype "passive"))
      (node (ref "R77") (pin "2") (pinfunction "2_2") (pintype "passive"))
    )
    (net (code "132") (name "Net-(C32-Pad1)") (class "Default")
      (node (ref "C32") (pin "1") (pinfunction "1_1") (pintype "passive"))
      (node (ref "R68") (pin "2") (pinfunction "2_2") (pintype "passive"))
      (node (ref "R69") (pin "1") (pinfunction "1_1") (pintype "passive"))
    )
    (net (code "133") (name "Net-(C37-Pad1)") (class "Default")
      (node (ref "C37") (pin "1") (pinfunction "1_1") (pintype "passive"))
      (node (ref "R78") (pin "2") (pinfunction "2_2") (pintype "passive"))
      (node (ref "R79") (pin "1") (pinfunction "1_1") (pintype "passive"))
    )
    (net (code "134") (name "Net-(C38-Pad1)") (class "Default")
      (node (ref "C38") (pin "1") (pinfunction "1_1") (pintype "passive"))
      (node (ref "R84") (pin "2") (pinfunction "2_2") (pintype "passive"))
      (node (ref "R85") (pin "1") (pinfunction "1_1") (pintype "passive"))
    )
    (net (code "135") (name "Net-(C39-Pad1)") (class "Default")
      (node (ref "C39") (pin "1") (pinfunction "1_1") (pintype "passive"))
      (node (ref "IC14") (pin "4") (pinfunction "4_4") (pintype "input"))
      (node (ref "R30") (pin "1") (pinfunction "1_1") (pintype "passive"))
    )
    (net (code "136") (name "Net-(C39-Pad2)") (class "Default")
      (node (ref "C39") (pin "2") (pinfunction "2_2") (pintype "passive"))
      (node (ref "D3") (pin "A") (pinfunction "A_A") (pintype "passive"))
      (node (ref "D4") (pin "A") (pinfunction "A_A") (pintype "passive"))
      (node (ref "IC14") (pin "1") (pinfunction "1_1") (pintype "input"))
      (node (ref "J3") (pin "2") (pinfunction "2_2") (pintype "passive"))
      (node (ref "J3") (pin "7") (pinfunction "7_7") (pintype "passive"))
      (node (ref "J3") (pin "8") (pinfunction "8_8") (pintype "passive"))
      (node (ref "J4") (pin "2") (pinfunction "2_2") (pintype "passive"))
      (node (ref "J4") (pin "7") (pinfunction "7_7") (pintype "passive"))
      (node (ref "J4") (pin "8") (pinfunction "8_8") (pintype "passive"))
      (node (ref "L12") (pin "2") (pinfunction "2_2") (pintype "passive"))
    )
    (net (code "137") (name "Net-(C40-Pad1)") (class "Default")
      (node (ref "C40") (pin "1") (pinfunction "1_1") (pintype "passive"))
      (node (ref "R90") (pin "1") (pinfunction "1_1") (pintype "passive"))
      (node (ref "R91") (pin "1") (pinfunction "1_1") (pintype "passive"))
    )
    (net (code "138") (name "Net-(C46-Pad1)") (class "Default")
      (node (ref "C46") (pin "1") (pinfunction "1_1") (pintype "passive"))
      (node (ref "R62") (pin "2") (pinfunction "2_2") (pintype "passive"))
      (node (ref "R63") (pin "1") (pinfunction "1_1") (pintype "passive"))
    )
    (net (code "139") (name "Net-(C71-Pad+)") (class "Default")
      (node (ref "C71") (pin "+") (pinfunction "+_+") (pintype "passive"))
      (node (ref "C72") (pin "1") (pinfunction "1_1") (pintype "passive"))
      (node (ref "J9") (pin "1") (pinfunction "1_1") (pintype "passive"))
      (node (ref "R124") (pin "2") (pinfunction "2_2") (pintype "passive"))
    )
    (net (code "140") (name "Net-(C71-Pad-)") (class "Default")
      (node (ref "C71") (pin "-") (pinfunction "-_-") (pintype "passive"))
      (node (ref "C72") (pin "2") (pinfunction "2_2") (pintype "passive"))
      (node (ref "R110") (pin "2") (pinfunction "2_2") (pintype "passive"))
      (node (ref "R111") (pin "1") (pinfunction "1_1") (pintype "passive"))
      (node (ref "R114") (pin "2") (pinfunction "2_2") (pintype "passive"))
      (node (ref "R115") (pin "1") (pinfunction "1_1") (pintype "passive"))
    )
    (net (code "141") (name "Net-(C73-Pad+)") (class "Default")
      (node (ref "C73") (pin "+") (pinfunction "+_+") (pintype "passive"))
      (node (ref "C74") (pin "1") (pinfunction "1_1") (pintype "passive"))
      (node (ref "J10") (pin "1") (pinfunction "1_1") (pintype "passive"))
      (node (ref "R125") (pin "2") (pinfunction "2_2") (pintype "passive"))
    )
    (net (code "142") (name "Net-(C73-Pad-)") (class "Default")
      (node (ref "C73") (pin "-") (pinfunction "-_-") (pintype "passive"))
      (node (ref "C74") (pin "2") (pinfunction "2_2") (pintype "passive"))
      (node (ref "R116") (pin "2") (pinfunction "2_2") (pintype "passive"))
      (node (ref "R117") (pin "1") (pinfunction "1_1") (pintype "passive"))
      (node (ref "R122") (pin "2") (pinfunction "2_2") (pintype "passive"))
      (node (ref "R123") (pin "1") (pinfunction "1_1") (pintype "passive"))
    )
    (net (code "143") (name "Net-(D2-C)") (class "Default")
      (node (ref "C26") (pin "1") (pinfunction "1_1") (pintype "passive"))
      (node (ref "C30") (pin "1") (pinfunction "1_1") (pintype "passive"))
      (node (ref "C31") (pin "+") (pinfunction "+_+") (pintype "passive"))
      (node (ref "D2") (pin "+") (pinfunction "C_+") (pintype "passive"))
      (node (ref "IC8") (pin "1") (pinfunction "BD_1") (pintype "bidirectional"))
      (node (ref "L9") (pin "2") (pinfunction "2_2") (pintype "passive"))
      (node (ref "R129") (pin "2") (pinfunction "2_2") (pintype "passive"))
      (node (ref "R20") (pin "1") (pinfunction "1_1") (pintype "passive"))
    )
    (net (code "144") (name "Net-(D5-PadA)") (class "Default")
      (node (ref "D5") (pin "A") (pinfunction "A_A") (pintype "passive"))
      (node (ref "R29") (pin "2") (pinfunction "2_2") (pintype "passive"))
    )
    (net (code "145") (name "Net-(IC1-AVDD)") (class "Default")
      (node (ref "C55") (pin "1") (pinfunction "1_1") (pintype "passive"))
      (node (ref "C56") (pin "+") (pinfunction "+_+") (pintype "passive"))
      (node (ref "C88") (pin "1") (pinfunction "1_1") (pintype "passive"))
      (node (ref "IC1") (pin "30") (pinfunction "AVDD_30") (pintype "input"))
      (node (ref "R92") (pin "2") (pinfunction "2_2") (pintype "passive"))
    )
    (net (code "146") (name "Net-(IC1-CLKI{slash}RC12{slash}OSC1)") (class "Default")
      (node (ref "C60") (pin "1") (pinfunction "1_1") (pintype "passive"))
      (node (ref "IC1") (pin "63") (pinfunction "CLKI/RC12/OSC1_63") (pintype "bidirectional"))
      (node (ref "X1") (pin "3") (pinfunction "2_3") (pintype "passive"))
    )
    (net (code "147") (name "Net-(IC1-CLKO{slash}RC15{slash}OSC2)") (class "Default")
      (node (ref "C61") (pin "1") (pinfunction "1_1") (pintype "passive"))
      (node (ref "IC1") (pin "64") (pinfunction "CLKO/RC15/OSC2_64") (pintype "bidirectional"))
      (node (ref "X1") (pin "1") (pinfunction "1_1") (pintype "passive"))
    )
    (net (code "148") (name "Net-(IC1-VCAP)") (class "Default")
      (node (ref "C53") (pin "1") (pinfunction "1_1") (pintype "passive"))
      (node (ref "C54") (pin "+") (pinfunction "+_+") (pintype "passive"))
      (node (ref "IC1") (pin "85") (pinfunction "VCAP_85") (pintype "input"))
    )
    (net (code "149") (name "Net-(IC5-OUT)") (class "Default")
      (node (ref "C19") (pin "1") (pinfunction "1_1") (pintype "passive"))
      (node (ref "C20") (pin "+") (pinfunction "+_+") (pintype "passive"))
      (node (ref "IC5") (pin "5") (pinfunction "OUT_5") (pintype "output"))
      (node (ref "R126") (pin "2") (pinfunction "2_2") (pintype "passive"))
    )
    (net (code "150") (name "Net-(IC6-HTH)") (class "Default")
      (node (ref "IC6") (pin "1") (pinfunction "HTH_1") (pintype "input"))
      (node (ref "R46") (pin "2") (pinfunction "2_2") (pintype "passive"))
      (node (ref "R47") (pin "1") (pinfunction "1_1") (pintype "passive"))
    )
    (net (code "151") (name "Net-(IC6-LTH)") (class "Default")
      (node (ref "IC6") (pin "3") (pinfunction "LTH_3") (pintype "input"))
      (node (ref "R33") (pin "1") (pinfunction "1_1") (pintype "passive"))
      (node (ref "R47") (pin "2") (pinfunction "2_2") (pintype "passive"))
    )
    (net (code "152") (name "Net-(IC6-VDD)") (class "Default")
      (node (ref "C35") (pin "1") (pinfunction "1_1") (pintype "passive"))
      (node (ref "IC6") (pin "5") (pinfunction "VDD_5") (pintype "input"))
      (node (ref "R28") (pin "1") (pinfunction "1_1") (pintype "passive"))
    )
    (net (code "153") (name "Net-(IC8-BOOST)") (class "Default")
      (node (ref "C25") (pin "2") (pinfunction "2_2") (pintype "passive"))
      (node (ref "IC8") (pin "2") (pinfunction "BOOST_2") (pintype "bidirectional"))
    )
    (net (code "154") (name "Net-(IC8-EN)") (class "Default")
      (node (ref "IC8") (pin "5") (pinfunction "EN_5") (pintype "bidirectional"))
      (node (ref "JP1") (pin "2") (pinfunction "2_2") (pintype "bidirectional"))
      (node (ref "R22") (pin "2") (pinfunction "2_2") (pintype "passive"))
    )
    (net (code "155") (name "Net-(IC8-FB)") (class "Default")
      (node (ref "C26") (pin "2") (pinfunction "2_2") (pintype "passive"))
      (node (ref "IC8") (pin "6") (pinfunction "FB_6") (pintype "bidirectional"))
      (node (ref "R19") (pin "1") (pinfunction "1_1") (pintype "passive"))
      (node (ref "R20") (pin "2") (pinfunction "2_2") (pintype "passive"))
    )
    (net (code "156") (name "Net-(IC8-RT)") (class "Default")
      (node (ref "IC8") (pin "8") (pinfunction "RT_8") (pintype "bidirectional"))
      (node (ref "R17") (pin "1") (pinfunction "1_1") (pintype "passive"))
    )
    (net (code "157") (name "Net-(IC8-SS)") (class "Default")
      (node (ref "IC8") (pin "7") (pinfunction "SS_7") (pintype "bidirectional"))
      (node (ref "R77") (pin "1") (pinfunction "1_1") (pintype "passive"))
    )
    (net (code "158") (name "Net-(IC8-SW)") (class "Default")
      (node (ref "C25") (pin "1") (pinfunction "1_1") (pintype "passive"))
      (node (ref "D7") (pin "K") (pinfunction "K_K") (pintype "passive"))
      (node (ref "IC8") (pin "3") (pinfunction "SW_3") (pintype "bidirectional"))
      (node (ref "L9") (pin "1") (pinfunction "1_1") (pintype "passive"))
    )
    (net (code "159") (name "Net-(IC10-OUT)") (class "Default")
      (node (ref "IC10") (pin "3") (pinfunction "OUT_3") (pintype "output"))
      (node (ref "R102") (pin "1") (pinfunction "1_1") (pintype "passive"))
    )
    (net (code "160") (name "Net-(IC10-VIN+)") (class "Default")
      (node (ref "C29") (pin "1") (pinfunction "1_1") (pintype "passive"))
      (node (ref "F1") (pin "1") (pinfunction "1_1") (pintype "passive"))
      (node (ref "IC10") (pin "5") (pinfunction "VIN+_5") (pintype "input"))
      (node (ref "R39") (pin "2") (pinfunction "2_2") (pintype "passive"))
    )
    (net (code "161") (name "Net-(IC11-WP)") (class "Default")
      (node (ref "IC11") (pin "7") (pinfunction "WP_7") (pintype "input"))
      (node (ref "R18") (pin "2") (pinfunction "2_2") (pintype "passive"))
      (node (ref "TP1") (pin "P$1") (pinfunction "TP_P$1") (pintype "passive"))
    )
    (net (code "162") (name "Net-(IC13-VIN)") (class "Default")
      (node (ref "C58") (pin "1") (pinfunction "1_1") (pintype "passive"))
      (node (ref "C59") (pin "1") (pinfunction "1_1") (pintype "passive"))
      (node (ref "IC13") (pin "1") (pinfunction "VIN_1") (pintype "bidirectional"))
      (node (ref "R93") (pin "2") (pinfunction "2_2") (pintype "passive"))
    )
    (net (code "163") (name "Net-(IC16A-+IN)") (class "Default")
      (node (ref "C62") (pin "1") (pinfunction "1_1") (pintype "passive"))
      (node (ref "IC16") (pin "3") (pinfunction "+IN_3") (pintype "input"))
      (node (ref "R95") (pin "2") (pinfunction "2_2") (pintype "passive"))
      (node (ref "R96") (pin "1") (pinfunction "1_1") (pintype "passive"))
    )
    (net (code "164") (name "Net-(IC16A--IN)") (class "Default")
      (node (ref "IC16") (pin "1") (pinfunction "OUT_1") (pintype "output"))
      (node (ref "IC16") (pin "2") (pinfunction "-IN_2") (pintype "input"))
      (node (ref "R101") (pin "2") (pinfunction "2_2") (pintype "passive"))
    )
    (net (code "165") (name "Net-(IC16B-+IN)") (class "Default")
      (node (ref "C63") (pin "1") (pinfunction "1_1") (pintype "passive"))
      (node (ref "IC16") (pin "5") (pinfunction "+IN_5") (pintype "input"))
      (node (ref "R98") (pin "2") (pinfunction "2_2") (pintype "passive"))
      (node (ref "R99") (pin "1") (pinfunction "1_1") (pintype "passive"))
    )
    (net (code "166") (name "Net-(IC16B--IN)") (class "Default")
      (node (ref "IC16") (pin "6") (pinfunction "-IN_6") (pintype "input"))
      (node (ref "IC16") (pin "7") (pinfunction "OUT_7") (pintype "output"))
      (node (ref "R100") (pin "2") (pinfunction "2_2") (pintype "passive"))
    )
    (net (code "167") (name "Net-(IC16C-V+)") (class "Default")
      (node (ref "C67") (pin "1") (pinfunction "1_1") (pintype "passive"))
      (node (ref "IC16") (pin "8") (pinfunction "V+_8") (pintype "input"))
      (node (ref "R103") (pin "1") (pinfunction "1_1") (pintype "passive"))
    )
    (net (code "168") (name "Net-(J5-Pad4)") (class "Default")
      (node (ref "J5") (pin "4") (pinfunction "4_4") (pintype "bidirectional"))
      (node (ref "R62") (pin "1") (pinfunction "1_1") (pintype "passive"))
    )
    (net (code "169") (name "Net-(J6-Pad4)") (class "Default")
      (node (ref "J6") (pin "4") (pinfunction "4_4") (pintype "bidirectional"))
      (node (ref "R78") (pin "1") (pinfunction "1_1") (pintype "passive"))
    )
    (net (code "170") (name "Net-(J7-Pad2)") (class "Default")
      (node (ref "J7") (pin "2") (pinfunction "2_2") (pintype "passive"))
      (node (ref "R68") (pin "1") (pinfunction "1_1") (pintype "passive"))
    )
    (net (code "171") (name "Net-(J8-Pad2)") (class "Default")
      (node (ref "J8") (pin "2") (pinfunction "2_2") (pintype "passive"))
      (node (ref "R84") (pin "1") (pinfunction "1_1") (pintype "passive"))
    )
    (net (code "172") (name "Net-(J9-Pad2)") (class "Default")
      (node (ref "J9") (pin "2") (pinfunction "2_2") (pintype "passive"))
      (node (ref "R110") (pin "1") (pinfunction "1_1") (pintype "passive"))
      (node (ref "R114") (pin "1") (pinfunction "1_1") (pintype "passive"))
    )
    (net (code "173") (name "Net-(J10-Pad2)") (class "Default")
      (node (ref "J10") (pin "2") (pinfunction "2_2") (pintype "passive"))
      (node (ref "R116") (pin "1") (pinfunction "1_1") (pintype "passive"))
      (node (ref "R122") (pin "1") (pinfunction "1_1") (pintype "passive"))
    )
    (net (code "174") (name "Net-(J12-+5V)") (class "Default")
      (node (ref "C85") (pin "1") (pinfunction "1_1") (pintype "passive"))
      (node (ref "D6") (pin "A") (pinfunction "A_A") (pintype "passive"))
      (node (ref "IC15") (pin "4") (pinfunction "4_4") (pintype "input"))
      (node (ref "J12") (pin "1_+5V") (pinfunction "+5V_1_+5V") (pintype "bidirectional"))
      (node (ref "R128") (pin "1") (pinfunction "1_1") (pintype "passive"))
    )
    (net (code "175") (name "Net-(JP1-Pad1)") (class "Default")
      (node (ref "JP1") (pin "1") (pinfunction "1_1") (pintype "bidirectional"))
      (node (ref "R21") (pin "1") (pinfunction "1_1") (pintype "passive"))
    )
    (net (code "176") (name "Net-(L13-Pad2)") (class "Default")
      (node (ref "L13") (pin "2") (pinfunction "2_2") (pintype "passive"))
      (node (ref "R92") (pin "1") (pinfunction "1_1") (pintype "passive"))
    )
    (net (code "177") (name "Net-(Q1A-G)") (class "Default")
      (node (ref "C21") (pin "2") (pinfunction "2_2") (pintype "passive"))
      (node (ref "Q1") (pin "2") (pinfunction "G_2") (pintype "passive"))
      (node (ref "R10") (pin "2") (pinfunction "2_2") (pintype "passive"))
      (node (ref "R9") (pin "1") (pinfunction "1_1") (pintype "passive"))
    )
    (net (code "178") (name "Net-(Q1A-S)") (class "Default")
      (node (ref "Q1") (pin "1") (pinfunction "S_1") (pintype "passive"))
      (node (ref "R8") (pin "1") (pinfunction "1_1") (pintype "passive"))
    )
    (net (code "179") (name "Net-(Q1B-G)") (class "Default")
      (node (ref "C70") (pin "2") (pinfunction "2_2") (pintype "passive"))
      (node (ref "Q1") (pin "5") (pinfunction "G_5") (pintype "passive"))
      (node (ref "R75") (pin "1") (pinfunction "1_1") (pintype "passive"))
      (node (ref "R82") (pin "2") (pinfunction "2_2") (pintype "passive"))
    )
    (net (code "180") (name "Net-(Q1B-S)") (class "Default")
      (node (ref "Q1") (pin "4") (pinfunction "S_4") (pintype "passive"))
      (node (ref "R106") (pin "1") (pinfunction "1_1") (pintype "passive"))
    )
    (net (code "181") (name "Net-(Q2A-G)") (class "Default")
      (node (ref "C68") (pin "2") (pinfunction "2_2") (pintype "passive"))
      (node (ref "Q2") (pin "2") (pinfunction "G_2") (pintype "passive"))
      (node (ref "R107") (pin "1") (pinfunction "1_1") (pintype "passive"))
      (node (ref "R87") (pin "2") (pinfunction "2_2") (pintype "passive"))
    )
    (net (code "182") (name "Net-(Q2A-S)") (class "Default")
      (node (ref "Q2") (pin "1") (pinfunction "S_1") (pintype "passive"))
      (node (ref "R104") (pin "1") (pinfunction "1_1") (pintype "passive"))
    )
    (net (code "183") (name "Net-(Q2B-G)") (class "Default")
      (node (ref "C69") (pin "2") (pinfunction "2_2") (pintype "passive"))
      (node (ref "Q2") (pin "5") (pinfunction "G_5") (pintype "passive"))
      (node (ref "R24") (pin "1") (pinfunction "1_1") (pintype "passive"))
      (node (ref "R65") (pin "2") (pinfunction "2_2") (pintype "passive"))
    )
    (net (code "184") (name "Net-(Q2B-S)") (class "Default")
      (node (ref "Q2") (pin "4") (pinfunction "S_4") (pintype "passive"))
      (node (ref "R105") (pin "1") (pinfunction "1_1") (pintype "passive"))
    )
    (net (code "185") (name "Net-(Q3A-D)") (class "Default")
      (node (ref "Q3") (pin "6") (pinfunction "D_6") (pintype "passive"))
      (node (ref "R111") (pin "2") (pinfunction "2_2") (pintype "passive"))
      (node (ref "R115") (pin "2") (pinfunction "2_2") (pintype "passive"))
    )
    (net (code "186") (name "Net-(Q3A-G)") (class "Default")
      (node (ref "Q3") (pin "2") (pinfunction "G_2") (pintype "passive"))
      (node (ref "R112") (pin "1") (pinfunction "1_1") (pintype "passive"))
      (node (ref "R113") (pin "1") (pinfunction "1_1") (pintype "passive"))
    )
    (net (code "187") (name "Net-(Q4A-D)") (class "Default")
      (node (ref "C33") (pin "2") (pinfunction "2_2") (pintype "passive"))
      (node (ref "Q4") (pin "6") (pinfunction "D_6") (pintype "passive"))
      (node (ref "Q5") (pin "1") (pinfunction "G_1") (pintype "passive"))
      (node (ref "R42") (pin "2") (pinfunction "2_2") (pintype "passive"))
    )
    (net (code "188") (name "Net-(Q4A-S)") (class "Default")
      (node (ref "Q4") (pin "1") (pinfunction "S_1") (pintype "passive"))
      (node (ref "R40") (pin "2") (pinfunction "2_2") (pintype "passive"))
    )
    (net (code "189") (name "Net-(Q4B-D)") (class "Default")
      (node (ref "C34") (pin "2") (pinfunction "2_2") (pintype "passive"))
      (node (ref "Q4") (pin "3") (pinfunction "D_3") (pintype "passive"))
      (node (ref "Q5") (pin "3") (pinfunction "G_3") (pintype "passive"))
      (node (ref "R45") (pin "2") (pinfunction "2_2") (pintype "passive"))
    )
    (net (code "190") (name "Net-(Q4B-S)") (class "Default")
      (node (ref "Q4") (pin "4") (pinfunction "S_4") (pintype "passive"))
      (node (ref "R43") (pin "2") (pinfunction "2_2") (pintype "passive"))
    )
    (net (code "191") (name "Net-(Q5A-D)") (class "Default")
      (node (ref "F1") (pin "2") (pinfunction "2_2") (pintype "passive"))
      (node (ref "Q5") (pin "6") (pinfunction "D_6") (pintype "passive"))
      (node (ref "R35") (pin "1") (pinfunction "1_1") (pintype "passive"))
      (node (ref "R37") (pin "1") (pinfunction "1_1") (pintype "passive"))
      (node (ref "R97") (pin "1") (pinfunction "1_1") (pintype "passive"))
    )
    (net (code "192") (name "Net-(Q6A-G)") (class "Default")
      (node (ref "C42") (pin "2") (pinfunction "2_2") (pintype "passive"))
      (node (ref "Q6") (pin "1") (pinfunction "G_1") (pintype "passive"))
      (node (ref "Q7") (pin "6") (pinfunction "D_6") (pintype "passive"))
      (node (ref "R50") (pin "2") (pinfunction "2_2") (pintype "passive"))
    )
    (net (code "193") (name "Net-(Q6B-G)") (class "Default")
      (node (ref "C43") (pin "2") (pinfunction "2_2") (pintype "passive"))
      (node (ref "Q6") (pin "3") (pinfunction "G_3") (pintype "passive"))
      (node (ref "Q7") (pin "3") (pinfunction "D_3") (pintype "passive"))
      (node (ref "R55") (pin "2") (pinfunction "2_2") (pintype "passive"))
    )
    (net (code "194") (name "Net-(Q7A-S)") (class "Default")
      (node (ref "Q7") (pin "1") (pinfunction "S_1") (pintype "passive"))
      (node (ref "R51") (pin "2") (pinfunction "2_2") (pintype "passive"))
    )
    (net (code "195") (name "Net-(Q7B-S)") (class "Default")
      (node (ref "Q7") (pin "4") (pinfunction "S_4") (pintype "passive"))
      (node (ref "R53") (pin "1") (pinfunction "1_1") (pintype "passive"))
    )
    (net (code "196") (name "Net-(Q8A-G)") (class "Default")
      (node (ref "C44") (pin "2") (pinfunction "2_2") (pintype "passive"))
      (node (ref "Q8") (pin "1") (pinfunction "G_1") (pintype "passive"))
      (node (ref "Q9") (pin "6") (pinfunction "D_6") (pintype "passive"))
      (node (ref "R56") (pin "2") (pinfunction "2_2") (pintype "passive"))
    )
    (net (code "197") (name "Net-(Q8B-G)") (class "Default")
      (node (ref "C45") (pin "2") (pinfunction "2_2") (pintype "passive"))
      (node (ref "Q8") (pin "3") (pinfunction "G_3") (pintype "passive"))
      (node (ref "Q9") (pin "3") (pinfunction "D_3") (pintype "passive"))
      (node (ref "R61") (pin "2") (pinfunction "2_2") (pintype "passive"))
    )
    (net (code "198") (name "Net-(Q9A-S)") (class "Default")
      (node (ref "Q9") (pin "1") (pinfunction "S_1") (pintype "passive"))
      (node (ref "R57") (pin "2") (pinfunction "2_2") (pintype "passive"))
    )
    (net (code "199") (name "Net-(Q9B-S)") (class "Default")
      (node (ref "Q9") (pin "4") (pinfunction "S_4") (pintype "passive"))
      (node (ref "R59") (pin "1") (pinfunction "1_1") (pintype "passive"))
    )
    (net (code "200") (name "Net-(Q10A-D)") (class "Default")
      (node (ref "Q10") (pin "6") (pinfunction "D_6") (pintype "passive"))
      (node (ref "R79") (pin "2") (pinfunction "2_2") (pintype "passive"))
    )
    (net (code "201") (name "Net-(Q10A-S)") (class "Default")
      (node (ref "Q10") (pin "1") (pinfunction "S_1") (pintype "passive"))
      (node (ref "Q10") (pin "5") (pinfunction "G_5") (pintype "passive"))
      (node (ref "R80") (pin "1") (pinfunction "1_1") (pintype "passive"))
    )
    (net (code "202") (name "Net-(Q11A-D)") (class "Default")
      (node (ref "Q11") (pin "6") (pinfunction "D_6") (pintype "passive"))
      (node (ref "R63") (pin "2") (pinfunction "2_2") (pintype "passive"))
    )
    (net (code "203") (name "Net-(Q11A-S)") (class "Default")
      (node (ref "Q11") (pin "1") (pinfunction "S_1") (pintype "passive"))
      (node (ref "Q11") (pin "5") (pinfunction "G_5") (pintype "passive"))
      (node (ref "R64") (pin "1") (pinfunction "1_1") (pintype "passive"))
    )
    (net (code "204") (name "Net-(Q12A-D)") (class "Default")
      (node (ref "Q12") (pin "6") (pinfunction "D_6") (pintype "passive"))
      (node (ref "R85") (pin "2") (pinfunction "2_2") (pintype "passive"))
    )
    (net (code "205") (name "Net-(Q12A-S)") (class "Default")
      (node (ref "Q12") (pin "1") (pinfunction "S_1") (pintype "passive"))
      (node (ref "Q12") (pin "5") (pinfunction "G_5") (pintype "passive"))
      (node (ref "R86") (pin "1") (pinfunction "1_1") (pintype "passive"))
    )
    (net (code "206") (name "Net-(Q13A-D)") (class "Default")
      (node (ref "Q13") (pin "6") (pinfunction "D_6") (pintype "passive"))
      (node (ref "R69") (pin "2") (pinfunction "2_2") (pintype "passive"))
    )
    (net (code "207") (name "Net-(Q13A-S)") (class "Default")
      (node (ref "Q13") (pin "1") (pinfunction "S_1") (pintype "passive"))
      (node (ref "Q13") (pin "5") (pinfunction "G_5") (pintype "passive"))
      (node (ref "R70") (pin "1") (pinfunction "1_1") (pintype "passive"))
    )
    (net (code "208") (name "Net-(Q14A-D)") (class "Default")
      (node (ref "Q14") (pin "6") (pinfunction "D_6") (pintype "passive"))
      (node (ref "R117") (pin "2") (pinfunction "2_2") (pintype "passive"))
      (node (ref "R123") (pin "2") (pinfunction "2_2") (pintype "passive"))
    )
    (net (code "209") (name "Net-(Q14A-G)") (class "Default")
      (node (ref "Q14") (pin "2") (pinfunction "G_2") (pintype "passive"))
      (node (ref "R118") (pin "1") (pinfunction "1_1") (pintype "passive"))
      (node (ref "R119") (pin "1") (pinfunction "1_1") (pintype "passive"))
    )
    (net (code "210") (name "Net-(R23-Pad1)") (class "Default")
      (node (ref "R23") (pin "1") (pinfunction "1_1") (pintype "passive"))
      (node (ref "R49") (pin "2") (pinfunction "2_2") (pintype "passive"))
    )
    (net (code "211") (name "Net-(R35-Pad2)") (class "Default")
      (node (ref "R35") (pin "2") (pinfunction "2_2") (pintype "passive"))
      (node (ref "R36") (pin "1") (pinfunction "1_1") (pintype "passive"))
      (node (ref "R37") (pin "2") (pinfunction "2_2") (pintype "passive"))
      (node (ref "R38") (pin "1") (pinfunction "1_1") (pintype "passive"))
    )
    (net (code "212") (name "Net-(R94-Pad2)") (class "Default")
      (node (ref "R94") (pin "2") (pinfunction "2_2") (pintype "passive"))
      (node (ref "R95") (pin "1") (pinfunction "1_1") (pintype "passive"))
    )
    (net (code "213") (name "Net-(R97-Pad2)") (class "Default")
      (node (ref "R97") (pin "2") (pinfunction "2_2") (pintype "passive"))
      (node (ref "R98") (pin "1") (pinfunction "1_1") (pintype "passive"))
    )
    (net (code "214") (name "VBAT") (class "Default")
      (node (ref "C22") (pin "1") (pinfunction "1_1") (pintype "passive"))
      (node (ref "C23") (pin "1") (pinfunction "1_1") (pintype "passive"))
      (node (ref "C42") (pin "1") (pinfunction "1_1") (pintype "passive"))
      (node (ref "C43") (pin "1") (pinfunction "1_1") (pintype "passive"))
      (node (ref "C44") (pin "1") (pinfunction "1_1") (pintype "passive"))
      (node (ref "C45") (pin "1") (pinfunction "1_1") (pintype "passive"))
      (node (ref "C83") (pin "1") (pinfunction "1_1") (pintype "passive"))
      (node (ref "C84") (pin "1") (pinfunction "1_1") (pintype "passive"))
      (node (ref "IC10") (pin "4") (pinfunction "VIN-_4") (pintype "input"))
      (node (ref "IC8") (pin "4") (pinfunction "VIN_4") (pintype "bidirectional"))
      (node (ref "J5") (pin "5") (pinfunction "5_5") (pintype "bidirectional"))
      (node (ref "J6") (pin "5") (pinfunction "5_5") (pintype "bidirectional"))
      (node (ref "J7") (pin "1") (pinfunction "1_1") (pintype "passive"))
      (node (ref "J8") (pin "1") (pinfunction "1_1") (pintype "passive"))
      (node (ref "JP1") (pin "3") (pinfunction "3_3") (pintype "bidirectional"))
      (node (ref "Q6") (pin "2") (pinfunction "S_2") (pintype "passive"))
      (node (ref "Q6") (pin "5") (pinfunction "S_5") (pintype "passive"))
      (node (ref "Q8") (pin "2") (pinfunction "S_2") (pintype "passive"))
      (node (ref "Q8") (pin "5") (pinfunction "S_5") (pintype "passive"))
      (node (ref "R124") (pin "1") (pinfunction "1_1") (pintype "passive"))
      (node (ref "R125") (pin "1") (pinfunction "1_1") (pintype "passive"))
      (node (ref "R22") (pin "1") (pinfunction "1_1") (pintype "passive"))
      (node (ref "R33") (pin "2") (pinfunction "2_2") (pintype "passive"))
      (node (ref "R39") (pin "1") (pinfunction "1_1") (pintype "passive"))
      (node (ref "R50") (pin "1") (pinfunction "1_1") (pintype "passive"))
      (node (ref "R55") (pin "1") (pinfunction "1_1") (pintype "passive"))
      (node (ref "R56") (pin "1") (pinfunction "1_1") (pintype "passive"))
      (node (ref "R61") (pin "1") (pinfunction "1_1") (pintype "passive"))
    )
    (net (code "215") (name "unconnected-(IC2-D8-Pad30)") (class "Default")
      (node (ref "IC2") (pin "30") (pinfunction "D8_30") (pintype "tri_state"))
    )
    (net (code "216") (name "unconnected-(IC2-D9-Pad32)") (class "Default")
      (node (ref "IC2") (pin "32") (pinfunction "D9_32") (pintype "tri_state"))
    )
    (net (code "217") (name "unconnected-(IC2-D10-Pad34)") (class "Default")
      (node (ref "IC2") (pin "34") (pinfunction "D10_34") (pintype "tri_state"))
    )
    (net (code "218") (name "unconnected-(IC2-D11-Pad36)") (class "Default")
      (node (ref "IC2") (pin "36") (pinfunction "D11_36") (pintype "tri_state"))
    )
    (net (code "219") (name "unconnected-(IC2-D12-Pad39)") (class "Default")
      (node (ref "IC2") (pin "39") (pinfunction "D12_39") (pintype "tri_state"))
    )
    (net (code "220") (name "unconnected-(IC2-D13-Pad41)") (class "Default")
      (node (ref "IC2") (pin "41") (pinfunction "D13_41") (pintype "tri_state"))
    )
    (net (code "221") (name "unconnected-(IC2-D14-Pad43)") (class "Default")
      (node (ref "IC2") (pin "43") (pinfunction "D14_43") (pintype "tri_state"))
    )
    (net (code "222") (name "unconnected-(IC2-NC-Pad10)") (class "Default")
      (node (ref "IC2") (pin "10") (pinfunction "NC_10") (pintype "no_connect"))
    )
    (net (code "223") (name "unconnected-(IC2-NC1-Pad13)") (class "Default")
      (node (ref "IC2") (pin "13") (pinfunction "NC1_13") (pintype "no_connect"))
    )
    (net (code "224") (name "unconnected-(IC8-PG-Pad9)") (class "Default")
      (node (ref "IC8") (pin "9") (pinfunction "PG_9") (pintype "bidirectional"))
    )
    (net (code "225") (name "unconnected-(J1-Pad1)") (class "Default")
      (node (ref "J1") (pin "1") (pinfunction "1_1") (pintype "passive"))
    )
    (net (code "226") (name "unconnected-(J1-Pad23)") (class "Default")
      (node (ref "J1") (pin "23") (pinfunction "23_23") (pintype "passive"))
    )
    (net (code "227") (name "unconnected-(J1-Pad24)") (class "Default")
      (node (ref "J1") (pin "24") (pinfunction "24_24") (pintype "passive"))
    )
    (net (code "228") (name "unconnected-(J2-Pad1)") (class "Default")
      (node (ref "J2") (pin "1") (pinfunction "1_1") (pintype "passive"))
    )
    (net (code "229") (name "unconnected-(J2-Pad23)") (class "Default")
      (node (ref "J2") (pin "23") (pinfunction "23_23") (pintype "passive"))
    )
    (net (code "230") (name "unconnected-(J2-Pad24)") (class "Default")
      (node (ref "J2") (pin "24") (pinfunction "24_24") (pintype "passive"))
    )
    (net (code "231") (name "unconnected-(J5-Pad6)") (class "Default")
      (node (ref "J5") (pin "6") (pinfunction "6_6") (pintype "bidirectional"))
    )
    (net (code "232") (name "unconnected-(J6-Pad6)") (class "Default")
      (node (ref "J6") (pin "6") (pinfunction "6_6") (pintype "bidirectional"))
    )
    (net (code "233") (name "unconnected-(J11-DAT1-Pad8)") (class "Default")
      (node (ref "J11") (pin "8") (pinfunction "DAT1_8") (pintype "passive"))
    )
    (net (code "234") (name "unconnected-(J11-DAT2-Pad1)") (class "Default")
      (node (ref "J11") (pin "1") (pinfunction "DAT2_1") (pintype "passive"))
    )
    (net (code "235") (name "unconnected-(J14-Pad8)") (class "Default")
      (node (ref "J14") (pin "8") (pinfunction "8_8") (pintype "passive"))
    )
    (net (code "236") (name "unconnected-(J15-Pad2)") (class "Default")
      (node (ref "J15") (pin "2") (pinfunction "2_2") (pintype "passive"))
    )
    (net (code "237") (name "unconnected-(J15-Pad4)") (class "Default")
      (node (ref "J15") (pin "4") (pinfunction "4_4") (pintype "passive"))
    )
    (net (code "238") (name "unconnected-(J15-Pad5)") (class "Default")
      (node (ref "J15") (pin "5") (pinfunction "5_5") (pintype "passive"))
    )
    (net (code "239") (name "unconnected-(J15-Pad6)") (class "Default")
      (node (ref "J15") (pin "6") (pinfunction "6_6") (pintype "passive"))
    )
    (net (code "240") (name "unconnected-(J15-Pad7)") (class "Default")
      (node (ref "J15") (pin "7") (pinfunction "7_7") (pintype "passive"))
    )
    (net (code "241") (name "unconnected-(J15-Pad10)") (class "Default")
      (node (ref "J15") (pin "10") (pinfunction "10_10") (pintype "passive"))
    )
    (net (code "242") (name "unconnected-(J15-Pad15)") (class "Default")
      (node (ref "J15") (pin "15") (pinfunction "15_15") (pintype "passive"))
    )
    (net (code "243") (name "unconnected-(J15-Pad16)") (class "Default")
      (node (ref "J15") (pin "16") (pinfunction "16_16") (pintype "passive"))
    )
    (net (code "244") (name "unconnected-(Q3B-D-Pad3)") (class "Default")
      (node (ref "Q3") (pin "3") (pinfunction "D_3") (pintype "passive"))
    )
    (net (code "245") (name "unconnected-(Q3B-G-Pad5)") (class "Default")
      (node (ref "Q3") (pin "5") (pinfunction "G_5") (pintype "passive"))
    )
    (net (code "246") (name "unconnected-(Q3B-S-Pad4)") (class "Default")
      (node (ref "Q3") (pin "4") (pinfunction "S_4") (pintype "passive"))
    )
    (net (code "247") (name "unconnected-(Q14B-D-Pad3)") (class "Default")
      (node (ref "Q14") (pin "3") (pinfunction "D_3") (pintype "passive"))
    )
    (net (code "248") (name "unconnected-(Q14B-G-Pad5)") (class "Default")
      (node (ref "Q14") (pin "5") (pinfunction "G_5") (pintype "passive"))
    )
    (net (code "249") (name "unconnected-(Q14B-S-Pad4)") (class "Default")
      (node (ref "Q14") (pin "4") (pinfunction "S_4") (pintype "passive"))
    )
  )
)
